# relay_matrix_16x8.net
KiCad netlist of a schematic drawn in EAGLE
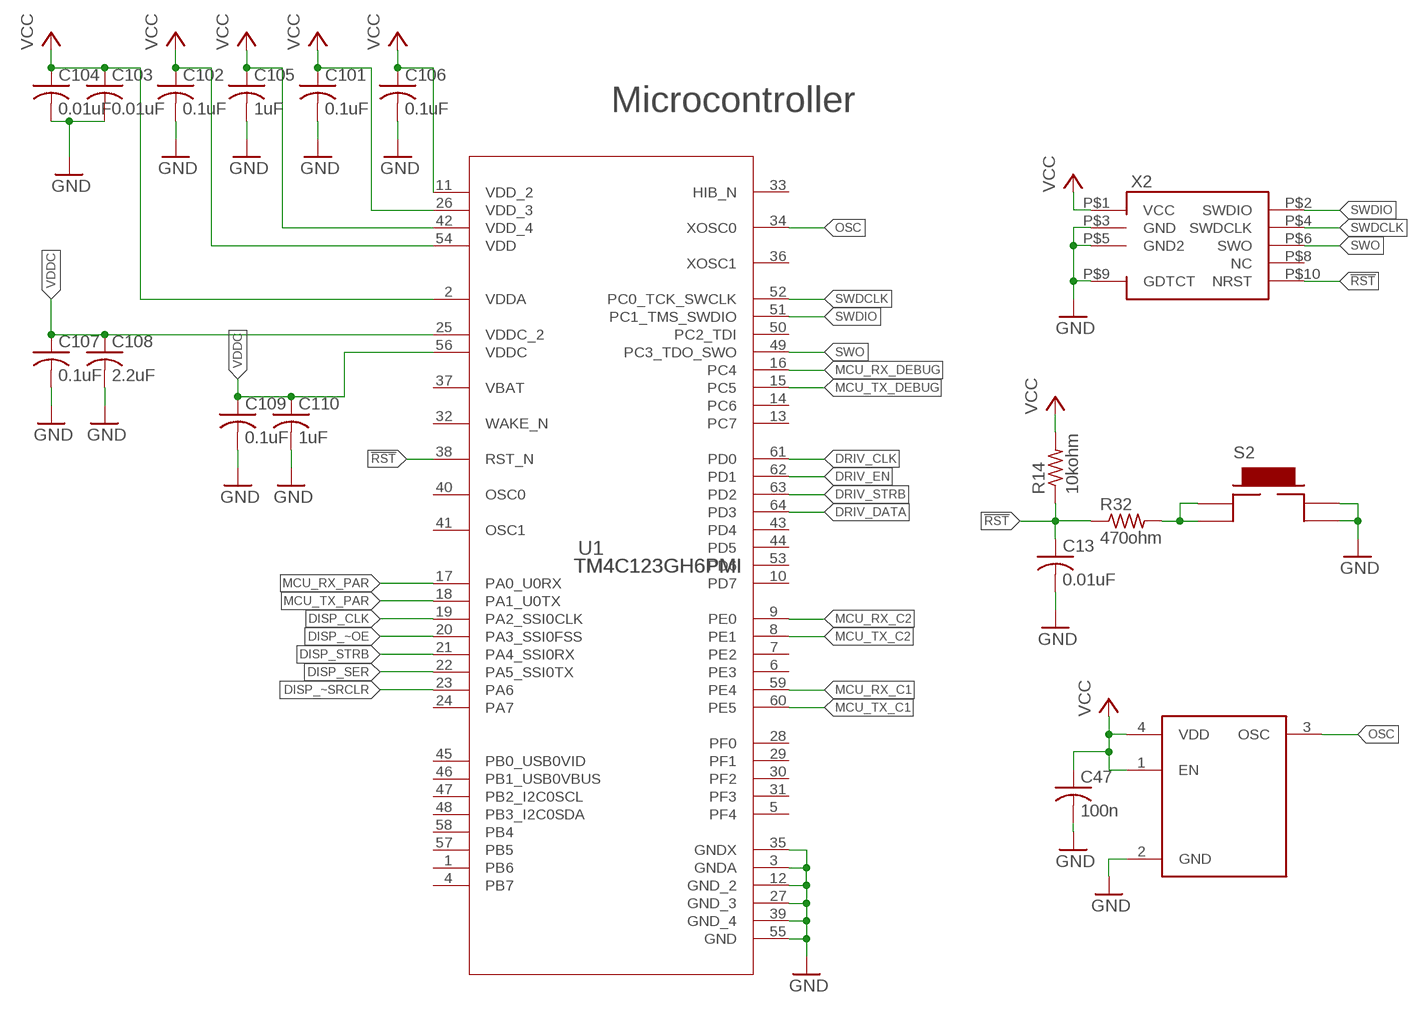
[diagram p0: schematic, sheet 1]
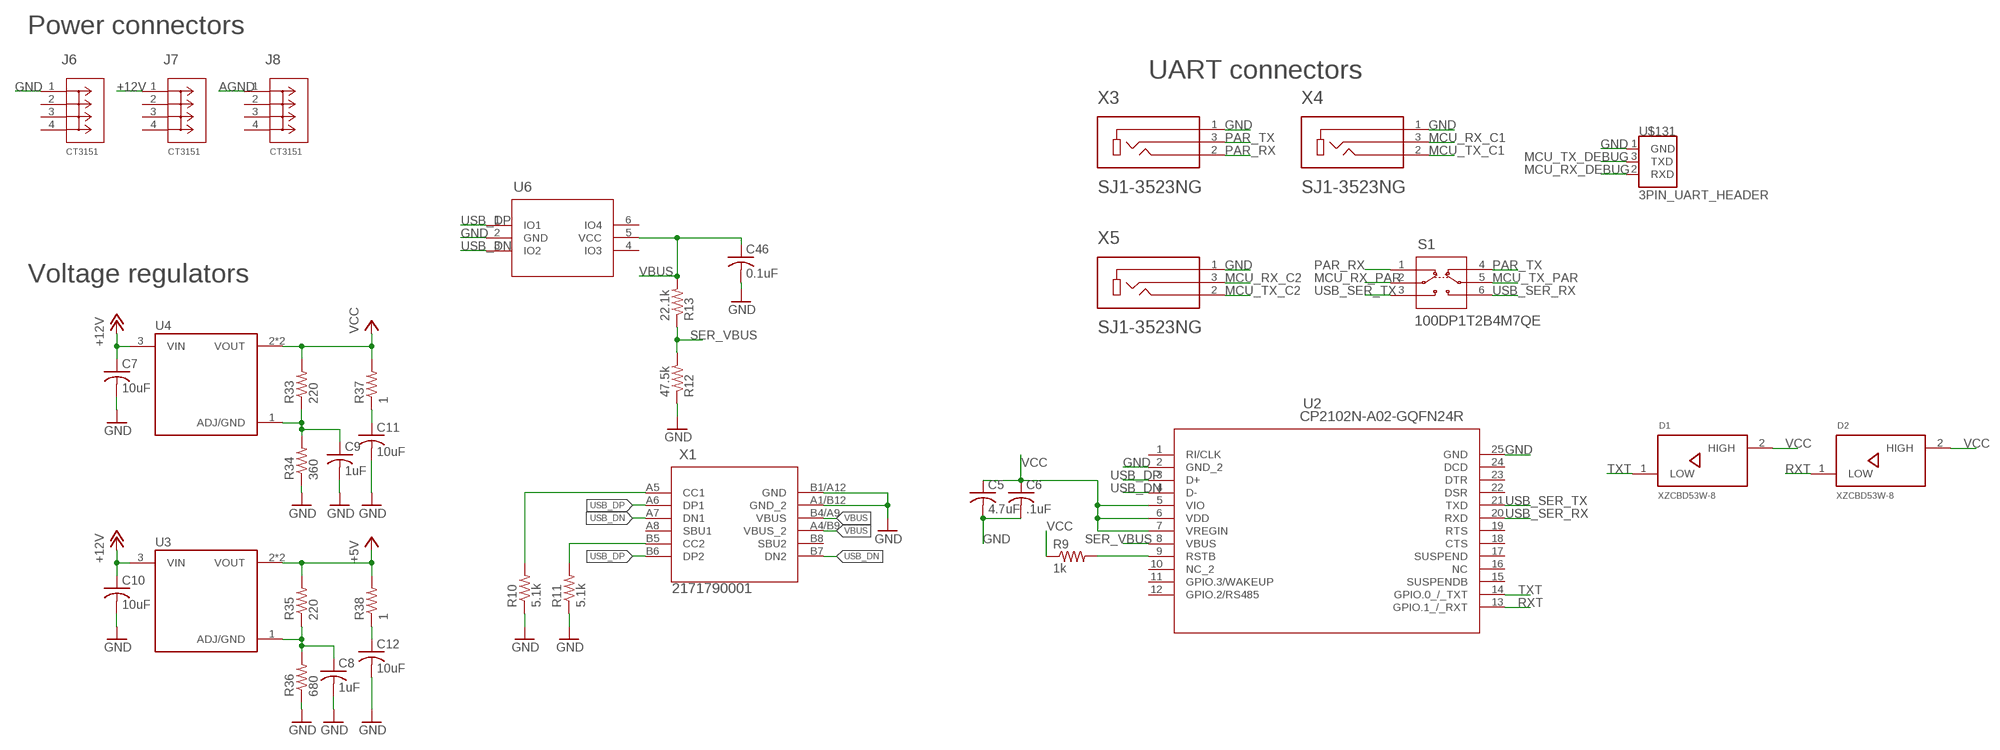
[diagram p1: schematic, sheet 2]
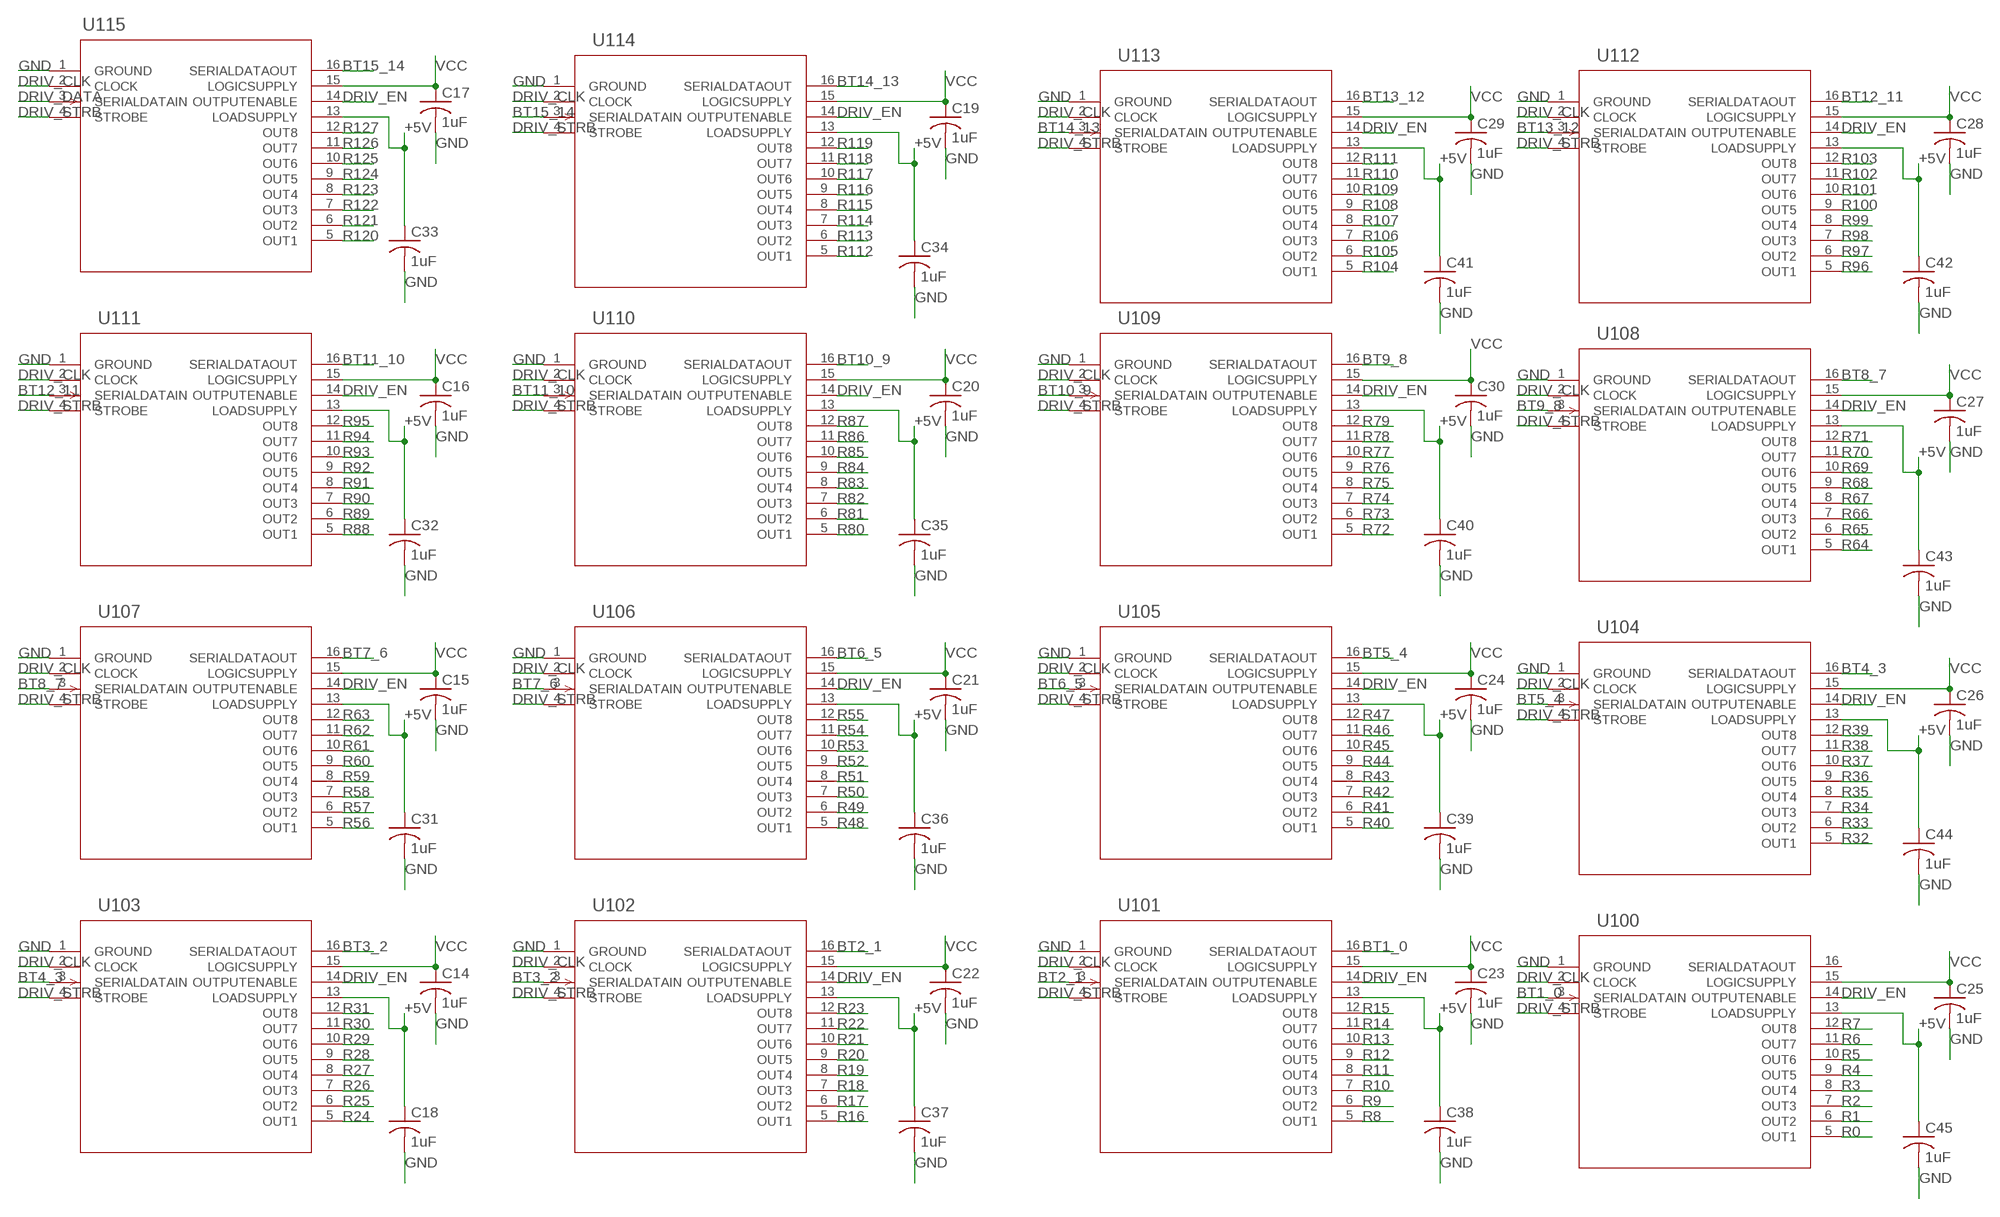
[diagram p2: schematic, sheet 3]
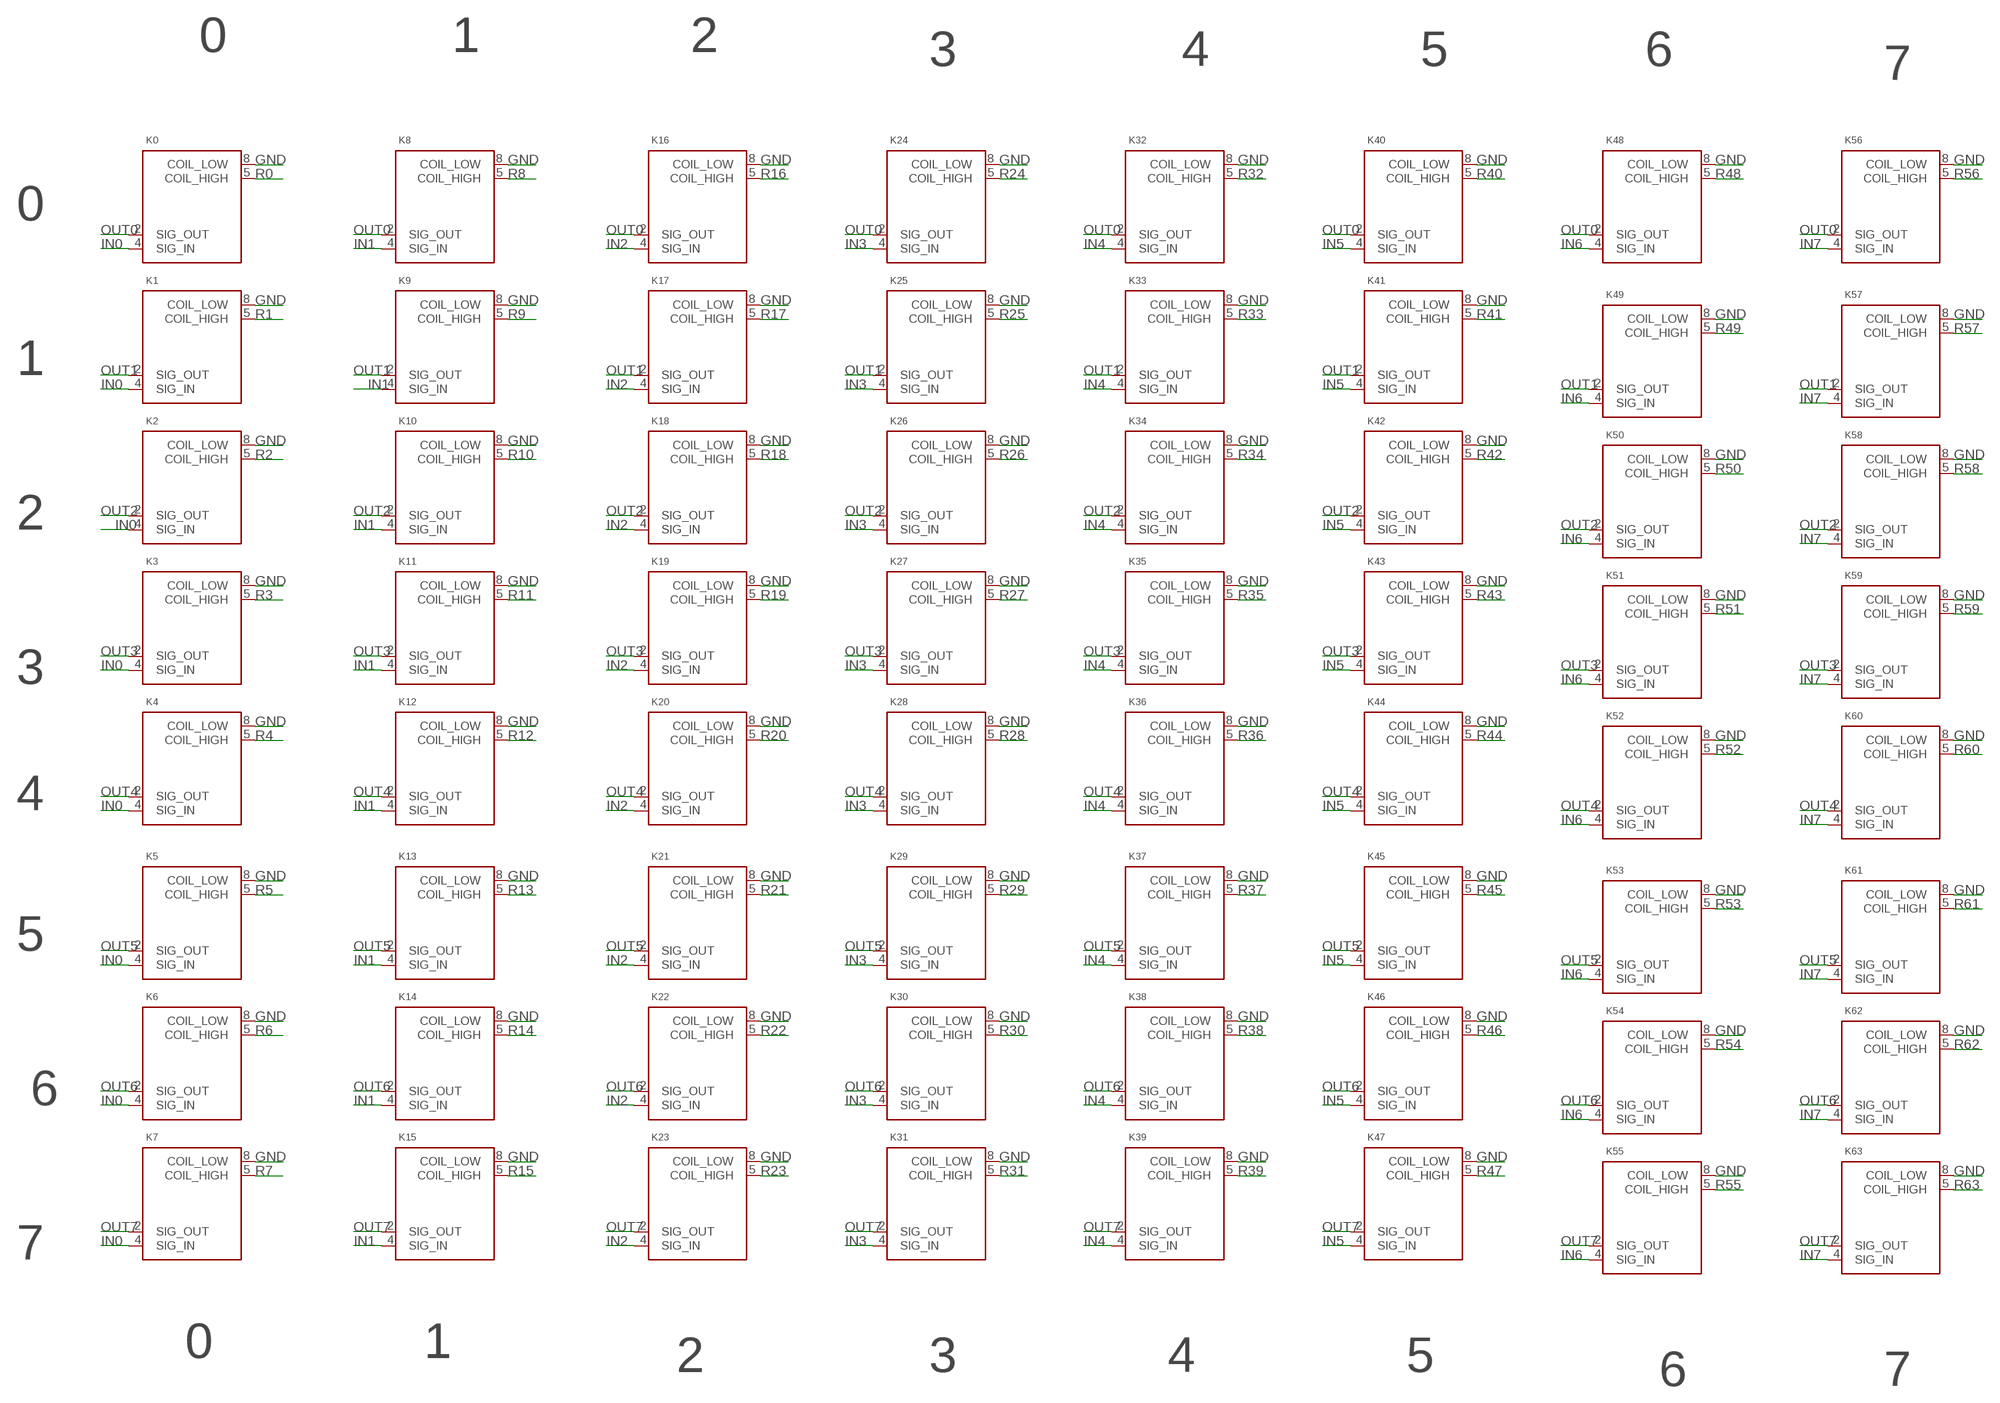
[diagram p3: schematic, sheet 4, part 1 of 2]
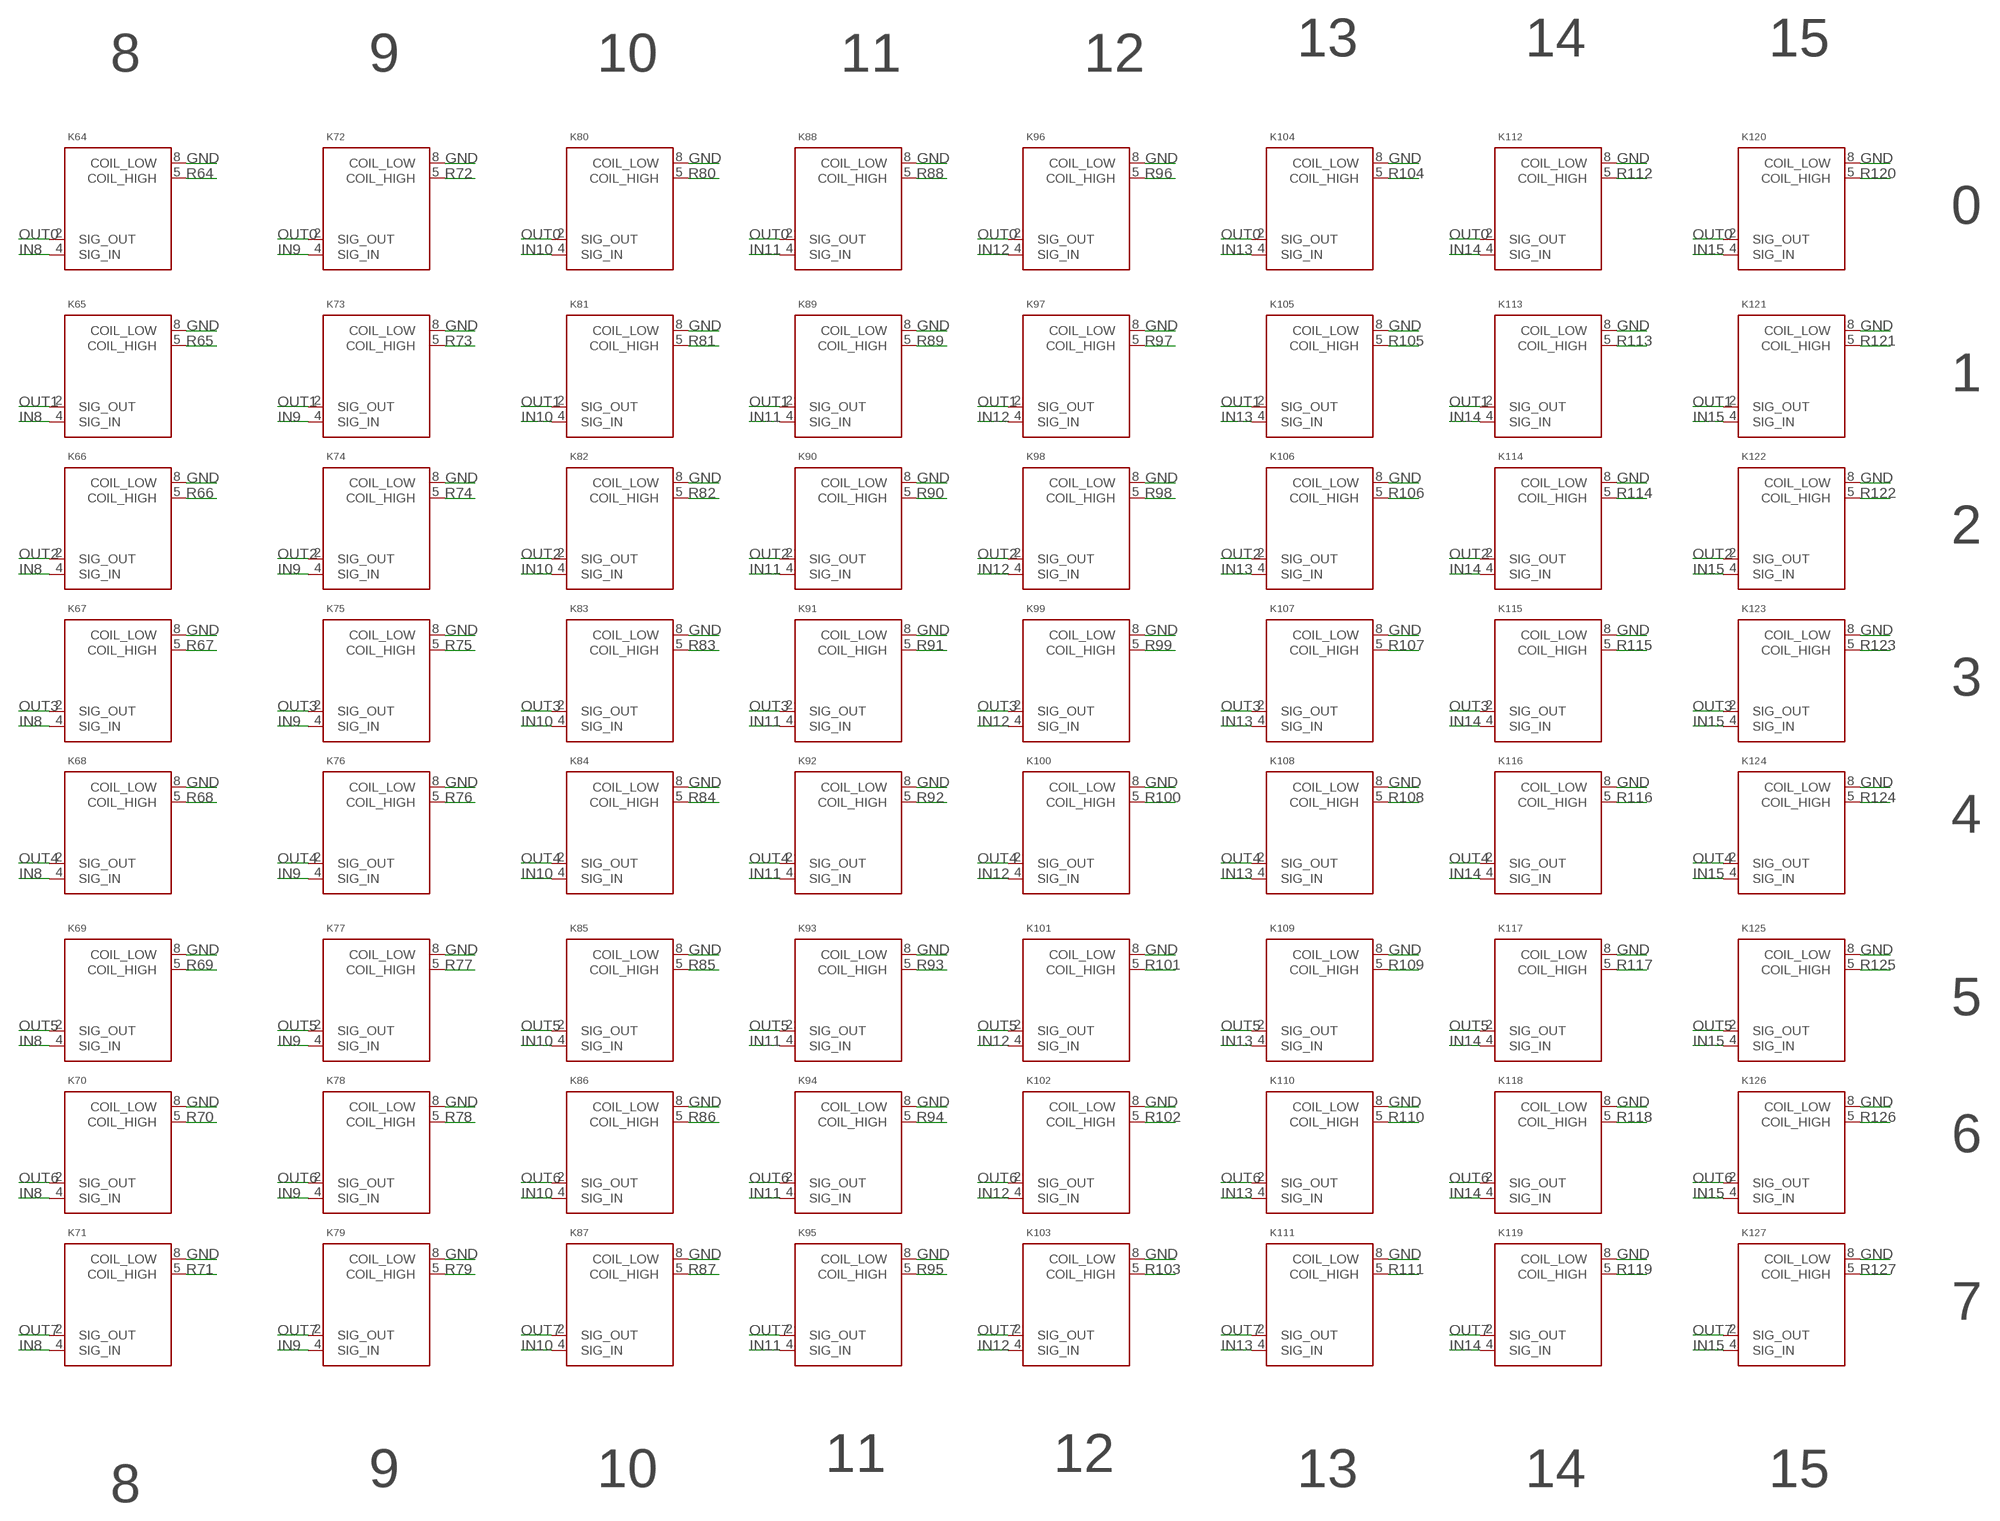
[diagram p4: schematic, sheet 4, part 2 of 2]
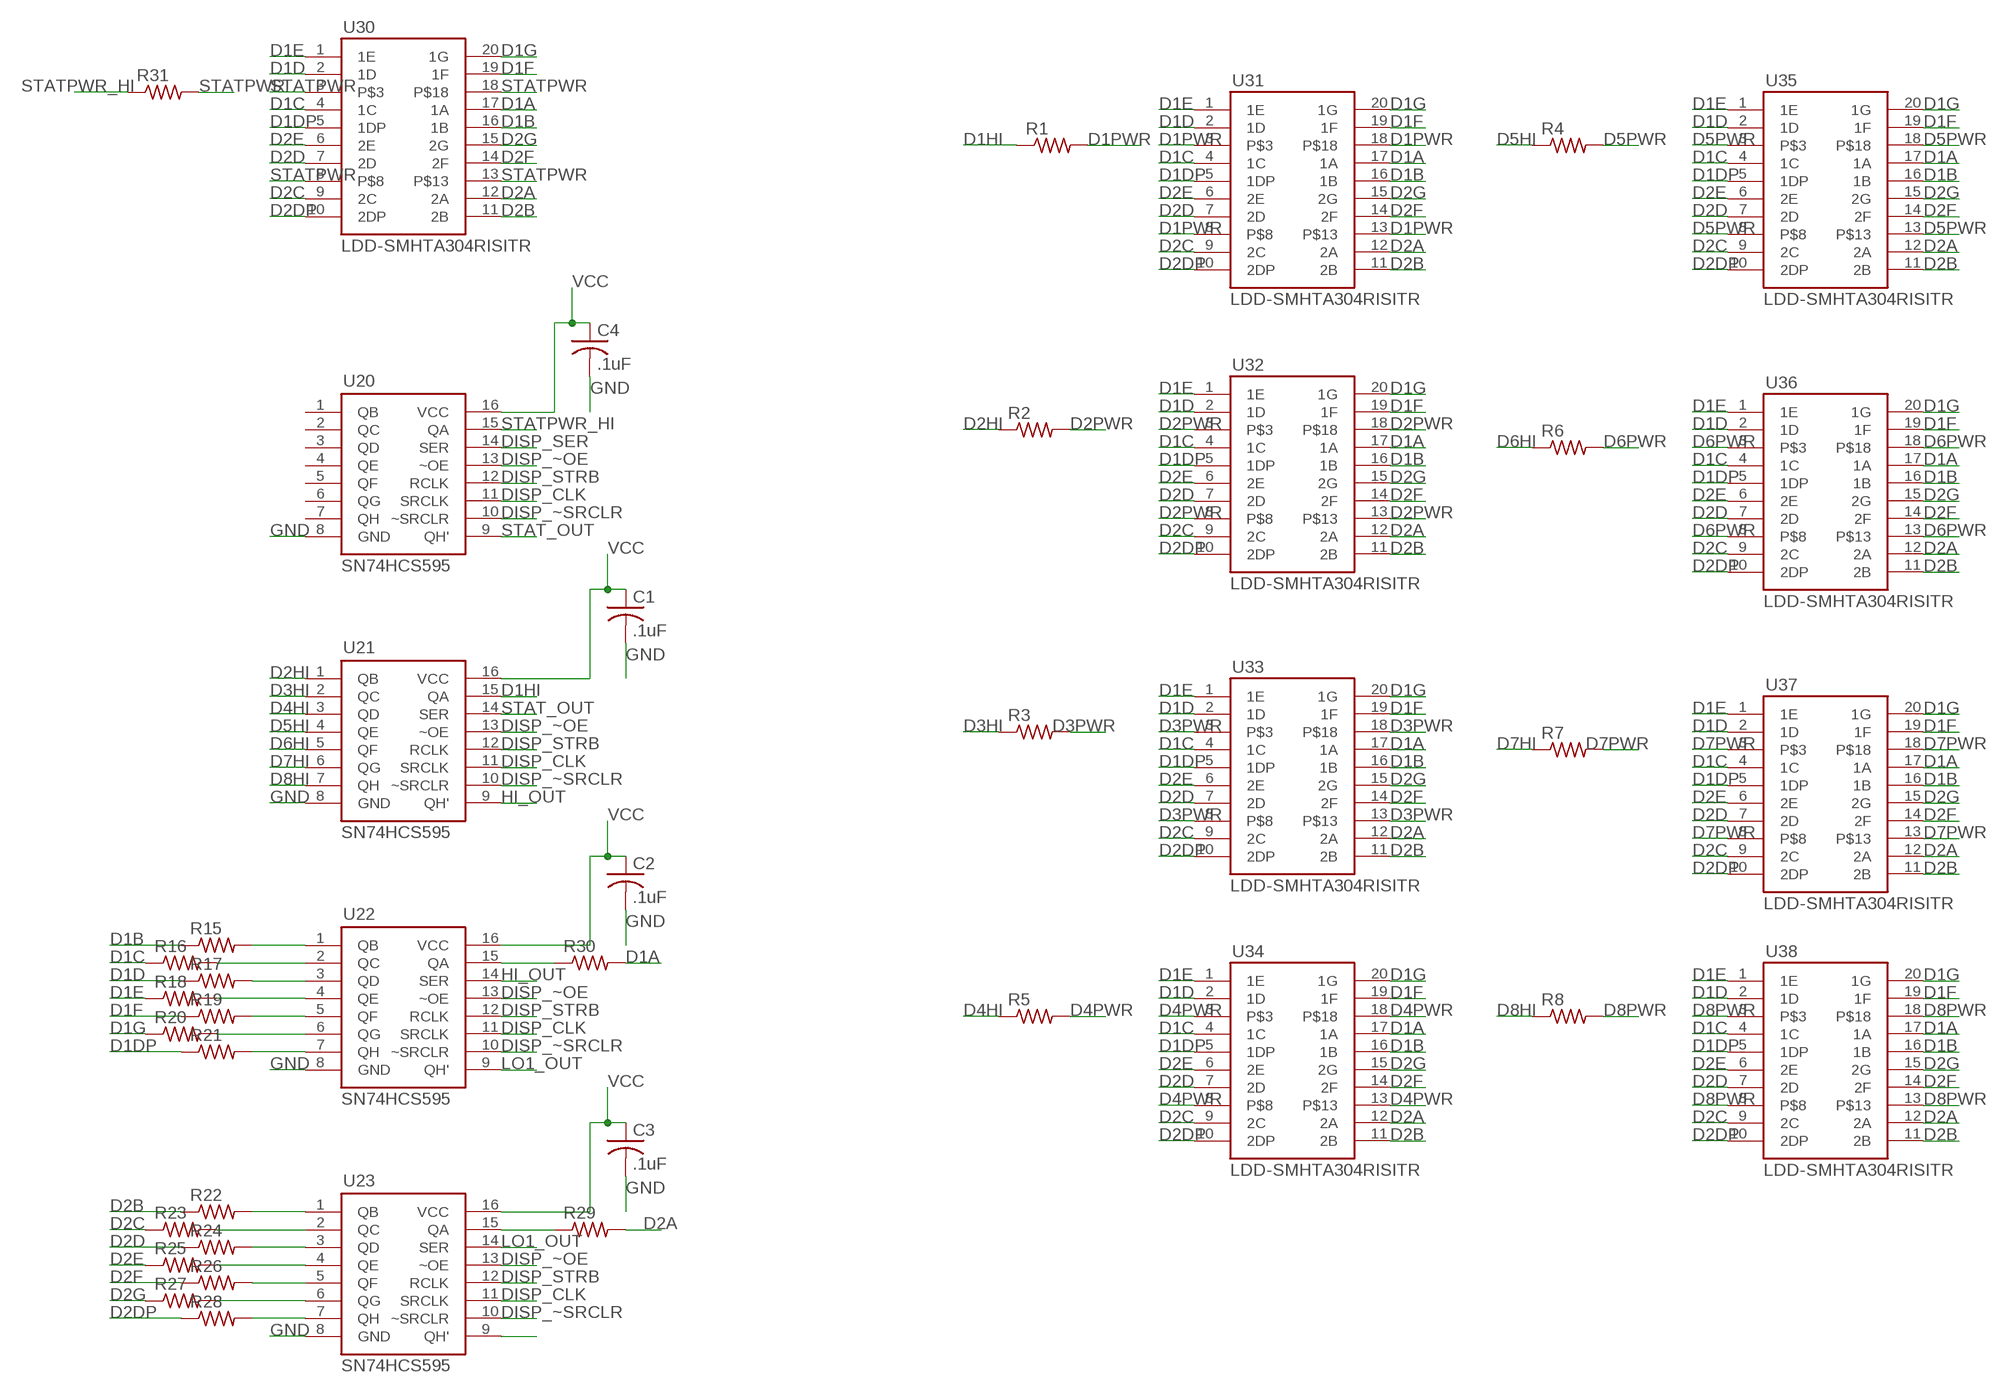
[diagram p5: schematic, sheet 5]
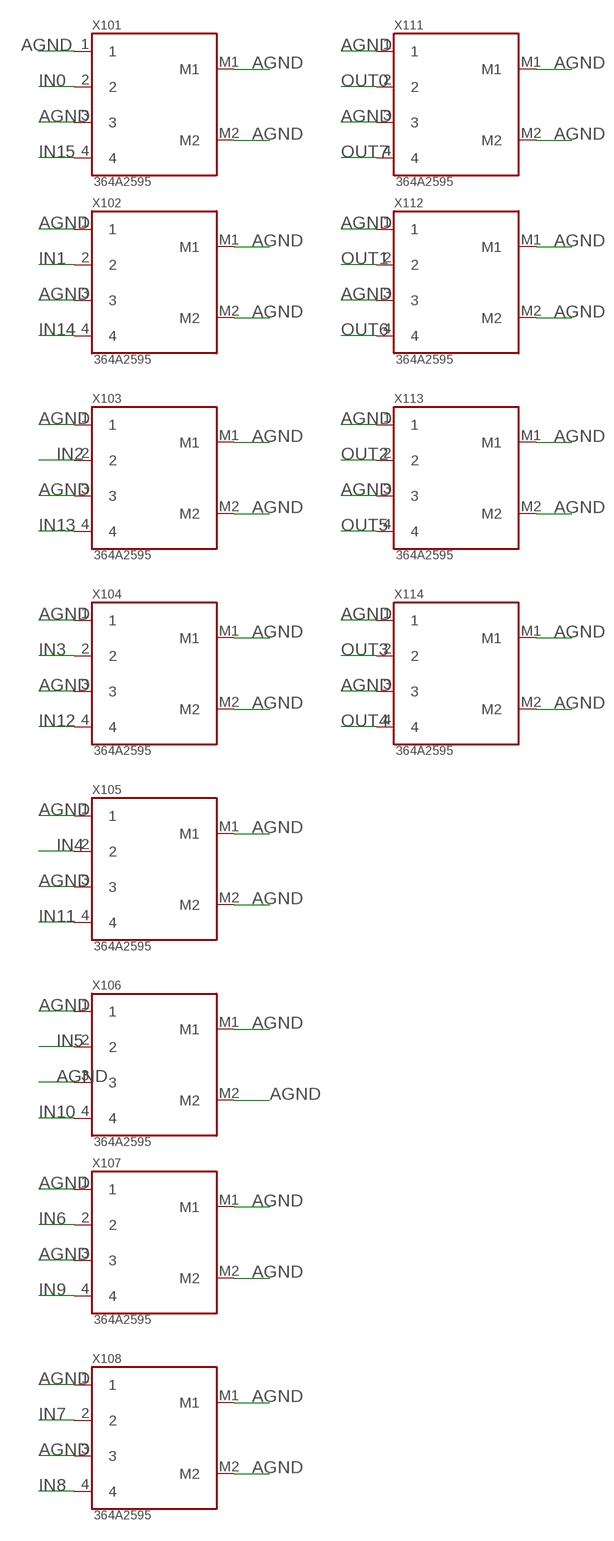
[diagram p6: schematic, sheet 6]

(export (version "E")
  (design (tool "Eeschema 10.0.6"))
  (components
    (comp (ref "X101")
      (value "364A2595")
      (footprint "eagle-import:364A2595")
      (libsource (lib "eagle-import") (part "364A2595"))
    )
    (comp (ref "X102")
      (value "364A2595")
      (footprint "eagle-import:364A2595")
      (libsource (lib "eagle-import") (part "364A2595"))
    )
    (comp (ref "X103")
      (value "364A2595")
      (footprint "eagle-import:364A2595")
      (libsource (lib "eagle-import") (part "364A2595"))
    )
    (comp (ref "X104")
      (value "364A2595")
      (footprint "eagle-import:364A2595")
      (libsource (lib "eagle-import") (part "364A2595"))
    )
    (comp (ref "X105")
      (value "364A2595")
      (footprint "eagle-import:364A2595")
      (libsource (lib "eagle-import") (part "364A2595"))
    )
    (comp (ref "X106")
      (value "364A2595")
      (footprint "eagle-import:364A2595")
      (libsource (lib "eagle-import") (part "364A2595"))
    )
    (comp (ref "X107")
      (value "364A2595")
      (footprint "eagle-import:364A2595")
      (libsource (lib "eagle-import") (part "364A2595"))
    )
    (comp (ref "X108")
      (value "364A2595")
      (footprint "eagle-import:364A2595")
      (libsource (lib "eagle-import") (part "364A2595"))
    )
    (comp (ref "X111")
      (value "364A2595")
      (footprint "eagle-import:364A2595")
      (libsource (lib "eagle-import") (part "364A2595"))
    )
    (comp (ref "X112")
      (value "364A2595")
      (footprint "eagle-import:364A2595")
      (libsource (lib "eagle-import") (part "364A2595"))
    )
    (comp (ref "X113")
      (value "364A2595")
      (footprint "eagle-import:364A2595")
      (libsource (lib "eagle-import") (part "364A2595"))
    )
    (comp (ref "X114")
      (value "364A2595")
      (footprint "eagle-import:364A2595")
      (libsource (lib "eagle-import") (part "364A2595"))
    )
    (comp (ref "C1")
      (value ".1uF")
      (footprint "eagle-import:C0402")
      (fields (field (name "MANUFACTURER_PART_NUMBER") "CL05B104KO5NNNC"))
      (libsource (lib "eagle-import") (part "resistor_348_C-USC0402"))
    )
    (comp (ref "C2")
      (value ".1uF")
      (footprint "eagle-import:C0402")
      (fields (field (name "MANUFACTURER_PART_NUMBER") "CL05B104KO5NNNC"))
      (libsource (lib "eagle-import") (part "resistor_348_C-USC0402"))
    )
    (comp (ref "C3")
      (value ".1uF")
      (footprint "eagle-import:C0402")
      (fields (field (name "MANUFACTURER_PART_NUMBER") "CL05B104KO5NNNC"))
      (libsource (lib "eagle-import") (part "resistor_348_C-USC0402"))
    )
    (comp (ref "C4")
      (value ".1uF")
      (footprint "eagle-import:C0402")
      (fields (field (name "MANUFACTURER_PART_NUMBER") "CL05B104KO5NNNC"))
      (libsource (lib "eagle-import") (part "resistor_348_C-USC0402"))
    )
    (comp (ref "R1")
      (value "R-US_R0402")
      (footprint "eagle-import:R0402")
      (libsource (lib "eagle-import") (part "resistor_348_R-US_R0402"))
    )
    (comp (ref "R2")
      (value "R-US_R0402")
      (footprint "eagle-import:R0402")
      (libsource (lib "eagle-import") (part "resistor_348_R-US_R0402"))
    )
    (comp (ref "R3")
      (value "R-US_R0402")
      (footprint "eagle-import:R0402")
      (libsource (lib "eagle-import") (part "resistor_348_R-US_R0402"))
    )
    (comp (ref "R4")
      (value "R-US_R0402")
      (footprint "eagle-import:R0402")
      (libsource (lib "eagle-import") (part "resistor_348_R-US_R0402"))
    )
    (comp (ref "R5")
      (value "R-US_R0402")
      (footprint "eagle-import:R0402")
      (libsource (lib "eagle-import") (part "resistor_348_R-US_R0402"))
    )
    (comp (ref "R6")
      (value "R-US_R0402")
      (footprint "eagle-import:R0402")
      (libsource (lib "eagle-import") (part "resistor_348_R-US_R0402"))
    )
    (comp (ref "R7")
      (value "R-US_R0402")
      (footprint "eagle-import:R0402")
      (libsource (lib "eagle-import") (part "resistor_348_R-US_R0402"))
    )
    (comp (ref "R8")
      (value "R-US_R0402")
      (footprint "eagle-import:R0402")
      (libsource (lib "eagle-import") (part "resistor_348_R-US_R0402"))
    )
    (comp (ref "R15")
      (value "R-US_R0402")
      (footprint "eagle-import:R0402")
      (libsource (lib "eagle-import") (part "resistor_348_R-US_R0402"))
    )
    (comp (ref "R16")
      (value "R-US_R0402")
      (footprint "eagle-import:R0402")
      (libsource (lib "eagle-import") (part "resistor_348_R-US_R0402"))
    )
    (comp (ref "R17")
      (value "R-US_R0402")
      (footprint "eagle-import:R0402")
      (libsource (lib "eagle-import") (part "resistor_348_R-US_R0402"))
    )
    (comp (ref "R18")
      (value "R-US_R0402")
      (footprint "eagle-import:R0402")
      (libsource (lib "eagle-import") (part "resistor_348_R-US_R0402"))
    )
    (comp (ref "R19")
      (value "R-US_R0402")
      (footprint "eagle-import:R0402")
      (libsource (lib "eagle-import") (part "resistor_348_R-US_R0402"))
    )
    (comp (ref "R20")
      (value "R-US_R0402")
      (footprint "eagle-import:R0402")
      (libsource (lib "eagle-import") (part "resistor_348_R-US_R0402"))
    )
    (comp (ref "R21")
      (value "R-US_R0402")
      (footprint "eagle-import:R0402")
      (libsource (lib "eagle-import") (part "resistor_348_R-US_R0402"))
    )
    (comp (ref "R22")
      (value "R-US_R0402")
      (footprint "eagle-import:R0402")
      (libsource (lib "eagle-import") (part "resistor_348_R-US_R0402"))
    )
    (comp (ref "R23")
      (value "R-US_R0402")
      (footprint "eagle-import:R0402")
      (libsource (lib "eagle-import") (part "resistor_348_R-US_R0402"))
    )
    (comp (ref "R24")
      (value "R-US_R0402")
      (footprint "eagle-import:R0402")
      (libsource (lib "eagle-import") (part "resistor_348_R-US_R0402"))
    )
    (comp (ref "R25")
      (value "R-US_R0402")
      (footprint "eagle-import:R0402")
      (libsource (lib "eagle-import") (part "resistor_348_R-US_R0402"))
    )
    (comp (ref "R26")
      (value "R-US_R0402")
      (footprint "eagle-import:R0402")
      (libsource (lib "eagle-import") (part "resistor_348_R-US_R0402"))
    )
    (comp (ref "R27")
      (value "R-US_R0402")
      (footprint "eagle-import:R0402")
      (libsource (lib "eagle-import") (part "resistor_348_R-US_R0402"))
    )
    (comp (ref "R28")
      (value "R-US_R0402")
      (footprint "eagle-import:R0402")
      (libsource (lib "eagle-import") (part "resistor_348_R-US_R0402"))
    )
    (comp (ref "R29")
      (value "R-US_R0402")
      (footprint "eagle-import:R0402")
      (libsource (lib "eagle-import") (part "resistor_348_R-US_R0402"))
    )
    (comp (ref "R30")
      (value "R-US_R0402")
      (footprint "eagle-import:R0402")
      (libsource (lib "eagle-import") (part "resistor_348_R-US_R0402"))
    )
    (comp (ref "R31")
      (value "R-US_R0402")
      (footprint "eagle-import:R0402")
      (libsource (lib "eagle-import") (part "resistor_348_R-US_R0402"))
    )
    (comp (ref "U20")
      (value "SN74HCS595")
      (footprint "eagle-import:SOP65P640X120-16N")
      (fields (field (name "MANUFACTURER_PART_NUMBER") "SN74HCS595PWR"))
      (libsource (lib "eagle-import") (part "SN74HCS595"))
    )
    (comp (ref "U21")
      (value "SN74HCS595")
      (footprint "eagle-import:SOP65P640X120-16N")
      (fields (field (name "MANUFACTURER_PART_NUMBER") "SN74HCS595PWR"))
      (libsource (lib "eagle-import") (part "SN74HCS595"))
    )
    (comp (ref "U22")
      (value "SN74HCS595")
      (footprint "eagle-import:SOP65P640X120-16N")
      (fields (field (name "MANUFACTURER_PART_NUMBER") "SN74HCS595PWR"))
      (libsource (lib "eagle-import") (part "SN74HCS595"))
    )
    (comp (ref "U23")
      (value "SN74HCS595")
      (footprint "eagle-import:SOP65P640X120-16N")
      (fields (field (name "MANUFACTURER_PART_NUMBER") "SN74HCS595PWR"))
      (libsource (lib "eagle-import") (part "SN74HCS595"))
    )
    (comp (ref "U30")
      (value "LDD-SMHTA304RISITR")
      (footprint "eagle-import:LDD-SMHTA304RISITR-20DFN")
      (libsource (lib "eagle-import") (part "LDD-SMHTA304RISITR"))
    )
    (comp (ref "U31")
      (value "LDD-SMHTA304RISITR")
      (footprint "eagle-import:LDD-SMHTA304RISITR-20DFN")
      (libsource (lib "eagle-import") (part "LDD-SMHTA304RISITR"))
    )
    (comp (ref "U32")
      (value "LDD-SMHTA304RISITR")
      (footprint "eagle-import:LDD-SMHTA304RISITR-20DFN")
      (libsource (lib "eagle-import") (part "LDD-SMHTA304RISITR"))
    )
    (comp (ref "U33")
      (value "LDD-SMHTA304RISITR")
      (footprint "eagle-import:LDD-SMHTA304RISITR-20DFN")
      (libsource (lib "eagle-import") (part "LDD-SMHTA304RISITR"))
    )
    (comp (ref "U34")
      (value "LDD-SMHTA304RISITR")
      (footprint "eagle-import:LDD-SMHTA304RISITR-20DFN")
      (libsource (lib "eagle-import") (part "LDD-SMHTA304RISITR"))
    )
    (comp (ref "U35")
      (value "LDD-SMHTA304RISITR")
      (footprint "eagle-import:LDD-SMHTA304RISITR-20DFN")
      (libsource (lib "eagle-import") (part "LDD-SMHTA304RISITR"))
    )
    (comp (ref "U36")
      (value "LDD-SMHTA304RISITR")
      (footprint "eagle-import:LDD-SMHTA304RISITR-20DFN")
      (libsource (lib "eagle-import") (part "LDD-SMHTA304RISITR"))
    )
    (comp (ref "U37")
      (value "LDD-SMHTA304RISITR")
      (footprint "eagle-import:LDD-SMHTA304RISITR-20DFN")
      (libsource (lib "eagle-import") (part "LDD-SMHTA304RISITR"))
    )
    (comp (ref "U38")
      (value "LDD-SMHTA304RISITR")
      (footprint "eagle-import:LDD-SMHTA304RISITR-20DFN")
      (libsource (lib "eagle-import") (part "LDD-SMHTA304RISITR"))
    )
    (comp (ref "K0")
      (value "G6L-1F-DC4.5")
      (footprint "eagle-import:G6L-1F-DC4.5")
      (libsource (lib "eagle-import") (part "G6L-1F-DC4.5"))
    )
    (comp (ref "K1")
      (value "G6L-1F-DC4.5")
      (footprint "eagle-import:G6L-1F-DC4.5")
      (libsource (lib "eagle-import") (part "G6L-1F-DC4.5"))
    )
    (comp (ref "K2")
      (value "G6L-1F-DC4.5")
      (footprint "eagle-import:G6L-1F-DC4.5")
      (libsource (lib "eagle-import") (part "G6L-1F-DC4.5"))
    )
    (comp (ref "K3")
      (value "G6L-1F-DC4.5")
      (footprint "eagle-import:G6L-1F-DC4.5")
      (libsource (lib "eagle-import") (part "G6L-1F-DC4.5"))
    )
    (comp (ref "K4")
      (value "G6L-1F-DC4.5")
      (footprint "eagle-import:G6L-1F-DC4.5")
      (libsource (lib "eagle-import") (part "G6L-1F-DC4.5"))
    )
    (comp (ref "K5")
      (value "G6L-1F-DC4.5")
      (footprint "eagle-import:G6L-1F-DC4.5")
      (libsource (lib "eagle-import") (part "G6L-1F-DC4.5"))
    )
    (comp (ref "K6")
      (value "G6L-1F-DC4.5")
      (footprint "eagle-import:G6L-1F-DC4.5")
      (libsource (lib "eagle-import") (part "G6L-1F-DC4.5"))
    )
    (comp (ref "K7")
      (value "G6L-1F-DC4.5")
      (footprint "eagle-import:G6L-1F-DC4.5")
      (libsource (lib "eagle-import") (part "G6L-1F-DC4.5"))
    )
    (comp (ref "K8")
      (value "G6L-1F-DC4.5")
      (footprint "eagle-import:G6L-1F-DC4.5")
      (libsource (lib "eagle-import") (part "G6L-1F-DC4.5"))
    )
    (comp (ref "K9")
      (value "G6L-1F-DC4.5")
      (footprint "eagle-import:G6L-1F-DC4.5")
      (libsource (lib "eagle-import") (part "G6L-1F-DC4.5"))
    )
    (comp (ref "K10")
      (value "G6L-1F-DC4.5")
      (footprint "eagle-import:G6L-1F-DC4.5")
      (libsource (lib "eagle-import") (part "G6L-1F-DC4.5"))
    )
    (comp (ref "K11")
      (value "G6L-1F-DC4.5")
      (footprint "eagle-import:G6L-1F-DC4.5")
      (libsource (lib "eagle-import") (part "G6L-1F-DC4.5"))
    )
    (comp (ref "K12")
      (value "G6L-1F-DC4.5")
      (footprint "eagle-import:G6L-1F-DC4.5")
      (libsource (lib "eagle-import") (part "G6L-1F-DC4.5"))
    )
    (comp (ref "K13")
      (value "G6L-1F-DC4.5")
      (footprint "eagle-import:G6L-1F-DC4.5")
      (libsource (lib "eagle-import") (part "G6L-1F-DC4.5"))
    )
    (comp (ref "K14")
      (value "G6L-1F-DC4.5")
      (footprint "eagle-import:G6L-1F-DC4.5")
      (libsource (lib "eagle-import") (part "G6L-1F-DC4.5"))
    )
    (comp (ref "K15")
      (value "G6L-1F-DC4.5")
      (footprint "eagle-import:G6L-1F-DC4.5")
      (libsource (lib "eagle-import") (part "G6L-1F-DC4.5"))
    )
    (comp (ref "K16")
      (value "G6L-1F-DC4.5")
      (footprint "eagle-import:G6L-1F-DC4.5")
      (libsource (lib "eagle-import") (part "G6L-1F-DC4.5"))
    )
    (comp (ref "K17")
      (value "G6L-1F-DC4.5")
      (footprint "eagle-import:G6L-1F-DC4.5")
      (libsource (lib "eagle-import") (part "G6L-1F-DC4.5"))
    )
    (comp (ref "K18")
      (value "G6L-1F-DC4.5")
      (footprint "eagle-import:G6L-1F-DC4.5")
      (libsource (lib "eagle-import") (part "G6L-1F-DC4.5"))
    )
    (comp (ref "K19")
      (value "G6L-1F-DC4.5")
      (footprint "eagle-import:G6L-1F-DC4.5")
      (libsource (lib "eagle-import") (part "G6L-1F-DC4.5"))
    )
    (comp (ref "K20")
      (value "G6L-1F-DC4.5")
      (footprint "eagle-import:G6L-1F-DC4.5")
      (libsource (lib "eagle-import") (part "G6L-1F-DC4.5"))
    )
    (comp (ref "K21")
      (value "G6L-1F-DC4.5")
      (footprint "eagle-import:G6L-1F-DC4.5")
      (libsource (lib "eagle-import") (part "G6L-1F-DC4.5"))
    )
    (comp (ref "K22")
      (value "G6L-1F-DC4.5")
      (footprint "eagle-import:G6L-1F-DC4.5")
      (libsource (lib "eagle-import") (part "G6L-1F-DC4.5"))
    )
    (comp (ref "K23")
      (value "G6L-1F-DC4.5")
      (footprint "eagle-import:G6L-1F-DC4.5")
      (libsource (lib "eagle-import") (part "G6L-1F-DC4.5"))
    )
    (comp (ref "K24")
      (value "G6L-1F-DC4.5")
      (footprint "eagle-import:G6L-1F-DC4.5")
      (libsource (lib "eagle-import") (part "G6L-1F-DC4.5"))
    )
    (comp (ref "K25")
      (value "G6L-1F-DC4.5")
      (footprint "eagle-import:G6L-1F-DC4.5")
      (libsource (lib "eagle-import") (part "G6L-1F-DC4.5"))
    )
    (comp (ref "K26")
      (value "G6L-1F-DC4.5")
      (footprint "eagle-import:G6L-1F-DC4.5")
      (libsource (lib "eagle-import") (part "G6L-1F-DC4.5"))
    )
    (comp (ref "K27")
      (value "G6L-1F-DC4.5")
      (footprint "eagle-import:G6L-1F-DC4.5")
      (libsource (lib "eagle-import") (part "G6L-1F-DC4.5"))
    )
    (comp (ref "K28")
      (value "G6L-1F-DC4.5")
      (footprint "eagle-import:G6L-1F-DC4.5")
      (libsource (lib "eagle-import") (part "G6L-1F-DC4.5"))
    )
    (comp (ref "K29")
      (value "G6L-1F-DC4.5")
      (footprint "eagle-import:G6L-1F-DC4.5")
      (libsource (lib "eagle-import") (part "G6L-1F-DC4.5"))
    )
    (comp (ref "K30")
      (value "G6L-1F-DC4.5")
      (footprint "eagle-import:G6L-1F-DC4.5")
      (libsource (lib "eagle-import") (part "G6L-1F-DC4.5"))
    )
    (comp (ref "K31")
      (value "G6L-1F-DC4.5")
      (footprint "eagle-import:G6L-1F-DC4.5")
      (libsource (lib "eagle-import") (part "G6L-1F-DC4.5"))
    )
    (comp (ref "K32")
      (value "G6L-1F-DC4.5")
      (footprint "eagle-import:G6L-1F-DC4.5")
      (libsource (lib "eagle-import") (part "G6L-1F-DC4.5"))
    )
    (comp (ref "K33")
      (value "G6L-1F-DC4.5")
      (footprint "eagle-import:G6L-1F-DC4.5")
      (libsource (lib "eagle-import") (part "G6L-1F-DC4.5"))
    )
    (comp (ref "K34")
      (value "G6L-1F-DC4.5")
      (footprint "eagle-import:G6L-1F-DC4.5")
      (libsource (lib "eagle-import") (part "G6L-1F-DC4.5"))
    )
    (comp (ref "K35")
      (value "G6L-1F-DC4.5")
      (footprint "eagle-import:G6L-1F-DC4.5")
      (libsource (lib "eagle-import") (part "G6L-1F-DC4.5"))
    )
    (comp (ref "K36")
      (value "G6L-1F-DC4.5")
      (footprint "eagle-import:G6L-1F-DC4.5")
      (libsource (lib "eagle-import") (part "G6L-1F-DC4.5"))
    )
    (comp (ref "K37")
      (value "G6L-1F-DC4.5")
      (footprint "eagle-import:G6L-1F-DC4.5")
      (libsource (lib "eagle-import") (part "G6L-1F-DC4.5"))
    )
    (comp (ref "K38")
      (value "G6L-1F-DC4.5")
      (footprint "eagle-import:G6L-1F-DC4.5")
      (libsource (lib "eagle-import") (part "G6L-1F-DC4.5"))
    )
    (comp (ref "K39")
      (value "G6L-1F-DC4.5")
      (footprint "eagle-import:G6L-1F-DC4.5")
      (libsource (lib "eagle-import") (part "G6L-1F-DC4.5"))
    )
    (comp (ref "K40")
      (value "G6L-1F-DC4.5")
      (footprint "eagle-import:G6L-1F-DC4.5")
      (libsource (lib "eagle-import") (part "G6L-1F-DC4.5"))
    )
    (comp (ref "K41")
      (value "G6L-1F-DC4.5")
      (footprint "eagle-import:G6L-1F-DC4.5")
      (libsource (lib "eagle-import") (part "G6L-1F-DC4.5"))
    )
    (comp (ref "K42")
      (value "G6L-1F-DC4.5")
      (footprint "eagle-import:G6L-1F-DC4.5")
      (libsource (lib "eagle-import") (part "G6L-1F-DC4.5"))
    )
    (comp (ref "K43")
      (value "G6L-1F-DC4.5")
      (footprint "eagle-import:G6L-1F-DC4.5")
      (libsource (lib "eagle-import") (part "G6L-1F-DC4.5"))
    )
    (comp (ref "K44")
      (value "G6L-1F-DC4.5")
      (footprint "eagle-import:G6L-1F-DC4.5")
      (libsource (lib "eagle-import") (part "G6L-1F-DC4.5"))
    )
    (comp (ref "K45")
      (value "G6L-1F-DC4.5")
      (footprint "eagle-import:G6L-1F-DC4.5")
      (libsource (lib "eagle-import") (part "G6L-1F-DC4.5"))
    )
    (comp (ref "K46")
      (value "G6L-1F-DC4.5")
      (footprint "eagle-import:G6L-1F-DC4.5")
      (libsource (lib "eagle-import") (part "G6L-1F-DC4.5"))
    )
    (comp (ref "K47")
      (value "G6L-1F-DC4.5")
      (footprint "eagle-import:G6L-1F-DC4.5")
      (libsource (lib "eagle-import") (part "G6L-1F-DC4.5"))
    )
    (comp (ref "K48")
      (value "G6L-1F-DC4.5")
      (footprint "eagle-import:G6L-1F-DC4.5")
      (libsource (lib "eagle-import") (part "G6L-1F-DC4.5"))
    )
    (comp (ref "K49")
      (value "G6L-1F-DC4.5")
      (footprint "eagle-import:G6L-1F-DC4.5")
      (libsource (lib "eagle-import") (part "G6L-1F-DC4.5"))
    )
    (comp (ref "K50")
      (value "G6L-1F-DC4.5")
      (footprint "eagle-import:G6L-1F-DC4.5")
      (libsource (lib "eagle-import") (part "G6L-1F-DC4.5"))
    )
    (comp (ref "K51")
      (value "G6L-1F-DC4.5")
      (footprint "eagle-import:G6L-1F-DC4.5")
      (libsource (lib "eagle-import") (part "G6L-1F-DC4.5"))
    )
    (comp (ref "K52")
      (value "G6L-1F-DC4.5")
      (footprint "eagle-import:G6L-1F-DC4.5")
      (libsource (lib "eagle-import") (part "G6L-1F-DC4.5"))
    )
    (comp (ref "K53")
      (value "G6L-1F-DC4.5")
      (footprint "eagle-import:G6L-1F-DC4.5")
      (libsource (lib "eagle-import") (part "G6L-1F-DC4.5"))
    )
    (comp (ref "K54")
      (value "G6L-1F-DC4.5")
      (footprint "eagle-import:G6L-1F-DC4.5")
      (libsource (lib "eagle-import") (part "G6L-1F-DC4.5"))
    )
    (comp (ref "K55")
      (value "G6L-1F-DC4.5")
      (footprint "eagle-import:G6L-1F-DC4.5")
      (libsource (lib "eagle-import") (part "G6L-1F-DC4.5"))
    )
    (comp (ref "K56")
      (value "G6L-1F-DC4.5")
      (footprint "eagle-import:G6L-1F-DC4.5")
      (libsource (lib "eagle-import") (part "G6L-1F-DC4.5"))
    )
    (comp (ref "K57")
      (value "G6L-1F-DC4.5")
      (footprint "eagle-import:G6L-1F-DC4.5")
      (libsource (lib "eagle-import") (part "G6L-1F-DC4.5"))
    )
    (comp (ref "K58")
      (value "G6L-1F-DC4.5")
      (footprint "eagle-import:G6L-1F-DC4.5")
      (libsource (lib "eagle-import") (part "G6L-1F-DC4.5"))
    )
    (comp (ref "K59")
      (value "G6L-1F-DC4.5")
      (footprint "eagle-import:G6L-1F-DC4.5")
      (libsource (lib "eagle-import") (part "G6L-1F-DC4.5"))
    )
    (comp (ref "K60")
      (value "G6L-1F-DC4.5")
      (footprint "eagle-import:G6L-1F-DC4.5")
      (libsource (lib "eagle-import") (part "G6L-1F-DC4.5"))
    )
    (comp (ref "K61")
      (value "G6L-1F-DC4.5")
      (footprint "eagle-import:G6L-1F-DC4.5")
      (libsource (lib "eagle-import") (part "G6L-1F-DC4.5"))
    )
    (comp (ref "K62")
      (value "G6L-1F-DC4.5")
      (footprint "eagle-import:G6L-1F-DC4.5")
      (libsource (lib "eagle-import") (part "G6L-1F-DC4.5"))
    )
    (comp (ref "K63")
      (value "G6L-1F-DC4.5")
      (footprint "eagle-import:G6L-1F-DC4.5")
      (libsource (lib "eagle-import") (part "G6L-1F-DC4.5"))
    )
    (comp (ref "K64")
      (value "G6L-1F-DC4.5")
      (footprint "eagle-import:G6L-1F-DC4.5")
      (libsource (lib "eagle-import") (part "G6L-1F-DC4.5"))
    )
    (comp (ref "K65")
      (value "G6L-1F-DC4.5")
      (footprint "eagle-import:G6L-1F-DC4.5")
      (libsource (lib "eagle-import") (part "G6L-1F-DC4.5"))
    )
    (comp (ref "K66")
      (value "G6L-1F-DC4.5")
      (footprint "eagle-import:G6L-1F-DC4.5")
      (libsource (lib "eagle-import") (part "G6L-1F-DC4.5"))
    )
    (comp (ref "K67")
      (value "G6L-1F-DC4.5")
      (footprint "eagle-import:G6L-1F-DC4.5")
      (libsource (lib "eagle-import") (part "G6L-1F-DC4.5"))
    )
    (comp (ref "K68")
      (value "G6L-1F-DC4.5")
      (footprint "eagle-import:G6L-1F-DC4.5")
      (libsource (lib "eagle-import") (part "G6L-1F-DC4.5"))
    )
    (comp (ref "K69")
      (value "G6L-1F-DC4.5")
      (footprint "eagle-import:G6L-1F-DC4.5")
      (libsource (lib "eagle-import") (part "G6L-1F-DC4.5"))
    )
    (comp (ref "K70")
      (value "G6L-1F-DC4.5")
      (footprint "eagle-import:G6L-1F-DC4.5")
      (libsource (lib "eagle-import") (part "G6L-1F-DC4.5"))
    )
    (comp (ref "K71")
      (value "G6L-1F-DC4.5")
      (footprint "eagle-import:G6L-1F-DC4.5")
      (libsource (lib "eagle-import") (part "G6L-1F-DC4.5"))
    )
    (comp (ref "K72")
      (value "G6L-1F-DC4.5")
      (footprint "eagle-import:G6L-1F-DC4.5")
      (libsource (lib "eagle-import") (part "G6L-1F-DC4.5"))
    )
    (comp (ref "K73")
      (value "G6L-1F-DC4.5")
      (footprint "eagle-import:G6L-1F-DC4.5")
      (libsource (lib "eagle-import") (part "G6L-1F-DC4.5"))
    )
    (comp (ref "K74")
      (value "G6L-1F-DC4.5")
      (footprint "eagle-import:G6L-1F-DC4.5")
      (libsource (lib "eagle-import") (part "G6L-1F-DC4.5"))
    )
    (comp (ref "K75")
      (value "G6L-1F-DC4.5")
      (footprint "eagle-import:G6L-1F-DC4.5")
      (libsource (lib "eagle-import") (part "G6L-1F-DC4.5"))
    )
    (comp (ref "K76")
      (value "G6L-1F-DC4.5")
      (footprint "eagle-import:G6L-1F-DC4.5")
      (libsource (lib "eagle-import") (part "G6L-1F-DC4.5"))
    )
    (comp (ref "K77")
      (value "G6L-1F-DC4.5")
      (footprint "eagle-import:G6L-1F-DC4.5")
      (libsource (lib "eagle-import") (part "G6L-1F-DC4.5"))
    )
    (comp (ref "K78")
      (value "G6L-1F-DC4.5")
      (footprint "eagle-import:G6L-1F-DC4.5")
      (libsource (lib "eagle-import") (part "G6L-1F-DC4.5"))
    )
    (comp (ref "K79")
      (value "G6L-1F-DC4.5")
      (footprint "eagle-import:G6L-1F-DC4.5")
      (libsource (lib "eagle-import") (part "G6L-1F-DC4.5"))
    )
    (comp (ref "K80")
      (value "G6L-1F-DC4.5")
      (footprint "eagle-import:G6L-1F-DC4.5")
      (libsource (lib "eagle-import") (part "G6L-1F-DC4.5"))
    )
    (comp (ref "K81")
      (value "G6L-1F-DC4.5")
      (footprint "eagle-import:G6L-1F-DC4.5")
      (libsource (lib "eagle-import") (part "G6L-1F-DC4.5"))
    )
    (comp (ref "K82")
      (value "G6L-1F-DC4.5")
      (footprint "eagle-import:G6L-1F-DC4.5")
      (libsource (lib "eagle-import") (part "G6L-1F-DC4.5"))
    )
    (comp (ref "K83")
      (value "G6L-1F-DC4.5")
      (footprint "eagle-import:G6L-1F-DC4.5")
      (libsource (lib "eagle-import") (part "G6L-1F-DC4.5"))
    )
    (comp (ref "K84")
      (value "G6L-1F-DC4.5")
      (footprint "eagle-import:G6L-1F-DC4.5")
      (libsource (lib "eagle-import") (part "G6L-1F-DC4.5"))
    )
    (comp (ref "K85")
      (value "G6L-1F-DC4.5")
      (footprint "eagle-import:G6L-1F-DC4.5")
      (libsource (lib "eagle-import") (part "G6L-1F-DC4.5"))
    )
    (comp (ref "K86")
      (value "G6L-1F-DC4.5")
      (footprint "eagle-import:G6L-1F-DC4.5")
      (libsource (lib "eagle-import") (part "G6L-1F-DC4.5"))
    )
    (comp (ref "K87")
      (value "G6L-1F-DC4.5")
      (footprint "eagle-import:G6L-1F-DC4.5")
      (libsource (lib "eagle-import") (part "G6L-1F-DC4.5"))
    )
    (comp (ref "K88")
      (value "G6L-1F-DC4.5")
      (footprint "eagle-import:G6L-1F-DC4.5")
      (libsource (lib "eagle-import") (part "G6L-1F-DC4.5"))
    )
    (comp (ref "K89")
      (value "G6L-1F-DC4.5")
      (footprint "eagle-import:G6L-1F-DC4.5")
      (libsource (lib "eagle-import") (part "G6L-1F-DC4.5"))
    )
    (comp (ref "K90")
      (value "G6L-1F-DC4.5")
      (footprint "eagle-import:G6L-1F-DC4.5")
      (libsource (lib "eagle-import") (part "G6L-1F-DC4.5"))
    )
    (comp (ref "K91")
      (value "G6L-1F-DC4.5")
      (footprint "eagle-import:G6L-1F-DC4.5")
      (libsource (lib "eagle-import") (part "G6L-1F-DC4.5"))
    )
    (comp (ref "K92")
      (value "G6L-1F-DC4.5")
      (footprint "eagle-import:G6L-1F-DC4.5")
      (libsource (lib "eagle-import") (part "G6L-1F-DC4.5"))
    )
    (comp (ref "K93")
      (value "G6L-1F-DC4.5")
      (footprint "eagle-import:G6L-1F-DC4.5")
      (libsource (lib "eagle-import") (part "G6L-1F-DC4.5"))
    )
    (comp (ref "K94")
      (value "G6L-1F-DC4.5")
      (footprint "eagle-import:G6L-1F-DC4.5")
      (libsource (lib "eagle-import") (part "G6L-1F-DC4.5"))
    )
    (comp (ref "K95")
      (value "G6L-1F-DC4.5")
      (footprint "eagle-import:G6L-1F-DC4.5")
      (libsource (lib "eagle-import") (part "G6L-1F-DC4.5"))
    )
    (comp (ref "K96")
      (value "G6L-1F-DC4.5")
      (footprint "eagle-import:G6L-1F-DC4.5")
      (libsource (lib "eagle-import") (part "G6L-1F-DC4.5"))
    )
    (comp (ref "K97")
      (value "G6L-1F-DC4.5")
      (footprint "eagle-import:G6L-1F-DC4.5")
      (libsource (lib "eagle-import") (part "G6L-1F-DC4.5"))
    )
    (comp (ref "K98")
      (value "G6L-1F-DC4.5")
      (footprint "eagle-import:G6L-1F-DC4.5")
      (libsource (lib "eagle-import") (part "G6L-1F-DC4.5"))
    )
    (comp (ref "K99")
      (value "G6L-1F-DC4.5")
      (footprint "eagle-import:G6L-1F-DC4.5")
      (libsource (lib "eagle-import") (part "G6L-1F-DC4.5"))
    )
    (comp (ref "K100")
      (value "G6L-1F-DC4.5")
      (footprint "eagle-import:G6L-1F-DC4.5")
      (libsource (lib "eagle-import") (part "G6L-1F-DC4.5"))
    )
    (comp (ref "K101")
      (value "G6L-1F-DC4.5")
      (footprint "eagle-import:G6L-1F-DC4.5")
      (libsource (lib "eagle-import") (part "G6L-1F-DC4.5"))
    )
    (comp (ref "K102")
      (value "G6L-1F-DC4.5")
      (footprint "eagle-import:G6L-1F-DC4.5")
      (libsource (lib "eagle-import") (part "G6L-1F-DC4.5"))
    )
    (comp (ref "K103")
      (value "G6L-1F-DC4.5")
      (footprint "eagle-import:G6L-1F-DC4.5")
      (libsource (lib "eagle-import") (part "G6L-1F-DC4.5"))
    )
    (comp (ref "K104")
      (value "G6L-1F-DC4.5")
      (footprint "eagle-import:G6L-1F-DC4.5")
      (libsource (lib "eagle-import") (part "G6L-1F-DC4.5"))
    )
    (comp (ref "K105")
      (value "G6L-1F-DC4.5")
      (footprint "eagle-import:G6L-1F-DC4.5")
      (libsource (lib "eagle-import") (part "G6L-1F-DC4.5"))
    )
    (comp (ref "K106")
      (value "G6L-1F-DC4.5")
      (footprint "eagle-import:G6L-1F-DC4.5")
      (libsource (lib "eagle-import") (part "G6L-1F-DC4.5"))
    )
    (comp (ref "K107")
      (value "G6L-1F-DC4.5")
      (footprint "eagle-import:G6L-1F-DC4.5")
      (libsource (lib "eagle-import") (part "G6L-1F-DC4.5"))
    )
    (comp (ref "K108")
      (value "G6L-1F-DC4.5")
      (footprint "eagle-import:G6L-1F-DC4.5")
      (libsource (lib "eagle-import") (part "G6L-1F-DC4.5"))
    )
    (comp (ref "K109")
      (value "G6L-1F-DC4.5")
      (footprint "eagle-import:G6L-1F-DC4.5")
      (libsource (lib "eagle-import") (part "G6L-1F-DC4.5"))
    )
    (comp (ref "K110")
      (value "G6L-1F-DC4.5")
      (footprint "eagle-import:G6L-1F-DC4.5")
      (libsource (lib "eagle-import") (part "G6L-1F-DC4.5"))
    )
    (comp (ref "K111")
      (value "G6L-1F-DC4.5")
      (footprint "eagle-import:G6L-1F-DC4.5")
      (libsource (lib "eagle-import") (part "G6L-1F-DC4.5"))
    )
    (comp (ref "K112")
      (value "G6L-1F-DC4.5")
      (footprint "eagle-import:G6L-1F-DC4.5")
      (libsource (lib "eagle-import") (part "G6L-1F-DC4.5"))
    )
    (comp (ref "K113")
      (value "G6L-1F-DC4.5")
      (footprint "eagle-import:G6L-1F-DC4.5")
      (libsource (lib "eagle-import") (part "G6L-1F-DC4.5"))
    )
    (comp (ref "K114")
      (value "G6L-1F-DC4.5")
      (footprint "eagle-import:G6L-1F-DC4.5")
      (libsource (lib "eagle-import") (part "G6L-1F-DC4.5"))
    )
    (comp (ref "K115")
      (value "G6L-1F-DC4.5")
      (footprint "eagle-import:G6L-1F-DC4.5")
      (libsource (lib "eagle-import") (part "G6L-1F-DC4.5"))
    )
    (comp (ref "K116")
      (value "G6L-1F-DC4.5")
      (footprint "eagle-import:G6L-1F-DC4.5")
      (libsource (lib "eagle-import") (part "G6L-1F-DC4.5"))
    )
    (comp (ref "K117")
      (value "G6L-1F-DC4.5")
      (footprint "eagle-import:G6L-1F-DC4.5")
      (libsource (lib "eagle-import") (part "G6L-1F-DC4.5"))
    )
    (comp (ref "K118")
      (value "G6L-1F-DC4.5")
      (footprint "eagle-import:G6L-1F-DC4.5")
      (libsource (lib "eagle-import") (part "G6L-1F-DC4.5"))
    )
    (comp (ref "K119")
      (value "G6L-1F-DC4.5")
      (footprint "eagle-import:G6L-1F-DC4.5")
      (libsource (lib "eagle-import") (part "G6L-1F-DC4.5"))
    )
    (comp (ref "K120")
      (value "G6L-1F-DC4.5")
      (footprint "eagle-import:G6L-1F-DC4.5")
      (libsource (lib "eagle-import") (part "G6L-1F-DC4.5"))
    )
    (comp (ref "K121")
      (value "G6L-1F-DC4.5")
      (footprint "eagle-import:G6L-1F-DC4.5")
      (libsource (lib "eagle-import") (part "G6L-1F-DC4.5"))
    )
    (comp (ref "K122")
      (value "G6L-1F-DC4.5")
      (footprint "eagle-import:G6L-1F-DC4.5")
      (libsource (lib "eagle-import") (part "G6L-1F-DC4.5"))
    )
    (comp (ref "K123")
      (value "G6L-1F-DC4.5")
      (footprint "eagle-import:G6L-1F-DC4.5")
      (libsource (lib "eagle-import") (part "G6L-1F-DC4.5"))
    )
    (comp (ref "K124")
      (value "G6L-1F-DC4.5")
      (footprint "eagle-import:G6L-1F-DC4.5")
      (libsource (lib "eagle-import") (part "G6L-1F-DC4.5"))
    )
    (comp (ref "K125")
      (value "G6L-1F-DC4.5")
      (footprint "eagle-import:G6L-1F-DC4.5")
      (libsource (lib "eagle-import") (part "G6L-1F-DC4.5"))
    )
    (comp (ref "K126")
      (value "G6L-1F-DC4.5")
      (footprint "eagle-import:G6L-1F-DC4.5")
      (libsource (lib "eagle-import") (part "G6L-1F-DC4.5"))
    )
    (comp (ref "K127")
      (value "G6L-1F-DC4.5")
      (footprint "eagle-import:G6L-1F-DC4.5")
      (libsource (lib "eagle-import") (part "G6L-1F-DC4.5"))
    )
    (comp (ref "C5")
      (value "4.7uF")
      (footprint "eagle-import:C0603")
      (fields (field (name "MANUFACTURER_PART_NUMBER") "CL10A475KA8NQNC"))
      (libsource (lib "eagle-import") (part "resistor_348_C-USC0603"))
    )
    (comp (ref "C6")
      (value ".1uF")
      (footprint "eagle-import:C0402")
      (fields (field (name "MANUFACTURER_PART_NUMBER") "CL05A105KO5NNNC"))
      (libsource (lib "eagle-import") (part "resistor_348_C-USC0402"))
    )
    (comp (ref "C7")
      (value "10uF")
      (footprint "eagle-import:C0805")
      (fields (field (name "MANUFACTURER_PART_NUMBER") "CL21A106KAYNNNE"))
      (libsource (lib "eagle-import") (part "C-USC0805"))
    )
    (comp (ref "C8")
      (value "1uF")
      (footprint "eagle-import:C0402")
      (fields (field (name "MANUFACTURER_PART_NUMBER") "CL05A105KO5NNNC"))
      (libsource (lib "eagle-import") (part "resistor_348_C-USC0402"))
    )
    (comp (ref "C9")
      (value "1uF")
      (footprint "eagle-import:C0402")
      (fields (field (name "MANUFACTURER_PART_NUMBER") "CL05A105KO5NNNC"))
      (libsource (lib "eagle-import") (part "resistor_348_C-USC0402"))
    )
    (comp (ref "C10")
      (value "10uF")
      (footprint "eagle-import:C0805")
      (fields (field (name "MANUFACTURER_PART_NUMBER") "CL21A106KAYNNNE"))
      (libsource (lib "eagle-import") (part "C-USC0805"))
    )
    (comp (ref "C11")
      (value "10uF")
      (footprint "eagle-import:C0805")
      (fields (field (name "MANUFACTURER_PART_NUMBER") "CL21A106KAYNNNE"))
      (libsource (lib "eagle-import") (part "C-USC0805"))
    )
    (comp (ref "C12")
      (value "10uF")
      (footprint "eagle-import:C0805")
      (fields (field (name "MANUFACTURER_PART_NUMBER") "CL21A106KAYNNNE"))
      (libsource (lib "eagle-import") (part "C-USC0805"))
    )
    (comp (ref "C46")
      (value "0.1uF")
      (footprint "eagle-import:C0402")
      (fields (field (name "MANUFACTURER_PART_NUMBER") "CL05B104KO5NNNC"))
      (libsource (lib "eagle-import") (part "resistor_348_C-USC0402"))
    )
    (comp (ref "D1")
      (value "XZCBD53W-8")
      (footprint "eagle-import:DIOC1608X70N")
      (libsource (lib "eagle-import") (part "XZCBD53W-8"))
    )
    (comp (ref "D2")
      (value "XZCBD53W-8")
      (footprint "eagle-import:DIOC1608X70N")
      (libsource (lib "eagle-import") (part "XZCBD53W-8"))
    )
    (comp (ref "J6")
      (value "CT3151")
      (footprint "eagle-import:CONN_CT3151")
      (fields
        (field (name "MANUFACTURER_PART_NUMBER") "CT3151SP-9")
        (field (name "COPYRIGHT") "Copyright (C) 2021 Ultra Librarian. All rights reserved.")
      )
      (libsource (lib "eagle-import") (part "CT3151"))
    )
    (comp (ref "J7")
      (value "CT3151")
      (footprint "eagle-import:CONN_CT3151")
      (fields
        (field (name "MANUFACTURER_PART_NUMBER") "CT3151SP-9")
        (field (name "COPYRIGHT") "Copyright (C) 2021 Ultra Librarian. All rights reserved.")
      )
      (libsource (lib "eagle-import") (part "CT3151"))
    )
    (comp (ref "J8")
      (value "CT3151")
      (footprint "eagle-import:CONN_CT3151")
      (fields
        (field (name "MANUFACTURER_PART_NUMBER") "CT3151SP-9")
        (field (name "COPYRIGHT") "Copyright (C) 2021 Ultra Librarian. All rights reserved.")
      )
      (libsource (lib "eagle-import") (part "CT3151"))
    )
    (comp (ref "R9")
      (value "1k")
      (footprint "eagle-import:R0402")
      (fields (field (name "MANUFACTURER_PART_NUMBER") "CRG0402F1K0"))
      (libsource (lib "eagle-import") (part "resistor_348_R-US_R0402"))
    )
    (comp (ref "R10")
      (value "5.1k")
      (footprint "eagle-import:R0402")
      (fields (field (name "MANUFACTURER_PART_NUMBER") "RC0402FR-075K1L"))
      (libsource (lib "eagle-import") (part "resistor_348_R-US_R0402"))
    )
    (comp (ref "R11")
      (value "5.1k")
      (footprint "eagle-import:R0402")
      (fields (field (name "MANUFACTURER_PART_NUMBER") "RC0402FR-075K1L"))
      (libsource (lib "eagle-import") (part "resistor_348_R-US_R0402"))
    )
    (comp (ref "R12")
      (value "47.5k")
      (footprint "eagle-import:R0402")
      (fields (field (name "MANUFACTURER_PART_NUMBER") "RMCF0402FT47K5"))
      (libsource (lib "eagle-import") (part "resistor_348_R-US_R0402"))
    )
    (comp (ref "R13")
      (value "22.1k")
      (footprint "eagle-import:R0402")
      (fields (field (name "MANUFACTURER_PART_NUMBER") "RC0402FR-0722K1L"))
      (libsource (lib "eagle-import") (part "resistor_348_R-US_R0402"))
    )
    (comp (ref "R33")
      (value "220")
      (footprint "eagle-import:R0603")
      (fields (field (name "MANUFACTURER_PART_NUMBER") "RC1608F221CS"))
      (libsource (lib "eagle-import") (part "R-US_R0603"))
    )
    (comp (ref "R34")
      (value "360")
      (footprint "eagle-import:R0603")
      (fields (field (name "MANUFACTURER_PART_NUMBER") "RC0603FR-07360RL"))
      (libsource (lib "eagle-import") (part "R-US_R0603"))
    )
    (comp (ref "R35")
      (value "220")
      (footprint "eagle-import:R0603")
      (fields (field (name "MANUFACTURER_PART_NUMBER") "RC1608F221CS"))
      (libsource (lib "eagle-import") (part "R-US_R0603"))
    )
    (comp (ref "R36")
      (value "680")
      (footprint "eagle-import:R0603")
      (fields (field (name "MANUFACTURER_PART_NUMBER") "RC0603FR-07680RL"))
      (libsource (lib "eagle-import") (part "R-US_R0603"))
    )
    (comp (ref "R37")
      (value "1")
      (footprint "eagle-import:R0603")
      (fields (field (name "MANUFACTURER_PART_NUMBER") "RC0603FR-071RL"))
      (libsource (lib "eagle-import") (part "R-US_R0603"))
    )
    (comp (ref "R38")
      (value "1")
      (footprint "eagle-import:R0603")
      (fields (field (name "MANUFACTURER_PART_NUMBER") "RC0603FR-071RL"))
      (libsource (lib "eagle-import") (part "R-US_R0603"))
    )
    (comp (ref "S1")
      (value "100DP1T2B4M7QE")
      (footprint "eagle-import:100DP1T2B4M7QE_EWI")
      (fields (field (name "COPYRIGHT") "Copyright (C) 2021 Ultra Librarian. All rights reserved."))
      (libsource (lib "eagle-import") (part "100DP1T2B4M7QE"))
    )
    (comp (ref "U$131")
      (value "3PIN_UART_HEADER")
      (footprint "eagle-import:HDRV3W64P254_1X3_1016X277X854B")
      (libsource (lib "eagle-import") (part "3PIN_UART_HEADER"))
    )
    (comp (ref "U2")
      (value "CP2102N-A02-GQFN24R")
      (footprint "eagle-import:QFN24_SIL")
      (fields (field (name "COPYRIGHT") "Copyright (C) 2021 Ultra Librarian. All rights reserved."))
      (libsource (lib "eagle-import") (part "CP2102N-A02-GQFN24R"))
    )
    (comp (ref "U3")
      (value "NCP1117XXA")
      (footprint "eagle-import:TO230P990X240-4N")
      (fields (field (name "MFR") "on semi") (field (name "MANUFACTURER_PART_NUMBER") "NCP1117IDTAT4G"))
      (libsource (lib "eagle-import") (part "NCP1117XXA"))
    )
    (comp (ref "U4")
      (value "NCP1117XXA")
      (footprint "eagle-import:TO230P990X240-4N")
      (fields (field (name "MFR") "on semi") (field (name "MANUFACTURER_PART_NUMBER") "NCP1117IDTAT4G"))
      (libsource (lib "eagle-import") (part "NCP1117XXA"))
    )
    (comp (ref "U6")
      (value "TPD4E001RDBVR")
      (footprint "eagle-import:DBV6")
      (fields (field (name "COPYRIGHT") "Copyright (C) 2021 Ultra Librarian. All rights reserved."))
      (libsource (lib "eagle-import") (part "TPD4E001RDBVR"))
    )
    (comp (ref "X1")
      (value "2171790001")
      (footprint "eagle-import:2171790001_MOL")
      (fields (field (name "COPYRIGHT") "Copyright (C) 2021 Ultra Librarian. All rights reserved."))
      (libsource (lib "eagle-import") (part "2171790001"))
    )
    (comp (ref "X3")
      (value "SJ1-3523NG")
      (footprint "eagle-import:CUI_SJ1-3523NG")
      (fields (field (name "MANUFACTURER") "CUI"))
      (libsource (lib "eagle-import") (part "SJ1-3523NG"))
    )
    (comp (ref "X4")
      (value "SJ1-3523NG")
      (footprint "eagle-import:CUI_SJ1-3523NG")
      (fields (field (name "MANUFACTURER") "CUI"))
      (libsource (lib "eagle-import") (part "SJ1-3523NG"))
    )
    (comp (ref "X5")
      (value "SJ1-3523NG")
      (footprint "eagle-import:CUI_SJ1-3523NG")
      (fields (field (name "MANUFACTURER") "CUI"))
      (libsource (lib "eagle-import") (part "SJ1-3523NG"))
    )
    (comp (ref "C14")
      (value "1uF")
      (footprint "eagle-import:C0402")
      (fields (field (name "MANUFACTURER_PART_NUMBER") "CL05A105KO5NNNC"))
      (libsource (lib "eagle-import") (part "resistor_348_C-USC0402"))
    )
    (comp (ref "C15")
      (value "1uF")
      (footprint "eagle-import:C0402")
      (fields (field (name "MANUFACTURER_PART_NUMBER") "CL05A105KO5NNNC"))
      (libsource (lib "eagle-import") (part "resistor_348_C-USC0402"))
    )
    (comp (ref "C16")
      (value "1uF")
      (footprint "eagle-import:C0402")
      (fields (field (name "MANUFACTURER_PART_NUMBER") "CL05A105KO5NNNC"))
      (libsource (lib "eagle-import") (part "resistor_348_C-USC0402"))
    )
    (comp (ref "C17")
      (value "1uF")
      (footprint "eagle-import:C0402")
      (fields (field (name "MANUFACTURER_PART_NUMBER") "CL05A105KO5NNNC"))
      (libsource (lib "eagle-import") (part "resistor_348_C-USC0402"))
    )
    (comp (ref "C18")
      (value "1uF")
      (footprint "eagle-import:C0402")
      (fields (field (name "MANUFACTURER_PART_NUMBER") "CL05A105KO5NNNC"))
      (libsource (lib "eagle-import") (part "resistor_348_C-USC0402"))
    )
    (comp (ref "C19")
      (value "1uF")
      (footprint "eagle-import:C0402")
      (fields (field (name "MANUFACTURER_PART_NUMBER") "CL05A105KO5NNNC"))
      (libsource (lib "eagle-import") (part "resistor_348_C-USC0402"))
    )
    (comp (ref "C20")
      (value "1uF")
      (footprint "eagle-import:C0402")
      (fields (field (name "MANUFACTURER_PART_NUMBER") "CL05A105KO5NNNC"))
      (libsource (lib "eagle-import") (part "resistor_348_C-USC0402"))
    )
    (comp (ref "C21")
      (value "1uF")
      (footprint "eagle-import:C0402")
      (fields (field (name "MANUFACTURER_PART_NUMBER") "CL05A105KO5NNNC"))
      (libsource (lib "eagle-import") (part "resistor_348_C-USC0402"))
    )
    (comp (ref "C22")
      (value "1uF")
      (footprint "eagle-import:C0402")
      (fields (field (name "MANUFACTURER_PART_NUMBER") "CL05A105KO5NNNC"))
      (libsource (lib "eagle-import") (part "resistor_348_C-USC0402"))
    )
    (comp (ref "C23")
      (value "1uF")
      (footprint "eagle-import:C0402")
      (fields (field (name "MANUFACTURER_PART_NUMBER") "CL05A105KO5NNNC"))
      (libsource (lib "eagle-import") (part "resistor_348_C-USC0402"))
    )
    (comp (ref "C24")
      (value "1uF")
      (footprint "eagle-import:C0402")
      (fields (field (name "MANUFACTURER_PART_NUMBER") "CL05A105KO5NNNC"))
      (libsource (lib "eagle-import") (part "resistor_348_C-USC0402"))
    )
    (comp (ref "C25")
      (value "1uF")
      (footprint "eagle-import:C0402")
      (fields (field (name "MANUFACTURER_PART_NUMBER") "CL05A105KO5NNNC"))
      (libsource (lib "eagle-import") (part "resistor_348_C-USC0402"))
    )
    (comp (ref "C26")
      (value "1uF")
      (footprint "eagle-import:C0402")
      (fields (field (name "MANUFACTURER_PART_NUMBER") "CL05A105KO5NNNC"))
      (libsource (lib "eagle-import") (part "resistor_348_C-USC0402"))
    )
    (comp (ref "C27")
      (value "1uF")
      (footprint "eagle-import:C0402")
      (fields (field (name "MANUFACTURER_PART_NUMBER") "CL05A105KO5NNNC"))
      (libsource (lib "eagle-import") (part "resistor_348_C-USC0402"))
    )
    (comp (ref "C28")
      (value "1uF")
      (footprint "eagle-import:C0402")
      (fields (field (name "MANUFACTURER_PART_NUMBER") "CL05A105KO5NNNC"))
      (libsource (lib "eagle-import") (part "resistor_348_C-USC0402"))
    )
    (comp (ref "C29")
      (value "1uF")
      (footprint "eagle-import:C0402")
      (fields (field (name "MANUFACTURER_PART_NUMBER") "CL05A105KO5NNNC"))
      (libsource (lib "eagle-import") (part "resistor_348_C-USC0402"))
    )
    (comp (ref "C30")
      (value "1uF")
      (footprint "eagle-import:C0402")
      (fields (field (name "MANUFACTURER_PART_NUMBER") "CL05A105KO5NNNC"))
      (libsource (lib "eagle-import") (part "resistor_348_C-USC0402"))
    )
    (comp (ref "C31")
      (value "1uF")
      (footprint "eagle-import:C0402")
      (fields (field (name "MANUFACTURER_PART_NUMBER") "CL05A105KO5NNNC"))
      (libsource (lib "eagle-import") (part "resistor_348_C-USC0402"))
    )
    (comp (ref "C32")
      (value "1uF")
      (footprint "eagle-import:C0402")
      (fields (field (name "MANUFACTURER_PART_NUMBER") "CL05A105KO5NNNC"))
      (libsource (lib "eagle-import") (part "resistor_348_C-USC0402"))
    )
    (comp (ref "C33")
      (value "1uF")
      (footprint "eagle-import:C0402")
      (fields (field (name "MANUFACTURER_PART_NUMBER") "CL05A105KO5NNNC"))
      (libsource (lib "eagle-import") (part "resistor_348_C-USC0402"))
    )
    (comp (ref "C34")
      (value "1uF")
      (footprint "eagle-import:C0402")
      (fields (field (name "MANUFACTURER_PART_NUMBER") "CL05A105KO5NNNC"))
      (libsource (lib "eagle-import") (part "resistor_348_C-USC0402"))
    )
    (comp (ref "C35")
      (value "1uF")
      (footprint "eagle-import:C0402")
      (fields (field (name "MANUFACTURER_PART_NUMBER") "CL05A105KO5NNNC"))
      (libsource (lib "eagle-import") (part "resistor_348_C-USC0402"))
    )
    (comp (ref "C36")
      (value "1uF")
      (footprint "eagle-import:C0402")
      (fields (field (name "MANUFACTURER_PART_NUMBER") "CL05A105KO5NNNC"))
      (libsource (lib "eagle-import") (part "resistor_348_C-USC0402"))
    )
    (comp (ref "C37")
      (value "1uF")
      (footprint "eagle-import:C0402")
      (fields (field (name "MANUFACTURER_PART_NUMBER") "CL05A105KO5NNNC"))
      (libsource (lib "eagle-import") (part "resistor_348_C-USC0402"))
    )
    (comp (ref "C38")
      (value "1uF")
      (footprint "eagle-import:C0402")
      (fields (field (name "MANUFACTURER_PART_NUMBER") "CL05A105KO5NNNC"))
      (libsource (lib "eagle-import") (part "resistor_348_C-USC0402"))
    )
    (comp (ref "C39")
      (value "1uF")
      (footprint "eagle-import:C0402")
      (fields (field (name "MANUFACTURER_PART_NUMBER") "CL05A105KO5NNNC"))
      (libsource (lib "eagle-import") (part "resistor_348_C-USC0402"))
    )
    (comp (ref "C40")
      (value "1uF")
      (footprint "eagle-import:C0402")
      (fields (field (name "MANUFACTURER_PART_NUMBER") "CL05A105KO5NNNC"))
      (libsource (lib "eagle-import") (part "resistor_348_C-USC0402"))
    )
    (comp (ref "C41")
      (value "1uF")
      (footprint "eagle-import:C0402")
      (fields (field (name "MANUFACTURER_PART_NUMBER") "CL05A105KO5NNNC"))
      (libsource (lib "eagle-import") (part "resistor_348_C-USC0402"))
    )
    (comp (ref "C42")
      (value "1uF")
      (footprint "eagle-import:C0402")
      (fields (field (name "MANUFACTURER_PART_NUMBER") "CL05A105KO5NNNC"))
      (libsource (lib "eagle-import") (part "resistor_348_C-USC0402"))
    )
    (comp (ref "C43")
      (value "1uF")
      (footprint "eagle-import:C0402")
      (fields (field (name "MANUFACTURER_PART_NUMBER") "CL05A105KO5NNNC"))
      (libsource (lib "eagle-import") (part "resistor_348_C-USC0402"))
    )
    (comp (ref "C44")
      (value "1uF")
      (footprint "eagle-import:C0402")
      (fields (field (name "MANUFACTURER_PART_NUMBER") "CL05A105KO5NNNC"))
      (libsource (lib "eagle-import") (part "resistor_348_C-USC0402"))
    )
    (comp (ref "C45")
      (value "1uF")
      (footprint "eagle-import:C0402")
      (fields (field (name "MANUFACTURER_PART_NUMBER") "CL05A105KO5NNNC"))
      (libsource (lib "eagle-import") (part "resistor_348_C-USC0402"))
    )
    (comp (ref "U100")
      (value "MIC5891YWM-TR")
      (footprint "eagle-import:SOIC-16_WM_MCH")
      (fields (field (name "COPYRIGHT") "Copyright (C) 2021 Ultra Librarian. All rights reserved."))
      (libsource (lib "eagle-import") (part "MIC5891YWM-TR"))
    )
    (comp (ref "U101")
      (value "MIC5891YWM-TR")
      (footprint "eagle-import:SOIC-16_WM_MCH")
      (fields (field (name "COPYRIGHT") "Copyright (C) 2021 Ultra Librarian. All rights reserved."))
      (libsource (lib "eagle-import") (part "MIC5891YWM-TR"))
    )
    (comp (ref "U102")
      (value "MIC5891YWM-TR")
      (footprint "eagle-import:SOIC-16_WM_MCH")
      (fields (field (name "COPYRIGHT") "Copyright (C) 2021 Ultra Librarian. All rights reserved."))
      (libsource (lib "eagle-import") (part "MIC5891YWM-TR"))
    )
    (comp (ref "U103")
      (value "MIC5891YWM-TR")
      (footprint "eagle-import:SOIC-16_WM_MCH")
      (fields (field (name "COPYRIGHT") "Copyright (C) 2021 Ultra Librarian. All rights reserved."))
      (libsource (lib "eagle-import") (part "MIC5891YWM-TR"))
    )
    (comp (ref "U104")
      (value "MIC5891YWM-TR")
      (footprint "eagle-import:SOIC-16_WM_MCH")
      (fields (field (name "COPYRIGHT") "Copyright (C) 2021 Ultra Librarian. All rights reserved."))
      (libsource (lib "eagle-import") (part "MIC5891YWM-TR"))
    )
    (comp (ref "U105")
      (value "MIC5891YWM-TR")
      (footprint "eagle-import:SOIC-16_WM_MCH")
      (fields (field (name "COPYRIGHT") "Copyright (C) 2021 Ultra Librarian. All rights reserved."))
      (libsource (lib "eagle-import") (part "MIC5891YWM-TR"))
    )
    (comp (ref "U106")
      (value "MIC5891YWM-TR")
      (footprint "eagle-import:SOIC-16_WM_MCH")
      (fields (field (name "COPYRIGHT") "Copyright (C) 2021 Ultra Librarian. All rights reserved."))
      (libsource (lib "eagle-import") (part "MIC5891YWM-TR"))
    )
    (comp (ref "U107")
      (value "MIC5891YWM-TR")
      (footprint "eagle-import:SOIC-16_WM_MCH")
      (fields (field (name "COPYRIGHT") "Copyright (C) 2021 Ultra Librarian. All rights reserved."))
      (libsource (lib "eagle-import") (part "MIC5891YWM-TR"))
    )
    (comp (ref "U108")
      (value "MIC5891YWM-TR")
      (footprint "eagle-import:SOIC-16_WM_MCH")
      (fields (field (name "COPYRIGHT") "Copyright (C) 2021 Ultra Librarian. All rights reserved."))
      (libsource (lib "eagle-import") (part "MIC5891YWM-TR"))
    )
    (comp (ref "U109")
      (value "MIC5891YWM-TR")
      (footprint "eagle-import:SOIC-16_WM_MCH")
      (fields (field (name "COPYRIGHT") "Copyright (C) 2021 Ultra Librarian. All rights reserved."))
      (libsource (lib "eagle-import") (part "MIC5891YWM-TR"))
    )
    (comp (ref "U110")
      (value "MIC5891YWM-TR")
      (footprint "eagle-import:SOIC-16_WM_MCH")
      (fields (field (name "COPYRIGHT") "Copyright (C) 2021 Ultra Librarian. All rights reserved."))
      (libsource (lib "eagle-import") (part "MIC5891YWM-TR"))
    )
    (comp (ref "U111")
      (value "MIC5891YWM-TR")
      (footprint "eagle-import:SOIC-16_WM_MCH")
      (fields (field (name "COPYRIGHT") "Copyright (C) 2021 Ultra Librarian. All rights reserved."))
      (libsource (lib "eagle-import") (part "MIC5891YWM-TR"))
    )
    (comp (ref "U112")
      (value "MIC5891YWM-TR")
      (footprint "eagle-import:SOIC-16_WM_MCH")
      (fields (field (name "COPYRIGHT") "Copyright (C) 2021 Ultra Librarian. All rights reserved."))
      (libsource (lib "eagle-import") (part "MIC5891YWM-TR"))
    )
    (comp (ref "U113")
      (value "MIC5891YWM-TR")
      (footprint "eagle-import:SOIC-16_WM_MCH")
      (fields (field (name "COPYRIGHT") "Copyright (C) 2021 Ultra Librarian. All rights reserved."))
      (libsource (lib "eagle-import") (part "MIC5891YWM-TR"))
    )
    (comp (ref "U114")
      (value "MIC5891YWM-TR")
      (footprint "eagle-import:SOIC-16_WM_MCH")
      (fields (field (name "COPYRIGHT") "Copyright (C) 2021 Ultra Librarian. All rights reserved."))
      (libsource (lib "eagle-import") (part "MIC5891YWM-TR"))
    )
    (comp (ref "U115")
      (value "MIC5891YWM-TR")
      (footprint "eagle-import:SOIC-16_WM_MCH")
      (fields (field (name "COPYRIGHT") "Copyright (C) 2021 Ultra Librarian. All rights reserved."))
      (libsource (lib "eagle-import") (part "MIC5891YWM-TR"))
    )
    (comp (ref "C13")
      (value "0.01uF")
      (footprint "eagle-import:C0402")
      (fields (field (name "MANUFACTURER_PART_NUMBER") "GCM155R71H103KA55D"))
      (libsource (lib "eagle-import") (part "resistor_348_C-USC0402"))
    )
    (comp (ref "C47")
      (value "100n")
      (footprint "eagle-import:C0402")
      (fields (field (name "MANUFACTURER_PART_NUMBER") "CL05B104KO5NNNC"))
      (libsource (lib "eagle-import") (part "resistor_348_C-USC0402"))
    )
    (comp (ref "C101")
      (value "0.1uF")
      (footprint "eagle-import:C0402")
      (fields (field (name "MANUFACTURER_PART_NUMBER") "CL05B104KO5NNNC"))
      (libsource (lib "eagle-import") (part "resistor_348_C-USC0402"))
    )
    (comp (ref "C102")
      (value "0.1uF")
      (footprint "eagle-import:C0402")
      (fields (field (name "MANUFACTURER_PART_NUMBER") "CL05B104KO5NNNC"))
      (libsource (lib "eagle-import") (part "resistor_348_C-USC0402"))
    )
    (comp (ref "C103")
      (value "0.01uF")
      (footprint "eagle-import:C0402")
      (fields (field (name "MANUFACTURER_PART_NUMBER") "GCM155R71H103KA55D"))
      (libsource (lib "eagle-import") (part "resistor_348_C-USC0402"))
    )
    (comp (ref "C104")
      (value "0.01uF")
      (footprint "eagle-import:C0402")
      (fields (field (name "MANUFACTURER_PART_NUMBER") "GCM155R71H103KA55D"))
      (libsource (lib "eagle-import") (part "resistor_348_C-USC0402"))
    )
    (comp (ref "C105")
      (value "1uF")
      (footprint "eagle-import:C0402")
      (fields (field (name "MANUFACTURER_PART_NUMBER") "CL05A105KO5NNNC"))
      (libsource (lib "eagle-import") (part "resistor_348_C-USC0402"))
    )
    (comp (ref "C106")
      (value "0.1uF")
      (footprint "eagle-import:C0402")
      (fields (field (name "MANUFACTURER_PART_NUMBER") "CL05B104KO5NNNC"))
      (libsource (lib "eagle-import") (part "resistor_348_C-USC0402"))
    )
    (comp (ref "C107")
      (value "0.1uF")
      (footprint "eagle-import:C0402")
      (fields (field (name "MANUFACTURER_PART_NUMBER") "CL05B104KO5NNNC"))
      (libsource (lib "eagle-import") (part "resistor_348_C-USC0402"))
    )
    (comp (ref "C108")
      (value "2.2uF")
      (footprint "eagle-import:C0603")
      (fields (field (name "MANUFACTURER_PART_NUMBER") "CL10A225KO8NNNC"))
      (libsource (lib "eagle-import") (part "resistor_348_C-USC0603"))
    )
    (comp (ref "C109")
      (value "0.1uF")
      (footprint "eagle-import:C0402")
      (fields (field (name "MANUFACTURER_PART_NUMBER") "CL05B104KO5NNNC"))
      (libsource (lib "eagle-import") (part "resistor_348_C-USC0402"))
    )
    (comp (ref "C110")
      (value "1uF")
      (footprint "eagle-import:C0402")
      (fields (field (name "MANUFACTURER_PART_NUMBER") "CL05A105KO5NNNC"))
      (libsource (lib "eagle-import") (part "resistor_348_C-USC0402"))
    )
    (comp (ref "R14")
      (value "10kohm")
      (footprint "eagle-import:R0402")
      (fields (field (name "MANUFACTURER_PART_NUMBER") "RC1005F103CS"))
      (libsource (lib "eagle-import") (part "resistor_348_R-US_R0402"))
    )
    (comp (ref "R32")
      (value "470ohm")
      (footprint "eagle-import:R0402")
      (fields (field (name "MANUFACTURER_PART_NUMBER") "RC0402JR-07470RL"))
      (libsource (lib "eagle-import") (part "resistor_348_R-US_R0402"))
    )
    (comp (ref "S2")
      (value "TE_FSM4JSMA")
      (footprint "eagle-import:TE_FSMJSMA")
      (fields (field (name "MFR") "TE connectivity") (field (name "MANUFACTURER_PART_NUMBER") "FSM4JSMA"))
      (libsource (lib "eagle-import") (part "TE_FSM4JSMA"))
    )
    (comp (ref "U1")
      (value "TM4C123GH6PMI")
      (footprint "eagle-import:PM0064A_N")
      (fields (field (name "COPYRIGHT") "Copyright (C) 2021 Ultra Librarian. All rights reserved."))
      (libsource (lib "eagle-import") (part "TM4C123GH6PMI"))
    )
    (comp (ref "U5")
      (value "ECS-2033-080-AU")
      (footprint "eagle-import:OSCCC250X200X110N")
      (libsource (lib "eagle-import") (part "ECS-2033-080-AU"))
    )
    (comp (ref "X2")
      (value "FTSH-105-01-F-DV-007-K-P")
      (footprint "eagle-import:FTSH-105-01-F-DV-007-K-P")
      (fields (field (name "MFR") "samtec"))
      (libsource (lib "eagle-import") (part "FTSH-105-01-F-DV-007-K-P"))
    )
  )
  (nets
    (net (code "1") (name "+5V") (class "Default")
      (node (ref "C18") (pin "1") (pinfunction "1_1") (pintype "passive"))
      (node (ref "C31") (pin "1") (pinfunction "1_1") (pintype "passive"))
      (node (ref "C32") (pin "1") (pinfunction "1_1") (pintype "passive"))
      (node (ref "C33") (pin "1") (pinfunction "1_1") (pintype "passive"))
      (node (ref "C34") (pin "1") (pinfunction "1_1") (pintype "passive"))
      (node (ref "C35") (pin "1") (pinfunction "1_1") (pintype "passive"))
      (node (ref "C36") (pin "1") (pinfunction "1_1") (pintype "passive"))
      (node (ref "C37") (pin "1") (pinfunction "1_1") (pintype "passive"))
      (node (ref "C38") (pin "1") (pinfunction "1_1") (pintype "passive"))
      (node (ref "C39") (pin "1") (pinfunction "1_1") (pintype "passive"))
      (node (ref "C40") (pin "1") (pinfunction "1_1") (pintype "passive"))
      (node (ref "C41") (pin "1") (pinfunction "1_1") (pintype "passive"))
      (node (ref "C42") (pin "1") (pinfunction "1_1") (pintype "passive"))
      (node (ref "C43") (pin "1") (pinfunction "1_1") (pintype "passive"))
      (node (ref "C44") (pin "1") (pinfunction "1_1") (pintype "passive"))
      (node (ref "C45") (pin "1") (pinfunction "1_1") (pintype "passive"))
      (node (ref "R35") (pin "2") (pinfunction "2_2") (pintype "passive"))
      (node (ref "R38") (pin "2") (pinfunction "2_2") (pintype "passive"))
      (node (ref "U100") (pin "13") (pinfunction "LOADSUPPLY_13") (pintype "passive"))
      (node (ref "U101") (pin "13") (pinfunction "LOADSUPPLY_13") (pintype "passive"))
      (node (ref "U102") (pin "13") (pinfunction "LOADSUPPLY_13") (pintype "passive"))
      (node (ref "U103") (pin "13") (pinfunction "LOADSUPPLY_13") (pintype "passive"))
      (node (ref "U104") (pin "13") (pinfunction "LOADSUPPLY_13") (pintype "passive"))
      (node (ref "U105") (pin "13") (pinfunction "LOADSUPPLY_13") (pintype "passive"))
      (node (ref "U106") (pin "13") (pinfunction "LOADSUPPLY_13") (pintype "passive"))
      (node (ref "U107") (pin "13") (pinfunction "LOADSUPPLY_13") (pintype "passive"))
      (node (ref "U108") (pin "13") (pinfunction "LOADSUPPLY_13") (pintype "passive"))
      (node (ref "U109") (pin "13") (pinfunction "LOADSUPPLY_13") (pintype "passive"))
      (node (ref "U110") (pin "13") (pinfunction "LOADSUPPLY_13") (pintype "passive"))
      (node (ref "U111") (pin "13") (pinfunction "LOADSUPPLY_13") (pintype "passive"))
      (node (ref "U112") (pin "13") (pinfunction "LOADSUPPLY_13") (pintype "passive"))
      (node (ref "U113") (pin "13") (pinfunction "LOADSUPPLY_13") (pintype "passive"))
      (node (ref "U114") (pin "13") (pinfunction "LOADSUPPLY_13") (pintype "passive"))
      (node (ref "U115") (pin "13") (pinfunction "LOADSUPPLY_13") (pintype "passive"))
      (node (ref "U3") (pin "2") (pinfunction "VOUT_2") (pintype "bidirectional"))
      (node (ref "U3") (pin "4") (pinfunction "VOUT_4") (pintype "bidirectional"))
    )
    (net (code "2") (name "+12V") (class "Default")
      (node (ref "C10") (pin "1") (pinfunction "1_1") (pintype "passive"))
      (node (ref "C7") (pin "1") (pinfunction "1_1") (pintype "passive"))
      (node (ref "J7") (pin "1") (pinfunction "1_1") (pintype "passive"))
      (node (ref "U3") (pin "3") (pinfunction "VIN_3") (pintype "bidirectional"))
      (node (ref "U4") (pin "3") (pinfunction "VIN_3") (pintype "bidirectional"))
    )
    (net (code "3") (name "AGND") (class "Default")
      (node (ref "J8") (pin "1") (pinfunction "1_1") (pintype "passive"))
      (node (ref "X101") (pin "1") (pinfunction "1_1") (pintype "bidirectional"))
      (node (ref "X101") (pin "3") (pinfunction "3_3") (pintype "bidirectional"))
      (node (ref "X101") (pin "M1") (pinfunction "M1_M1") (pintype "bidirectional"))
      (node (ref "X101") (pin "M2") (pinfunction "M2_M2") (pintype "bidirectional"))
      (node (ref "X102") (pin "1") (pinfunction "1_1") (pintype "bidirectional"))
      (node (ref "X102") (pin "3") (pinfunction "3_3") (pintype "bidirectional"))
      (node (ref "X102") (pin "M1") (pinfunction "M1_M1") (pintype "bidirectional"))
      (node (ref "X102") (pin "M2") (pinfunction "M2_M2") (pintype "bidirectional"))
      (node (ref "X103") (pin "1") (pinfunction "1_1") (pintype "bidirectional"))
      (node (ref "X103") (pin "3") (pinfunction "3_3") (pintype "bidirectional"))
      (node (ref "X103") (pin "M1") (pinfunction "M1_M1") (pintype "bidirectional"))
      (node (ref "X103") (pin "M2") (pinfunction "M2_M2") (pintype "bidirectional"))
      (node (ref "X104") (pin "1") (pinfunction "1_1") (pintype "bidirectional"))
      (node (ref "X104") (pin "3") (pinfunction "3_3") (pintype "bidirectional"))
      (node (ref "X104") (pin "M1") (pinfunction "M1_M1") (pintype "bidirectional"))
      (node (ref "X104") (pin "M2") (pinfunction "M2_M2") (pintype "bidirectional"))
      (node (ref "X105") (pin "1") (pinfunction "1_1") (pintype "bidirectional"))
      (node (ref "X105") (pin "3") (pinfunction "3_3") (pintype "bidirectional"))
      (node (ref "X105") (pin "M1") (pinfunction "M1_M1") (pintype "bidirectional"))
      (node (ref "X105") (pin "M2") (pinfunction "M2_M2") (pintype "bidirectional"))
      (node (ref "X106") (pin "1") (pinfunction "1_1") (pintype "bidirectional"))
      (node (ref "X106") (pin "3") (pinfunction "3_3") (pintype "bidirectional"))
      (node (ref "X106") (pin "M1") (pinfunction "M1_M1") (pintype "bidirectional"))
      (node (ref "X106") (pin "M2") (pinfunction "M2_M2") (pintype "bidirectional"))
      (node (ref "X107") (pin "1") (pinfunction "1_1") (pintype "bidirectional"))
      (node (ref "X107") (pin "3") (pinfunction "3_3") (pintype "bidirectional"))
      (node (ref "X107") (pin "M1") (pinfunction "M1_M1") (pintype "bidirectional"))
      (node (ref "X107") (pin "M2") (pinfunction "M2_M2") (pintype "bidirectional"))
      (node (ref "X108") (pin "1") (pinfunction "1_1") (pintype "bidirectional"))
      (node (ref "X108") (pin "3") (pinfunction "3_3") (pintype "bidirectional"))
      (node (ref "X108") (pin "M1") (pinfunction "M1_M1") (pintype "bidirectional"))
      (node (ref "X108") (pin "M2") (pinfunction "M2_M2") (pintype "bidirectional"))
      (node (ref "X111") (pin "1") (pinfunction "1_1") (pintype "bidirectional"))
      (node (ref "X111") (pin "3") (pinfunction "3_3") (pintype "bidirectional"))
      (node (ref "X111") (pin "M1") (pinfunction "M1_M1") (pintype "bidirectional"))
      (node (ref "X111") (pin "M2") (pinfunction "M2_M2") (pintype "bidirectional"))
      (node (ref "X112") (pin "1") (pinfunction "1_1") (pintype "bidirectional"))
      (node (ref "X112") (pin "3") (pinfunction "3_3") (pintype "bidirectional"))
      (node (ref "X112") (pin "M1") (pinfunction "M1_M1") (pintype "bidirectional"))
      (node (ref "X112") (pin "M2") (pinfunction "M2_M2") (pintype "bidirectional"))
      (node (ref "X113") (pin "1") (pinfunction "1_1") (pintype "bidirectional"))
      (node (ref "X113") (pin "3") (pinfunction "3_3") (pintype "bidirectional"))
      (node (ref "X113") (pin "M1") (pinfunction "M1_M1") (pintype "bidirectional"))
      (node (ref "X113") (pin "M2") (pinfunction "M2_M2") (pintype "bidirectional"))
      (node (ref "X114") (pin "1") (pinfunction "1_1") (pintype "bidirectional"))
      (node (ref "X114") (pin "3") (pinfunction "3_3") (pintype "bidirectional"))
      (node (ref "X114") (pin "M1") (pinfunction "M1_M1") (pintype "bidirectional"))
      (node (ref "X114") (pin "M2") (pinfunction "M2_M2") (pintype "bidirectional"))
    )
    (net (code "4") (name "BT1_0") (class "Default")
      (node (ref "U100") (pin "3") (pinfunction "SERIALDATAIN_3") (pintype "input"))
      (node (ref "U101") (pin "16") (pinfunction "SERIALDATAOUT_16") (pintype "output"))
    )
    (net (code "5") (name "BT2_1") (class "Default")
      (node (ref "U101") (pin "3") (pinfunction "SERIALDATAIN_3") (pintype "input"))
      (node (ref "U102") (pin "16") (pinfunction "SERIALDATAOUT_16") (pintype "output"))
    )
    (net (code "6") (name "BT3_2") (class "Default")
      (node (ref "U102") (pin "3") (pinfunction "SERIALDATAIN_3") (pintype "input"))
      (node (ref "U103") (pin "16") (pinfunction "SERIALDATAOUT_16") (pintype "output"))
    )
    (net (code "7") (name "BT4_3") (class "Default")
      (node (ref "U103") (pin "3") (pinfunction "SERIALDATAIN_3") (pintype "input"))
      (node (ref "U104") (pin "16") (pinfunction "SERIALDATAOUT_16") (pintype "output"))
    )
    (net (code "8") (name "BT5_4") (class "Default")
      (node (ref "U104") (pin "3") (pinfunction "SERIALDATAIN_3") (pintype "input"))
      (node (ref "U105") (pin "16") (pinfunction "SERIALDATAOUT_16") (pintype "output"))
    )
    (net (code "9") (name "BT6_5") (class "Default")
      (node (ref "U105") (pin "3") (pinfunction "SERIALDATAIN_3") (pintype "input"))
      (node (ref "U106") (pin "16") (pinfunction "SERIALDATAOUT_16") (pintype "output"))
    )
    (net (code "10") (name "BT7_6") (class "Default")
      (node (ref "U106") (pin "3") (pinfunction "SERIALDATAIN_3") (pintype "input"))
      (node (ref "U107") (pin "16") (pinfunction "SERIALDATAOUT_16") (pintype "output"))
    )
    (net (code "11") (name "BT8_7") (class "Default")
      (node (ref "U107") (pin "3") (pinfunction "SERIALDATAIN_3") (pintype "input"))
      (node (ref "U108") (pin "16") (pinfunction "SERIALDATAOUT_16") (pintype "output"))
    )
    (net (code "12") (name "BT9_8") (class "Default")
      (node (ref "U108") (pin "3") (pinfunction "SERIALDATAIN_3") (pintype "input"))
      (node (ref "U109") (pin "16") (pinfunction "SERIALDATAOUT_16") (pintype "output"))
    )
    (net (code "13") (name "BT10_9") (class "Default")
      (node (ref "U109") (pin "3") (pinfunction "SERIALDATAIN_3") (pintype "input"))
      (node (ref "U110") (pin "16") (pinfunction "SERIALDATAOUT_16") (pintype "output"))
    )
    (net (code "14") (name "BT11_10") (class "Default")
      (node (ref "U110") (pin "3") (pinfunction "SERIALDATAIN_3") (pintype "input"))
      (node (ref "U111") (pin "16") (pinfunction "SERIALDATAOUT_16") (pintype "output"))
    )
    (net (code "15") (name "BT12_11") (class "Default")
      (node (ref "U111") (pin "3") (pinfunction "SERIALDATAIN_3") (pintype "input"))
      (node (ref "U112") (pin "16") (pinfunction "SERIALDATAOUT_16") (pintype "output"))
    )
    (net (code "16") (name "BT13_12") (class "Default")
      (node (ref "U112") (pin "3") (pinfunction "SERIALDATAIN_3") (pintype "input"))
      (node (ref "U113") (pin "16") (pinfunction "SERIALDATAOUT_16") (pintype "output"))
    )
    (net (code "17") (name "BT14_13") (class "Default")
      (node (ref "U113") (pin "3") (pinfunction "SERIALDATAIN_3") (pintype "input"))
      (node (ref "U114") (pin "16") (pinfunction "SERIALDATAOUT_16") (pintype "output"))
    )
    (net (code "18") (name "BT15_14") (class "Default")
      (node (ref "U114") (pin "3") (pinfunction "SERIALDATAIN_3") (pintype "input"))
      (node (ref "U115") (pin "16") (pinfunction "SERIALDATAOUT_16") (pintype "output"))
    )
    (net (code "19") (name "D1A") (class "Default")
      (node (ref "R30") (pin "2") (pinfunction "2_2") (pintype "passive"))
      (node (ref "U30") (pin "17") (pinfunction "1A_17") (pintype "bidirectional"))
      (node (ref "U31") (pin "17") (pinfunction "1A_17") (pintype "bidirectional"))
      (node (ref "U32") (pin "17") (pinfunction "1A_17") (pintype "bidirectional"))
      (node (ref "U33") (pin "17") (pinfunction "1A_17") (pintype "bidirectional"))
      (node (ref "U34") (pin "17") (pinfunction "1A_17") (pintype "bidirectional"))
      (node (ref "U35") (pin "17") (pinfunction "1A_17") (pintype "bidirectional"))
      (node (ref "U36") (pin "17") (pinfunction "1A_17") (pintype "bidirectional"))
      (node (ref "U37") (pin "17") (pinfunction "1A_17") (pintype "bidirectional"))
      (node (ref "U38") (pin "17") (pinfunction "1A_17") (pintype "bidirectional"))
    )
    (net (code "20") (name "D1B") (class "Default")
      (node (ref "R15") (pin "1") (pinfunction "1_1") (pintype "passive"))
      (node (ref "U30") (pin "16") (pinfunction "1B_16") (pintype "bidirectional"))
      (node (ref "U31") (pin "16") (pinfunction "1B_16") (pintype "bidirectional"))
      (node (ref "U32") (pin "16") (pinfunction "1B_16") (pintype "bidirectional"))
      (node (ref "U33") (pin "16") (pinfunction "1B_16") (pintype "bidirectional"))
      (node (ref "U34") (pin "16") (pinfunction "1B_16") (pintype "bidirectional"))
      (node (ref "U35") (pin "16") (pinfunction "1B_16") (pintype "bidirectional"))
      (node (ref "U36") (pin "16") (pinfunction "1B_16") (pintype "bidirectional"))
      (node (ref "U37") (pin "16") (pinfunction "1B_16") (pintype "bidirectional"))
      (node (ref "U38") (pin "16") (pinfunction "1B_16") (pintype "bidirectional"))
    )
    (net (code "21") (name "D1C") (class "Default")
      (node (ref "R16") (pin "1") (pinfunction "1_1") (pintype "passive"))
      (node (ref "U30") (pin "4") (pinfunction "1C_4") (pintype "bidirectional"))
      (node (ref "U31") (pin "4") (pinfunction "1C_4") (pintype "bidirectional"))
      (node (ref "U32") (pin "4") (pinfunction "1C_4") (pintype "bidirectional"))
      (node (ref "U33") (pin "4") (pinfunction "1C_4") (pintype "bidirectional"))
      (node (ref "U34") (pin "4") (pinfunction "1C_4") (pintype "bidirectional"))
      (node (ref "U35") (pin "4") (pinfunction "1C_4") (pintype "bidirectional"))
      (node (ref "U36") (pin "4") (pinfunction "1C_4") (pintype "bidirectional"))
      (node (ref "U37") (pin "4") (pinfunction "1C_4") (pintype "bidirectional"))
      (node (ref "U38") (pin "4") (pinfunction "1C_4") (pintype "bidirectional"))
    )
    (net (code "22") (name "D1D") (class "Default")
      (node (ref "R17") (pin "1") (pinfunction "1_1") (pintype "passive"))
      (node (ref "U30") (pin "2") (pinfunction "1D_2") (pintype "bidirectional"))
      (node (ref "U31") (pin "2") (pinfunction "1D_2") (pintype "bidirectional"))
      (node (ref "U32") (pin "2") (pinfunction "1D_2") (pintype "bidirectional"))
      (node (ref "U33") (pin "2") (pinfunction "1D_2") (pintype "bidirectional"))
      (node (ref "U34") (pin "2") (pinfunction "1D_2") (pintype "bidirectional"))
      (node (ref "U35") (pin "2") (pinfunction "1D_2") (pintype "bidirectional"))
      (node (ref "U36") (pin "2") (pinfunction "1D_2") (pintype "bidirectional"))
      (node (ref "U37") (pin "2") (pinfunction "1D_2") (pintype "bidirectional"))
      (node (ref "U38") (pin "2") (pinfunction "1D_2") (pintype "bidirectional"))
    )
    (net (code "23") (name "D1DP") (class "Default")
      (node (ref "R21") (pin "1") (pinfunction "1_1") (pintype "passive"))
      (node (ref "U30") (pin "5") (pinfunction "1DP_5") (pintype "bidirectional"))
      (node (ref "U31") (pin "5") (pinfunction "1DP_5") (pintype "bidirectional"))
      (node (ref "U32") (pin "5") (pinfunction "1DP_5") (pintype "bidirectional"))
      (node (ref "U33") (pin "5") (pinfunction "1DP_5") (pintype "bidirectional"))
      (node (ref "U34") (pin "5") (pinfunction "1DP_5") (pintype "bidirectional"))
      (node (ref "U35") (pin "5") (pinfunction "1DP_5") (pintype "bidirectional"))
      (node (ref "U36") (pin "5") (pinfunction "1DP_5") (pintype "bidirectional"))
      (node (ref "U37") (pin "5") (pinfunction "1DP_5") (pintype "bidirectional"))
      (node (ref "U38") (pin "5") (pinfunction "1DP_5") (pintype "bidirectional"))
    )
    (net (code "24") (name "D1E") (class "Default")
      (node (ref "R18") (pin "1") (pinfunction "1_1") (pintype "passive"))
      (node (ref "U30") (pin "1") (pinfunction "1E_1") (pintype "bidirectional"))
      (node (ref "U31") (pin "1") (pinfunction "1E_1") (pintype "bidirectional"))
      (node (ref "U32") (pin "1") (pinfunction "1E_1") (pintype "bidirectional"))
      (node (ref "U33") (pin "1") (pinfunction "1E_1") (pintype "bidirectional"))
      (node (ref "U34") (pin "1") (pinfunction "1E_1") (pintype "bidirectional"))
      (node (ref "U35") (pin "1") (pinfunction "1E_1") (pintype "bidirectional"))
      (node (ref "U36") (pin "1") (pinfunction "1E_1") (pintype "bidirectional"))
      (node (ref "U37") (pin "1") (pinfunction "1E_1") (pintype "bidirectional"))
      (node (ref "U38") (pin "1") (pinfunction "1E_1") (pintype "bidirectional"))
    )
    (net (code "25") (name "D1F") (class "Default")
      (node (ref "R19") (pin "1") (pinfunction "1_1") (pintype "passive"))
      (node (ref "U30") (pin "19") (pinfunction "1F_19") (pintype "bidirectional"))
      (node (ref "U31") (pin "19") (pinfunction "1F_19") (pintype "bidirectional"))
      (node (ref "U32") (pin "19") (pinfunction "1F_19") (pintype "bidirectional"))
      (node (ref "U33") (pin "19") (pinfunction "1F_19") (pintype "bidirectional"))
      (node (ref "U34") (pin "19") (pinfunction "1F_19") (pintype "bidirectional"))
      (node (ref "U35") (pin "19") (pinfunction "1F_19") (pintype "bidirectional"))
      (node (ref "U36") (pin "19") (pinfunction "1F_19") (pintype "bidirectional"))
      (node (ref "U37") (pin "19") (pinfunction "1F_19") (pintype "bidirectional"))
      (node (ref "U38") (pin "19") (pinfunction "1F_19") (pintype "bidirectional"))
    )
    (net (code "26") (name "D1G") (class "Default")
      (node (ref "R20") (pin "1") (pinfunction "1_1") (pintype "passive"))
      (node (ref "U30") (pin "20") (pinfunction "1G_20") (pintype "bidirectional"))
      (node (ref "U31") (pin "20") (pinfunction "1G_20") (pintype "bidirectional"))
      (node (ref "U32") (pin "20") (pinfunction "1G_20") (pintype "bidirectional"))
      (node (ref "U33") (pin "20") (pinfunction "1G_20") (pintype "bidirectional"))
      (node (ref "U34") (pin "20") (pinfunction "1G_20") (pintype "bidirectional"))
      (node (ref "U35") (pin "20") (pinfunction "1G_20") (pintype "bidirectional"))
      (node (ref "U36") (pin "20") (pinfunction "1G_20") (pintype "bidirectional"))
      (node (ref "U37") (pin "20") (pinfunction "1G_20") (pintype "bidirectional"))
      (node (ref "U38") (pin "20") (pinfunction "1G_20") (pintype "bidirectional"))
    )
    (net (code "27") (name "D1HI") (class "Default")
      (node (ref "R1") (pin "1") (pinfunction "1_1") (pintype "passive"))
      (node (ref "U21") (pin "15") (pinfunction "QA_15") (pintype "bidirectional"))
    )
    (net (code "28") (name "D1PWR") (class "Default")
      (node (ref "R1") (pin "2") (pinfunction "2_2") (pintype "passive"))
      (node (ref "U31") (pin "13") (pinfunction "P$13_13") (pintype "bidirectional"))
      (node (ref "U31") (pin "18") (pinfunction "P$18_18") (pintype "bidirectional"))
      (node (ref "U31") (pin "3") (pinfunction "P$3_3") (pintype "bidirectional"))
      (node (ref "U31") (pin "8") (pinfunction "P$8_8") (pintype "bidirectional"))
    )
    (net (code "29") (name "D2A") (class "Default")
      (node (ref "R29") (pin "2") (pinfunction "2_2") (pintype "passive"))
      (node (ref "U30") (pin "12") (pinfunction "2A_12") (pintype "bidirectional"))
      (node (ref "U31") (pin "12") (pinfunction "2A_12") (pintype "bidirectional"))
      (node (ref "U32") (pin "12") (pinfunction "2A_12") (pintype "bidirectional"))
      (node (ref "U33") (pin "12") (pinfunction "2A_12") (pintype "bidirectional"))
      (node (ref "U34") (pin "12") (pinfunction "2A_12") (pintype "bidirectional"))
      (node (ref "U35") (pin "12") (pinfunction "2A_12") (pintype "bidirectional"))
      (node (ref "U36") (pin "12") (pinfunction "2A_12") (pintype "bidirectional"))
      (node (ref "U37") (pin "12") (pinfunction "2A_12") (pintype "bidirectional"))
      (node (ref "U38") (pin "12") (pinfunction "2A_12") (pintype "bidirectional"))
    )
    (net (code "30") (name "D2B") (class "Default")
      (node (ref "R22") (pin "1") (pinfunction "1_1") (pintype "passive"))
      (node (ref "U30") (pin "11") (pinfunction "2B_11") (pintype "bidirectional"))
      (node (ref "U31") (pin "11") (pinfunction "2B_11") (pintype "bidirectional"))
      (node (ref "U32") (pin "11") (pinfunction "2B_11") (pintype "bidirectional"))
      (node (ref "U33") (pin "11") (pinfunction "2B_11") (pintype "bidirectional"))
      (node (ref "U34") (pin "11") (pinfunction "2B_11") (pintype "bidirectional"))
      (node (ref "U35") (pin "11") (pinfunction "2B_11") (pintype "bidirectional"))
      (node (ref "U36") (pin "11") (pinfunction "2B_11") (pintype "bidirectional"))
      (node (ref "U37") (pin "11") (pinfunction "2B_11") (pintype "bidirectional"))
      (node (ref "U38") (pin "11") (pinfunction "2B_11") (pintype "bidirectional"))
    )
    (net (code "31") (name "D2C") (class "Default")
      (node (ref "R23") (pin "1") (pinfunction "1_1") (pintype "passive"))
      (node (ref "U30") (pin "9") (pinfunction "2C_9") (pintype "bidirectional"))
      (node (ref "U31") (pin "9") (pinfunction "2C_9") (pintype "bidirectional"))
      (node (ref "U32") (pin "9") (pinfunction "2C_9") (pintype "bidirectional"))
      (node (ref "U33") (pin "9") (pinfunction "2C_9") (pintype "bidirectional"))
      (node (ref "U34") (pin "9") (pinfunction "2C_9") (pintype "bidirectional"))
      (node (ref "U35") (pin "9") (pinfunction "2C_9") (pintype "bidirectional"))
      (node (ref "U36") (pin "9") (pinfunction "2C_9") (pintype "bidirectional"))
      (node (ref "U37") (pin "9") (pinfunction "2C_9") (pintype "bidirectional"))
      (node (ref "U38") (pin "9") (pinfunction "2C_9") (pintype "bidirectional"))
    )
    (net (code "32") (name "D2D") (class "Default")
      (node (ref "R24") (pin "1") (pinfunction "1_1") (pintype "passive"))
      (node (ref "U30") (pin "7") (pinfunction "2D_7") (pintype "bidirectional"))
      (node (ref "U31") (pin "7") (pinfunction "2D_7") (pintype "bidirectional"))
      (node (ref "U32") (pin "7") (pinfunction "2D_7") (pintype "bidirectional"))
      (node (ref "U33") (pin "7") (pinfunction "2D_7") (pintype "bidirectional"))
      (node (ref "U34") (pin "7") (pinfunction "2D_7") (pintype "bidirectional"))
      (node (ref "U35") (pin "7") (pinfunction "2D_7") (pintype "bidirectional"))
      (node (ref "U36") (pin "7") (pinfunction "2D_7") (pintype "bidirectional"))
      (node (ref "U37") (pin "7") (pinfunction "2D_7") (pintype "bidirectional"))
      (node (ref "U38") (pin "7") (pinfunction "2D_7") (pintype "bidirectional"))
    )
    (net (code "33") (name "D2DP") (class "Default")
      (node (ref "R28") (pin "1") (pinfunction "1_1") (pintype "passive"))
      (node (ref "U30") (pin "10") (pinfunction "2DP_10") (pintype "bidirectional"))
      (node (ref "U31") (pin "10") (pinfunction "2DP_10") (pintype "bidirectional"))
      (node (ref "U32") (pin "10") (pinfunction "2DP_10") (pintype "bidirectional"))
      (node (ref "U33") (pin "10") (pinfunction "2DP_10") (pintype "bidirectional"))
      (node (ref "U34") (pin "10") (pinfunction "2DP_10") (pintype "bidirectional"))
      (node (ref "U35") (pin "10") (pinfunction "2DP_10") (pintype "bidirectional"))
      (node (ref "U36") (pin "10") (pinfunction "2DP_10") (pintype "bidirectional"))
      (node (ref "U37") (pin "10") (pinfunction "2DP_10") (pintype "bidirectional"))
      (node (ref "U38") (pin "10") (pinfunction "2DP_10") (pintype "bidirectional"))
    )
    (net (code "34") (name "D2E") (class "Default")
      (node (ref "R25") (pin "1") (pinfunction "1_1") (pintype "passive"))
      (node (ref "U30") (pin "6") (pinfunction "2E_6") (pintype "bidirectional"))
      (node (ref "U31") (pin "6") (pinfunction "2E_6") (pintype "bidirectional"))
      (node (ref "U32") (pin "6") (pinfunction "2E_6") (pintype "bidirectional"))
      (node (ref "U33") (pin "6") (pinfunction "2E_6") (pintype "bidirectional"))
      (node (ref "U34") (pin "6") (pinfunction "2E_6") (pintype "bidirectional"))
      (node (ref "U35") (pin "6") (pinfunction "2E_6") (pintype "bidirectional"))
      (node (ref "U36") (pin "6") (pinfunction "2E_6") (pintype "bidirectional"))
      (node (ref "U37") (pin "6") (pinfunction "2E_6") (pintype "bidirectional"))
      (node (ref "U38") (pin "6") (pinfunction "2E_6") (pintype "bidirectional"))
    )
    (net (code "35") (name "D2F") (class "Default")
      (node (ref "R26") (pin "1") (pinfunction "1_1") (pintype "passive"))
      (node (ref "U30") (pin "14") (pinfunction "2F_14") (pintype "bidirectional"))
      (node (ref "U31") (pin "14") (pinfunction "2F_14") (pintype "bidirectional"))
      (node (ref "U32") (pin "14") (pinfunction "2F_14") (pintype "bidirectional"))
      (node (ref "U33") (pin "14") (pinfunction "2F_14") (pintype "bidirectional"))
      (node (ref "U34") (pin "14") (pinfunction "2F_14") (pintype "bidirectional"))
      (node (ref "U35") (pin "14") (pinfunction "2F_14") (pintype "bidirectional"))
      (node (ref "U36") (pin "14") (pinfunction "2F_14") (pintype "bidirectional"))
      (node (ref "U37") (pin "14") (pinfunction "2F_14") (pintype "bidirectional"))
      (node (ref "U38") (pin "14") (pinfunction "2F_14") (pintype "bidirectional"))
    )
    (net (code "36") (name "D2G") (class "Default")
      (node (ref "R27") (pin "1") (pinfunction "1_1") (pintype "passive"))
      (node (ref "U30") (pin "15") (pinfunction "2G_15") (pintype "bidirectional"))
      (node (ref "U31") (pin "15") (pinfunction "2G_15") (pintype "bidirectional"))
      (node (ref "U32") (pin "15") (pinfunction "2G_15") (pintype "bidirectional"))
      (node (ref "U33") (pin "15") (pinfunction "2G_15") (pintype "bidirectional"))
      (node (ref "U34") (pin "15") (pinfunction "2G_15") (pintype "bidirectional"))
      (node (ref "U35") (pin "15") (pinfunction "2G_15") (pintype "bidirectional"))
      (node (ref "U36") (pin "15") (pinfunction "2G_15") (pintype "bidirectional"))
      (node (ref "U37") (pin "15") (pinfunction "2G_15") (pintype "bidirectional"))
      (node (ref "U38") (pin "15") (pinfunction "2G_15") (pintype "bidirectional"))
    )
    (net (code "37") (name "D2HI") (class "Default")
      (node (ref "R2") (pin "1") (pinfunction "1_1") (pintype "passive"))
      (node (ref "U21") (pin "1") (pinfunction "QB_1") (pintype "bidirectional"))
    )
    (net (code "38") (name "D2PWR") (class "Default")
      (node (ref "R2") (pin "2") (pinfunction "2_2") (pintype "passive"))
      (node (ref "U32") (pin "13") (pinfunction "P$13_13") (pintype "bidirectional"))
      (node (ref "U32") (pin "18") (pinfunction "P$18_18") (pintype "bidirectional"))
      (node (ref "U32") (pin "3") (pinfunction "P$3_3") (pintype "bidirectional"))
      (node (ref "U32") (pin "8") (pinfunction "P$8_8") (pintype "bidirectional"))
    )
    (net (code "39") (name "D3HI") (class "Default")
      (node (ref "R3") (pin "1") (pinfunction "1_1") (pintype "passive"))
      (node (ref "U21") (pin "2") (pinfunction "QC_2") (pintype "bidirectional"))
    )
    (net (code "40") (name "D3PWR") (class "Default")
      (node (ref "R3") (pin "2") (pinfunction "2_2") (pintype "passive"))
      (node (ref "U33") (pin "13") (pinfunction "P$13_13") (pintype "bidirectional"))
      (node (ref "U33") (pin "18") (pinfunction "P$18_18") (pintype "bidirectional"))
      (node (ref "U33") (pin "3") (pinfunction "P$3_3") (pintype "bidirectional"))
      (node (ref "U33") (pin "8") (pinfunction "P$8_8") (pintype "bidirectional"))
    )
    (net (code "41") (name "D4HI") (class "Default")
      (node (ref "R5") (pin "1") (pinfunction "1_1") (pintype "passive"))
      (node (ref "U21") (pin "3") (pinfunction "QD_3") (pintype "bidirectional"))
    )
    (net (code "42") (name "D4PWR") (class "Default")
      (node (ref "R5") (pin "2") (pinfunction "2_2") (pintype "passive"))
      (node (ref "U34") (pin "13") (pinfunction "P$13_13") (pintype "bidirectional"))
      (node (ref "U34") (pin "18") (pinfunction "P$18_18") (pintype "bidirectional"))
      (node (ref "U34") (pin "3") (pinfunction "P$3_3") (pintype "bidirectional"))
      (node (ref "U34") (pin "8") (pinfunction "P$8_8") (pintype "bidirectional"))
    )
    (net (code "43") (name "D5HI") (class "Default")
      (node (ref "R4") (pin "1") (pinfunction "1_1") (pintype "passive"))
      (node (ref "U21") (pin "4") (pinfunction "QE_4") (pintype "bidirectional"))
    )
    (net (code "44") (name "D5PWR") (class "Default")
      (node (ref "R4") (pin "2") (pinfunction "2_2") (pintype "passive"))
      (node (ref "U35") (pin "13") (pinfunction "P$13_13") (pintype "bidirectional"))
      (node (ref "U35") (pin "18") (pinfunction "P$18_18") (pintype "bidirectional"))
      (node (ref "U35") (pin "3") (pinfunction "P$3_3") (pintype "bidirectional"))
      (node (ref "U35") (pin "8") (pinfunction "P$8_8") (pintype "bidirectional"))
    )
    (net (code "45") (name "D6HI") (class "Default")
      (node (ref "R6") (pin "1") (pinfunction "1_1") (pintype "passive"))
      (node (ref "U21") (pin "5") (pinfunction "QF_5") (pintype "bidirectional"))
    )
    (net (code "46") (name "D6PWR") (class "Default")
      (node (ref "R6") (pin "2") (pinfunction "2_2") (pintype "passive"))
      (node (ref "U36") (pin "13") (pinfunction "P$13_13") (pintype "bidirectional"))
      (node (ref "U36") (pin "18") (pinfunction "P$18_18") (pintype "bidirectional"))
      (node (ref "U36") (pin "3") (pinfunction "P$3_3") (pintype "bidirectional"))
      (node (ref "U36") (pin "8") (pinfunction "P$8_8") (pintype "bidirectional"))
    )
    (net (code "47") (name "D7HI") (class "Default")
      (node (ref "R7") (pin "1") (pinfunction "1_1") (pintype "passive"))
      (node (ref "U21") (pin "6") (pinfunction "QG_6") (pintype "bidirectional"))
    )
    (net (code "48") (name "D7PWR") (class "Default")
      (node (ref "R7") (pin "2") (pinfunction "2_2") (pintype "passive"))
      (node (ref "U37") (pin "13") (pinfunction "P$13_13") (pintype "bidirectional"))
      (node (ref "U37") (pin "18") (pinfunction "P$18_18") (pintype "bidirectional"))
      (node (ref "U37") (pin "3") (pinfunction "P$3_3") (pintype "bidirectional"))
      (node (ref "U37") (pin "8") (pinfunction "P$8_8") (pintype "bidirectional"))
    )
    (net (code "49") (name "D8HI") (class "Default")
      (node (ref "R8") (pin "1") (pinfunction "1_1") (pintype "passive"))
      (node (ref "U21") (pin "7") (pinfunction "QH_7") (pintype "bidirectional"))
    )
    (net (code "50") (name "D8PWR") (class "Default")
      (node (ref "R8") (pin "2") (pinfunction "2_2") (pintype "passive"))
      (node (ref "U38") (pin "13") (pinfunction "P$13_13") (pintype "bidirectional"))
      (node (ref "U38") (pin "18") (pinfunction "P$18_18") (pintype "bidirectional"))
      (node (ref "U38") (pin "3") (pinfunction "P$3_3") (pintype "bidirectional"))
      (node (ref "U38") (pin "8") (pinfunction "P$8_8") (pintype "bidirectional"))
    )
    (net (code "51") (name "DISP_CLK") (class "Default")
      (node (ref "U1") (pin "19") (pinfunction "PA2_SSI0CLK_19") (pintype "bidirectional"))
      (node (ref "U20") (pin "11") (pinfunction "SRCLK_11") (pintype "bidirectional"))
      (node (ref "U21") (pin "11") (pinfunction "SRCLK_11") (pintype "bidirectional"))
      (node (ref "U22") (pin "11") (pinfunction "SRCLK_11") (pintype "bidirectional"))
      (node (ref "U23") (pin "11") (pinfunction "SRCLK_11") (pintype "bidirectional"))
    )
    (net (code "52") (name "DISP_SER") (class "Default")
      (node (ref "U1") (pin "22") (pinfunction "PA5_SSI0TX_22") (pintype "bidirectional"))
      (node (ref "U20") (pin "14") (pinfunction "SER_14") (pintype "bidirectional"))
    )
    (net (code "53") (name "DISP_STRB") (class "Default")
      (node (ref "U1") (pin "21") (pinfunction "PA4_SSI0RX_21") (pintype "bidirectional"))
      (node (ref "U20") (pin "12") (pinfunction "RCLK_12") (pintype "bidirectional"))
      (node (ref "U21") (pin "12") (pinfunction "RCLK_12") (pintype "bidirectional"))
      (node (ref "U22") (pin "12") (pinfunction "RCLK_12") (pintype "bidirectional"))
      (node (ref "U23") (pin "12") (pinfunction "RCLK_12") (pintype "bidirectional"))
    )
    (net (code "54") (name "DISP_~{OE}") (class "Default")
      (node (ref "U1") (pin "20") (pinfunction "PA3_SSI0FSS_20") (pintype "bidirectional"))
      (node (ref "U20") (pin "13") (pinfunction "~{OE}_13") (pintype "bidirectional"))
      (node (ref "U21") (pin "13") (pinfunction "~{OE}_13") (pintype "bidirectional"))
      (node (ref "U22") (pin "13") (pinfunction "~{OE}_13") (pintype "bidirectional"))
      (node (ref "U23") (pin "13") (pinfunction "~{OE}_13") (pintype "bidirectional"))
    )
    (net (code "55") (name "DISP_~{SRCLR}") (class "Default")
      (node (ref "U1") (pin "23") (pinfunction "PA6_23") (pintype "bidirectional"))
      (node (ref "U20") (pin "10") (pinfunction "~{SRCLR}_10") (pintype "bidirectional"))
      (node (ref "U21") (pin "10") (pinfunction "~{SRCLR}_10") (pintype "bidirectional"))
      (node (ref "U22") (pin "10") (pinfunction "~{SRCLR}_10") (pintype "bidirectional"))
      (node (ref "U23") (pin "10") (pinfunction "~{SRCLR}_10") (pintype "bidirectional"))
    )
    (net (code "56") (name "DRIV_CLK") (class "Default")
      (node (ref "U1") (pin "61") (pinfunction "PD0_61") (pintype "bidirectional"))
      (node (ref "U100") (pin "2") (pinfunction "CLOCK_2") (pintype "passive"))
      (node (ref "U101") (pin "2") (pinfunction "CLOCK_2") (pintype "passive"))
      (node (ref "U102") (pin "2") (pinfunction "CLOCK_2") (pintype "passive"))
      (node (ref "U103") (pin "2") (pinfunction "CLOCK_2") (pintype "passive"))
      (node (ref "U104") (pin "2") (pinfunction "CLOCK_2") (pintype "passive"))
      (node (ref "U105") (pin "2") (pinfunction "CLOCK_2") (pintype "passive"))
      (node (ref "U106") (pin "2") (pinfunction "CLOCK_2") (pintype "passive"))
      (node (ref "U107") (pin "2") (pinfunction "CLOCK_2") (pintype "passive"))
      (node (ref "U108") (pin "2") (pinfunction "CLOCK_2") (pintype "passive"))
      (node (ref "U109") (pin "2") (pinfunction "CLOCK_2") (pintype "passive"))
      (node (ref "U110") (pin "2") (pinfunction "CLOCK_2") (pintype "passive"))
      (node (ref "U111") (pin "2") (pinfunction "CLOCK_2") (pintype "passive"))
      (node (ref "U112") (pin "2") (pinfunction "CLOCK_2") (pintype "passive"))
      (node (ref "U113") (pin "2") (pinfunction "CLOCK_2") (pintype "passive"))
      (node (ref "U114") (pin "2") (pinfunction "CLOCK_2") (pintype "passive"))
      (node (ref "U115") (pin "2") (pinfunction "CLOCK_2") (pintype "passive"))
    )
    (net (code "57") (name "DRIV_DATA") (class "Default")
      (node (ref "U1") (pin "64") (pinfunction "PD3_64") (pintype "bidirectional"))
      (node (ref "U115") (pin "3") (pinfunction "SERIALDATAIN_3") (pintype "input"))
    )
    (net (code "58") (name "DRIV_EN") (class "Default")
      (node (ref "U1") (pin "62") (pinfunction "PD1_62") (pintype "bidirectional"))
      (node (ref "U100") (pin "14") (pinfunction "OUTPUTENABLE_14") (pintype "passive"))
      (node (ref "U101") (pin "14") (pinfunction "OUTPUTENABLE_14") (pintype "passive"))
      (node (ref "U102") (pin "14") (pinfunction "OUTPUTENABLE_14") (pintype "passive"))
      (node (ref "U103") (pin "14") (pinfunction "OUTPUTENABLE_14") (pintype "passive"))
      (node (ref "U104") (pin "14") (pinfunction "OUTPUTENABLE_14") (pintype "passive"))
      (node (ref "U105") (pin "14") (pinfunction "OUTPUTENABLE_14") (pintype "passive"))
      (node (ref "U106") (pin "14") (pinfunction "OUTPUTENABLE_14") (pintype "passive"))
      (node (ref "U107") (pin "14") (pinfunction "OUTPUTENABLE_14") (pintype "passive"))
      (node (ref "U108") (pin "14") (pinfunction "OUTPUTENABLE_14") (pintype "passive"))
      (node (ref "U109") (pin "14") (pinfunction "OUTPUTENABLE_14") (pintype "passive"))
      (node (ref "U110") (pin "14") (pinfunction "OUTPUTENABLE_14") (pintype "passive"))
      (node (ref "U111") (pin "14") (pinfunction "OUTPUTENABLE_14") (pintype "passive"))
      (node (ref "U112") (pin "14") (pinfunction "OUTPUTENABLE_14") (pintype "passive"))
      (node (ref "U113") (pin "14") (pinfunction "OUTPUTENABLE_14") (pintype "passive"))
      (node (ref "U114") (pin "14") (pinfunction "OUTPUTENABLE_14") (pintype "passive"))
      (node (ref "U115") (pin "14") (pinfunction "OUTPUTENABLE_14") (pintype "passive"))
    )
    (net (code "59") (name "DRIV_STRB") (class "Default")
      (node (ref "U1") (pin "63") (pinfunction "PD2_63") (pintype "bidirectional"))
      (node (ref "U100") (pin "4") (pinfunction "STROBE_4") (pintype "passive"))
      (node (ref "U101") (pin "4") (pinfunction "STROBE_4") (pintype "passive"))
      (node (ref "U102") (pin "4") (pinfunction "STROBE_4") (pintype "passive"))
      (node (ref "U103") (pin "4") (pinfunction "STROBE_4") (pintype "passive"))
      (node (ref "U104") (pin "4") (pinfunction "STROBE_4") (pintype "passive"))
      (node (ref "U105") (pin "4") (pinfunction "STROBE_4") (pintype "passive"))
      (node (ref "U106") (pin "4") (pinfunction "STROBE_4") (pintype "passive"))
      (node (ref "U107") (pin "4") (pinfunction "STROBE_4") (pintype "passive"))
      (node (ref "U108") (pin "4") (pinfunction "STROBE_4") (pintype "passive"))
      (node (ref "U109") (pin "4") (pinfunction "STROBE_4") (pintype "passive"))
      (node (ref "U110") (pin "4") (pinfunction "STROBE_4") (pintype "passive"))
      (node (ref "U111") (pin "4") (pinfunction "STROBE_4") (pintype "passive"))
      (node (ref "U112") (pin "4") (pinfunction "STROBE_4") (pintype "passive"))
      (node (ref "U113") (pin "4") (pinfunction "STROBE_4") (pintype "passive"))
      (node (ref "U114") (pin "4") (pinfunction "STROBE_4") (pintype "passive"))
      (node (ref "U115") (pin "4") (pinfunction "STROBE_4") (pintype "passive"))
    )
    (net (code "60") (name "GND") (class "Default")
      (node (ref "C1") (pin "2") (pinfunction "2_2") (pintype "passive"))
      (node (ref "C10") (pin "2") (pinfunction "2_2") (pintype "passive"))
      (node (ref "C101") (pin "2") (pinfunction "2_2") (pintype "passive"))
      (node (ref "C102") (pin "2") (pinfunction "2_2") (pintype "passive"))
      (node (ref "C103") (pin "2") (pinfunction "2_2") (pintype "passive"))
      (node (ref "C104") (pin "2") (pinfunction "2_2") (pintype "passive"))
      (node (ref "C105") (pin "2") (pinfunction "2_2") (pintype "passive"))
      (node (ref "C106") (pin "2") (pinfunction "2_2") (pintype "passive"))
      (node (ref "C107") (pin "2") (pinfunction "2_2") (pintype "passive"))
      (node (ref "C108") (pin "2") (pinfunction "2_2") (pintype "passive"))
      (node (ref "C109") (pin "2") (pinfunction "2_2") (pintype "passive"))
      (node (ref "C11") (pin "2") (pinfunction "2_2") (pintype "passive"))
      (node (ref "C110") (pin "2") (pinfunction "2_2") (pintype "passive"))
      (node (ref "C12") (pin "2") (pinfunction "2_2") (pintype "passive"))
      (node (ref "C13") (pin "2") (pinfunction "2_2") (pintype "passive"))
      (node (ref "C14") (pin "2") (pinfunction "2_2") (pintype "passive"))
      (node (ref "C15") (pin "2") (pinfunction "2_2") (pintype "passive"))
      (node (ref "C16") (pin "2") (pinfunction "2_2") (pintype "passive"))
      (node (ref "C17") (pin "2") (pinfunction "2_2") (pintype "passive"))
      (node (ref "C18") (pin "2") (pinfunction "2_2") (pintype "passive"))
      (node (ref "C19") (pin "2") (pinfunction "2_2") (pintype "passive"))
      (node (ref "C2") (pin "2") (pinfunction "2_2") (pintype "passive"))
      (node (ref "C20") (pin "2") (pinfunction "2_2") (pintype "passive"))
      (node (ref "C21") (pin "2") (pinfunction "2_2") (pintype "passive"))
      (node (ref "C22") (pin "2") (pinfunction "2_2") (pintype "passive"))
      (node (ref "C23") (pin "2") (pinfunction "2_2") (pintype "passive"))
      (node (ref "C24") (pin "2") (pinfunction "2_2") (pintype "passive"))
      (node (ref "C25") (pin "2") (pinfunction "2_2") (pintype "passive"))
      (node (ref "C26") (pin "2") (pinfunction "2_2") (pintype "passive"))
      (node (ref "C27") (pin "2") (pinfunction "2_2") (pintype "passive"))
      (node (ref "C28") (pin "2") (pinfunction "2_2") (pintype "passive"))
      (node (ref "C29") (pin "2") (pinfunction "2_2") (pintype "passive"))
      (node (ref "C3") (pin "2") (pinfunction "2_2") (pintype "passive"))
      (node (ref "C30") (pin "2") (pinfunction "2_2") (pintype "passive"))
      (node (ref "C31") (pin "2") (pinfunction "2_2") (pintype "passive"))
      (node (ref "C32") (pin "2") (pinfunction "2_2") (pintype "passive"))
      (node (ref "C33") (pin "2") (pinfunction "2_2") (pintype "passive"))
      (node (ref "C34") (pin "2") (pinfunction "2_2") (pintype "passive"))
      (node (ref "C35") (pin "2") (pinfunction "2_2") (pintype "passive"))
      (node (ref "C36") (pin "2") (pinfunction "2_2") (pintype "passive"))
      (node (ref "C37") (pin "2") (pinfunction "2_2") (pintype "passive"))
      (node (ref "C38") (pin "2") (pinfunction "2_2") (pintype "passive"))
      (node (ref "C39") (pin "2") (pinfunction "2_2") (pintype "passive"))
      (node (ref "C4") (pin "2") (pinfunction "2_2") (pintype "passive"))
      (node (ref "C40") (pin "2") (pinfunction "2_2") (pintype "passive"))
      (node (ref "C41") (pin "2") (pinfunction "2_2") (pintype "passive"))
      (node (ref "C42") (pin "2") (pinfunction "2_2") (pintype "passive"))
      (node (ref "C43") (pin "2") (pinfunction "2_2") (pintype "passive"))
      (node (ref "C44") (pin "2") (pinfunction "2_2") (pintype "passive"))
      (node (ref "C45") (pin "2") (pinfunction "2_2") (pintype "passive"))
      (node (ref "C46") (pin "2") (pinfunction "2_2") (pintype "passive"))
      (node (ref "C47") (pin "2") (pinfunction "2_2") (pintype "passive"))
      (node (ref "C5") (pin "2") (pinfunction "2_2") (pintype "passive"))
      (node (ref "C6") (pin "2") (pinfunction "2_2") (pintype "passive"))
      (node (ref "C7") (pin "2") (pinfunction "2_2") (pintype "passive"))
      (node (ref "C8") (pin "2") (pinfunction "2_2") (pintype "passive"))
      (node (ref "C9") (pin "2") (pinfunction "2_2") (pintype "passive"))
      (node (ref "J6") (pin "1") (pinfunction "1_1") (pintype "passive"))
      (node (ref "K0") (pin "8") (pinfunction "COIL_LOW_8") (pintype "bidirectional"))
      (node (ref "K1") (pin "8") (pinfunction "COIL_LOW_8") (pintype "bidirectional"))
      (node (ref "K10") (pin "8") (pinfunction "COIL_LOW_8") (pintype "bidirectional"))
      (node (ref "K100") (pin "8") (pinfunction "COIL_LOW_8") (pintype "bidirectional"))
      (node (ref "K101") (pin "8") (pinfunction "COIL_LOW_8") (pintype "bidirectional"))
      (node (ref "K102") (pin "8") (pinfunction "COIL_LOW_8") (pintype "bidirectional"))
      (node (ref "K103") (pin "8") (pinfunction "COIL_LOW_8") (pintype "bidirectional"))
      (node (ref "K104") (pin "8") (pinfunction "COIL_LOW_8") (pintype "bidirectional"))
      (node (ref "K105") (pin "8") (pinfunction "COIL_LOW_8") (pintype "bidirectional"))
      (node (ref "K106") (pin "8") (pinfunction "COIL_LOW_8") (pintype "bidirectional"))
      (node (ref "K107") (pin "8") (pinfunction "COIL_LOW_8") (pintype "bidirectional"))
      (node (ref "K108") (pin "8") (pinfunction "COIL_LOW_8") (pintype "bidirectional"))
      (node (ref "K109") (pin "8") (pinfunction "COIL_LOW_8") (pintype "bidirectional"))
      (node (ref "K11") (pin "8") (pinfunction "COIL_LOW_8") (pintype "bidirectional"))
      (node (ref "K110") (pin "8") (pinfunction "COIL_LOW_8") (pintype "bidirectional"))
      (node (ref "K111") (pin "8") (pinfunction "COIL_LOW_8") (pintype "bidirectional"))
      (node (ref "K112") (pin "8") (pinfunction "COIL_LOW_8") (pintype "bidirectional"))
      (node (ref "K113") (pin "8") (pinfunction "COIL_LOW_8") (pintype "bidirectional"))
      (node (ref "K114") (pin "8") (pinfunction "COIL_LOW_8") (pintype "bidirectional"))
      (node (ref "K115") (pin "8") (pinfunction "COIL_LOW_8") (pintype "bidirectional"))
      (node (ref "K116") (pin "8") (pinfunction "COIL_LOW_8") (pintype "bidirectional"))
      (node (ref "K117") (pin "8") (pinfunction "COIL_LOW_8") (pintype "bidirectional"))
      (node (ref "K118") (pin "8") (pinfunction "COIL_LOW_8") (pintype "bidirectional"))
      (node (ref "K119") (pin "8") (pinfunction "COIL_LOW_8") (pintype "bidirectional"))
      (node (ref "K12") (pin "8") (pinfunction "COIL_LOW_8") (pintype "bidirectional"))
      (node (ref "K120") (pin "8") (pinfunction "COIL_LOW_8") (pintype "bidirectional"))
      (node (ref "K121") (pin "8") (pinfunction "COIL_LOW_8") (pintype "bidirectional"))
      (node (ref "K122") (pin "8") (pinfunction "COIL_LOW_8") (pintype "bidirectional"))
      (node (ref "K123") (pin "8") (pinfunction "COIL_LOW_8") (pintype "bidirectional"))
      (node (ref "K124") (pin "8") (pinfunction "COIL_LOW_8") (pintype "bidirectional"))
      (node (ref "K125") (pin "8") (pinfunction "COIL_LOW_8") (pintype "bidirectional"))
      (node (ref "K126") (pin "8") (pinfunction "COIL_LOW_8") (pintype "bidirectional"))
      (node (ref "K127") (pin "8") (pinfunction "COIL_LOW_8") (pintype "bidirectional"))
      (node (ref "K13") (pin "8") (pinfunction "COIL_LOW_8") (pintype "bidirectional"))
      (node (ref "K14") (pin "8") (pinfunction "COIL_LOW_8") (pintype "bidirectional"))
      (node (ref "K15") (pin "8") (pinfunction "COIL_LOW_8") (pintype "bidirectional"))
      (node (ref "K16") (pin "8") (pinfunction "COIL_LOW_8") (pintype "bidirectional"))
      (node (ref "K17") (pin "8") (pinfunction "COIL_LOW_8") (pintype "bidirectional"))
      (node (ref "K18") (pin "8") (pinfunction "COIL_LOW_8") (pintype "bidirectional"))
      (node (ref "K19") (pin "8") (pinfunction "COIL_LOW_8") (pintype "bidirectional"))
      (node (ref "K2") (pin "8") (pinfunction "COIL_LOW_8") (pintype "bidirectional"))
      (node (ref "K20") (pin "8") (pinfunction "COIL_LOW_8") (pintype "bidirectional"))
      (node (ref "K21") (pin "8") (pinfunction "COIL_LOW_8") (pintype "bidirectional"))
      (node (ref "K22") (pin "8") (pinfunction "COIL_LOW_8") (pintype "bidirectional"))
      (node (ref "K23") (pin "8") (pinfunction "COIL_LOW_8") (pintype "bidirectional"))
      (node (ref "K24") (pin "8") (pinfunction "COIL_LOW_8") (pintype "bidirectional"))
      (node (ref "K25") (pin "8") (pinfunction "COIL_LOW_8") (pintype "bidirectional"))
      (node (ref "K26") (pin "8") (pinfunction "COIL_LOW_8") (pintype "bidirectional"))
      (node (ref "K27") (pin "8") (pinfunction "COIL_LOW_8") (pintype "bidirectional"))
      (node (ref "K28") (pin "8") (pinfunction "COIL_LOW_8") (pintype "bidirectional"))
      (node (ref "K29") (pin "8") (pinfunction "COIL_LOW_8") (pintype "bidirectional"))
      (node (ref "K3") (pin "8") (pinfunction "COIL_LOW_8") (pintype "bidirectional"))
      (node (ref "K30") (pin "8") (pinfunction "COIL_LOW_8") (pintype "bidirectional"))
      (node (ref "K31") (pin "8") (pinfunction "COIL_LOW_8") (pintype "bidirectional"))
      (node (ref "K32") (pin "8") (pinfunction "COIL_LOW_8") (pintype "bidirectional"))
      (node (ref "K33") (pin "8") (pinfunction "COIL_LOW_8") (pintype "bidirectional"))
      (node (ref "K34") (pin "8") (pinfunction "COIL_LOW_8") (pintype "bidirectional"))
      (node (ref "K35") (pin "8") (pinfunction "COIL_LOW_8") (pintype "bidirectional"))
      (node (ref "K36") (pin "8") (pinfunction "COIL_LOW_8") (pintype "bidirectional"))
      (node (ref "K37") (pin "8") (pinfunction "COIL_LOW_8") (pintype "bidirectional"))
      (node (ref "K38") (pin "8") (pinfunction "COIL_LOW_8") (pintype "bidirectional"))
      (node (ref "K39") (pin "8") (pinfunction "COIL_LOW_8") (pintype "bidirectional"))
      (node (ref "K4") (pin "8") (pinfunction "COIL_LOW_8") (pintype "bidirectional"))
      (node (ref "K40") (pin "8") (pinfunction "COIL_LOW_8") (pintype "bidirectional"))
      (node (ref "K41") (pin "8") (pinfunction "COIL_LOW_8") (pintype "bidirectional"))
      (node (ref "K42") (pin "8") (pinfunction "COIL_LOW_8") (pintype "bidirectional"))
      (node (ref "K43") (pin "8") (pinfunction "COIL_LOW_8") (pintype "bidirectional"))
      (node (ref "K44") (pin "8") (pinfunction "COIL_LOW_8") (pintype "bidirectional"))
      (node (ref "K45") (pin "8") (pinfunction "COIL_LOW_8") (pintype "bidirectional"))
      (node (ref "K46") (pin "8") (pinfunction "COIL_LOW_8") (pintype "bidirectional"))
      (node (ref "K47") (pin "8") (pinfunction "COIL_LOW_8") (pintype "bidirectional"))
      (node (ref "K48") (pin "8") (pinfunction "COIL_LOW_8") (pintype "bidirectional"))
      (node (ref "K49") (pin "8") (pinfunction "COIL_LOW_8") (pintype "bidirectional"))
      (node (ref "K5") (pin "8") (pinfunction "COIL_LOW_8") (pintype "bidirectional"))
      (node (ref "K50") (pin "8") (pinfunction "COIL_LOW_8") (pintype "bidirectional"))
      (node (ref "K51") (pin "8") (pinfunction "COIL_LOW_8") (pintype "bidirectional"))
      (node (ref "K52") (pin "8") (pinfunction "COIL_LOW_8") (pintype "bidirectional"))
      (node (ref "K53") (pin "8") (pinfunction "COIL_LOW_8") (pintype "bidirectional"))
      (node (ref "K54") (pin "8") (pinfunction "COIL_LOW_8") (pintype "bidirectional"))
      (node (ref "K55") (pin "8") (pinfunction "COIL_LOW_8") (pintype "bidirectional"))
      (node (ref "K56") (pin "8") (pinfunction "COIL_LOW_8") (pintype "bidirectional"))
      (node (ref "K57") (pin "8") (pinfunction "COIL_LOW_8") (pintype "bidirectional"))
      (node (ref "K58") (pin "8") (pinfunction "COIL_LOW_8") (pintype "bidirectional"))
      (node (ref "K59") (pin "8") (pinfunction "COIL_LOW_8") (pintype "bidirectional"))
      (node (ref "K6") (pin "8") (pinfunction "COIL_LOW_8") (pintype "bidirectional"))
      (node (ref "K60") (pin "8") (pinfunction "COIL_LOW_8") (pintype "bidirectional"))
      (node (ref "K61") (pin "8") (pinfunction "COIL_LOW_8") (pintype "bidirectional"))
      (node (ref "K62") (pin "8") (pinfunction "COIL_LOW_8") (pintype "bidirectional"))
      (node (ref "K63") (pin "8") (pinfunction "COIL_LOW_8") (pintype "bidirectional"))
      (node (ref "K64") (pin "8") (pinfunction "COIL_LOW_8") (pintype "bidirectional"))
      (node (ref "K65") (pin "8") (pinfunction "COIL_LOW_8") (pintype "bidirectional"))
      (node (ref "K66") (pin "8") (pinfunction "COIL_LOW_8") (pintype "bidirectional"))
      (node (ref "K67") (pin "8") (pinfunction "COIL_LOW_8") (pintype "bidirectional"))
      (node (ref "K68") (pin "8") (pinfunction "COIL_LOW_8") (pintype "bidirectional"))
      (node (ref "K69") (pin "8") (pinfunction "COIL_LOW_8") (pintype "bidirectional"))
      (node (ref "K7") (pin "8") (pinfunction "COIL_LOW_8") (pintype "bidirectional"))
      (node (ref "K70") (pin "8") (pinfunction "COIL_LOW_8") (pintype "bidirectional"))
      (node (ref "K71") (pin "8") (pinfunction "COIL_LOW_8") (pintype "bidirectional"))
      (node (ref "K72") (pin "8") (pinfunction "COIL_LOW_8") (pintype "bidirectional"))
      (node (ref "K73") (pin "8") (pinfunction "COIL_LOW_8") (pintype "bidirectional"))
      (node (ref "K74") (pin "8") (pinfunction "COIL_LOW_8") (pintype "bidirectional"))
      (node (ref "K75") (pin "8") (pinfunction "COIL_LOW_8") (pintype "bidirectional"))
      (node (ref "K76") (pin "8") (pinfunction "COIL_LOW_8") (pintype "bidirectional"))
      (node (ref "K77") (pin "8") (pinfunction "COIL_LOW_8") (pintype "bidirectional"))
      (node (ref "K78") (pin "8") (pinfunction "COIL_LOW_8") (pintype "bidirectional"))
      (node (ref "K79") (pin "8") (pinfunction "COIL_LOW_8") (pintype "bidirectional"))
      (node (ref "K8") (pin "8") (pinfunction "COIL_LOW_8") (pintype "bidirectional"))
      (node (ref "K80") (pin "8") (pinfunction "COIL_LOW_8") (pintype "bidirectional"))
      (node (ref "K81") (pin "8") (pinfunction "COIL_LOW_8") (pintype "bidirectional"))
      (node (ref "K82") (pin "8") (pinfunction "COIL_LOW_8") (pintype "bidirectional"))
      (node (ref "K83") (pin "8") (pinfunction "COIL_LOW_8") (pintype "bidirectional"))
      (node (ref "K84") (pin "8") (pinfunction "COIL_LOW_8") (pintype "bidirectional"))
      (node (ref "K85") (pin "8") (pinfunction "COIL_LOW_8") (pintype "bidirectional"))
      (node (ref "K86") (pin "8") (pinfunction "COIL_LOW_8") (pintype "bidirectional"))
      (node (ref "K87") (pin "8") (pinfunction "COIL_LOW_8") (pintype "bidirectional"))
      (node (ref "K88") (pin "8") (pinfunction "COIL_LOW_8") (pintype "bidirectional"))
      (node (ref "K89") (pin "8") (pinfunction "COIL_LOW_8") (pintype "bidirectional"))
      (node (ref "K9") (pin "8") (pinfunction "COIL_LOW_8") (pintype "bidirectional"))
      (node (ref "K90") (pin "8") (pinfunction "COIL_LOW_8") (pintype "bidirectional"))
      (node (ref "K91") (pin "8") (pinfunction "COIL_LOW_8") (pintype "bidirectional"))
      (node (ref "K92") (pin "8") (pinfunction "COIL_LOW_8") (pintype "bidirectional"))
      (node (ref "K93") (pin "8") (pinfunction "COIL_LOW_8") (pintype "bidirectional"))
      (node (ref "K94") (pin "8") (pinfunction "COIL_LOW_8") (pintype "bidirectional"))
      (node (ref "K95") (pin "8") (pinfunction "COIL_LOW_8") (pintype "bidirectional"))
      (node (ref "K96") (pin "8") (pinfunction "COIL_LOW_8") (pintype "bidirectional"))
      (node (ref "K97") (pin "8") (pinfunction "COIL_LOW_8") (pintype "bidirectional"))
      (node (ref "K98") (pin "8") (pinfunction "COIL_LOW_8") (pintype "bidirectional"))
      (node (ref "K99") (pin "8") (pinfunction "COIL_LOW_8") (pintype "bidirectional"))
      (node (ref "R10") (pin "1") (pinfunction "1_1") (pintype "passive"))
      (node (ref "R11") (pin "1") (pinfunction "1_1") (pintype "passive"))
      (node (ref "R12") (pin "1") (pinfunction "1_1") (pintype "passive"))
      (node (ref "R34") (pin "1") (pinfunction "1_1") (pintype "passive"))
      (node (ref "R36") (pin "1") (pinfunction "1_1") (pintype "passive"))
      (node (ref "S2") (pin "P$3") (pinfunction "P$3_P$3") (pintype "bidirectional"))
      (node (ref "S2") (pin "P$4") (pinfunction "P$4_P$4") (pintype "bidirectional"))
      (node (ref "U$131") (pin "1") (pinfunction "GND_1") (pintype "bidirectional"))
      (node (ref "U1") (pin "12") (pinfunction "GND_2_12") (pintype "power_in"))
      (node (ref "U1") (pin "27") (pinfunction "GND_3_27") (pintype "power_in"))
      (node (ref "U1") (pin "3") (pinfunction "GNDA_3") (pintype "power_in"))
      (node (ref "U1") (pin "35") (pinfunction "GNDX_35") (pintype "power_in"))
      (node (ref "U1") (pin "39") (pinfunction "GND_4_39") (pintype "power_in"))
      (node (ref "U1") (pin "55") (pinfunction "GND_55") (pintype "power_in"))
      (node (ref "U100") (pin "1") (pinfunction "GROUND_1") (pintype "power_in"))
      (node (ref "U101") (pin "1") (pinfunction "GROUND_1") (pintype "power_in"))
      (node (ref "U102") (pin "1") (pinfunction "GROUND_1") (pintype "power_in"))
      (node (ref "U103") (pin "1") (pinfunction "GROUND_1") (pintype "power_in"))
      (node (ref "U104") (pin "1") (pinfunction "GROUND_1") (pintype "power_in"))
      (node (ref "U105") (pin "1") (pinfunction "GROUND_1") (pintype "power_in"))
      (node (ref "U106") (pin "1") (pinfunction "GROUND_1") (pintype "power_in"))
      (node (ref "U107") (pin "1") (pinfunction "GROUND_1") (pintype "power_in"))
      (node (ref "U108") (pin "1") (pinfunction "GROUND_1") (pintype "power_in"))
      (node (ref "U109") (pin "1") (pinfunction "GROUND_1") (pintype "power_in"))
      (node (ref "U110") (pin "1") (pinfunction "GROUND_1") (pintype "power_in"))
      (node (ref "U111") (pin "1") (pinfunction "GROUND_1") (pintype "power_in"))
      (node (ref "U112") (pin "1") (pinfunction "GROUND_1") (pintype "power_in"))
      (node (ref "U113") (pin "1") (pinfunction "GROUND_1") (pintype "power_in"))
      (node (ref "U114") (pin "1") (pinfunction "GROUND_1") (pintype "power_in"))
      (node (ref "U115") (pin "1") (pinfunction "GROUND_1") (pintype "power_in"))
      (node (ref "U2") (pin "2") (pinfunction "GND_2_2") (pintype "passive"))
      (node (ref "U2") (pin "25") (pinfunction "GND_25") (pintype "passive"))
      (node (ref "U20") (pin "8") (pinfunction "GND_8") (pintype "bidirectional"))
      (node (ref "U21") (pin "8") (pinfunction "GND_8") (pintype "bidirectional"))
      (node (ref "U22") (pin "8") (pinfunction "GND_8") (pintype "bidirectional"))
      (node (ref "U23") (pin "8") (pinfunction "GND_8") (pintype "bidirectional"))
      (node (ref "U5") (pin "2") (pinfunction "GND_2") (pintype "bidirectional"))
      (node (ref "U6") (pin "2") (pinfunction "GND_2") (pintype "power_in"))
      (node (ref "X1") (pin "A1/B12") (pinfunction "GND_2_A1/B12") (pintype "passive"))
      (node (ref "X1") (pin "B1/A12") (pinfunction "GND_B1/A12") (pintype "passive"))
      (node (ref "X2") (pin "P$3") (pinfunction "GND_P$3") (pintype "bidirectional"))
      (node (ref "X2") (pin "P$5") (pinfunction "GND2_P$5") (pintype "bidirectional"))
      (node (ref "X2") (pin "P$9") (pinfunction "GDTCT_P$9") (pintype "bidirectional"))
      (node (ref "X3") (pin "1") (pinfunction "1_1") (pintype "passive"))
      (node (ref "X4") (pin "1") (pinfunction "1_1") (pintype "passive"))
      (node (ref "X5") (pin "1") (pinfunction "1_1") (pintype "passive"))
    )
    (net (code "61") (name "HI_OUT") (class "Default")
      (node (ref "U21") (pin "9") (pinfunction "QH'_9") (pintype "bidirectional"))
      (node (ref "U22") (pin "14") (pinfunction "SER_14") (pintype "bidirectional"))
    )
    (net (code "62") (name "IN0") (class "Default")
      (node (ref "K0") (pin "4") (pinfunction "SIG_IN_4") (pintype "bidirectional"))
      (node (ref "K1") (pin "4") (pinfunction "SIG_IN_4") (pintype "bidirectional"))
      (node (ref "K2") (pin "4") (pinfunction "SIG_IN_4") (pintype "bidirectional"))
      (node (ref "K3") (pin "4") (pinfunction "SIG_IN_4") (pintype "bidirectional"))
      (node (ref "K4") (pin "4") (pinfunction "SIG_IN_4") (pintype "bidirectional"))
      (node (ref "K5") (pin "4") (pinfunction "SIG_IN_4") (pintype "bidirectional"))
      (node (ref "K6") (pin "4") (pinfunction "SIG_IN_4") (pintype "bidirectional"))
      (node (ref "K7") (pin "4") (pinfunction "SIG_IN_4") (pintype "bidirectional"))
      (node (ref "X101") (pin "2") (pinfunction "2_2") (pintype "bidirectional"))
    )
    (net (code "63") (name "IN1") (class "Default")
      (node (ref "K10") (pin "4") (pinfunction "SIG_IN_4") (pintype "bidirectional"))
      (node (ref "K11") (pin "4") (pinfunction "SIG_IN_4") (pintype "bidirectional"))
      (node (ref "K12") (pin "4") (pinfunction "SIG_IN_4") (pintype "bidirectional"))
      (node (ref "K13") (pin "4") (pinfunction "SIG_IN_4") (pintype "bidirectional"))
      (node (ref "K14") (pin "4") (pinfunction "SIG_IN_4") (pintype "bidirectional"))
      (node (ref "K15") (pin "4") (pinfunction "SIG_IN_4") (pintype "bidirectional"))
      (node (ref "K8") (pin "4") (pinfunction "SIG_IN_4") (pintype "bidirectional"))
      (node (ref "K9") (pin "4") (pinfunction "SIG_IN_4") (pintype "bidirectional"))
      (node (ref "X102") (pin "2") (pinfunction "2_2") (pintype "bidirectional"))
    )
    (net (code "64") (name "IN2") (class "Default")
      (node (ref "K16") (pin "4") (pinfunction "SIG_IN_4") (pintype "bidirectional"))
      (node (ref "K17") (pin "4") (pinfunction "SIG_IN_4") (pintype "bidirectional"))
      (node (ref "K18") (pin "4") (pinfunction "SIG_IN_4") (pintype "bidirectional"))
      (node (ref "K19") (pin "4") (pinfunction "SIG_IN_4") (pintype "bidirectional"))
      (node (ref "K20") (pin "4") (pinfunction "SIG_IN_4") (pintype "bidirectional"))
      (node (ref "K21") (pin "4") (pinfunction "SIG_IN_4") (pintype "bidirectional"))
      (node (ref "K22") (pin "4") (pinfunction "SIG_IN_4") (pintype "bidirectional"))
      (node (ref "K23") (pin "4") (pinfunction "SIG_IN_4") (pintype "bidirectional"))
      (node (ref "X103") (pin "2") (pinfunction "2_2") (pintype "bidirectional"))
    )
    (net (code "65") (name "IN3") (class "Default")
      (node (ref "K24") (pin "4") (pinfunction "SIG_IN_4") (pintype "bidirectional"))
      (node (ref "K25") (pin "4") (pinfunction "SIG_IN_4") (pintype "bidirectional"))
      (node (ref "K26") (pin "4") (pinfunction "SIG_IN_4") (pintype "bidirectional"))
      (node (ref "K27") (pin "4") (pinfunction "SIG_IN_4") (pintype "bidirectional"))
      (node (ref "K28") (pin "4") (pinfunction "SIG_IN_4") (pintype "bidirectional"))
      (node (ref "K29") (pin "4") (pinfunction "SIG_IN_4") (pintype "bidirectional"))
      (node (ref "K30") (pin "4") (pinfunction "SIG_IN_4") (pintype "bidirectional"))
      (node (ref "K31") (pin "4") (pinfunction "SIG_IN_4") (pintype "bidirectional"))
      (node (ref "X104") (pin "2") (pinfunction "2_2") (pintype "bidirectional"))
    )
    (net (code "66") (name "IN4") (class "Default")
      (node (ref "K32") (pin "4") (pinfunction "SIG_IN_4") (pintype "bidirectional"))
      (node (ref "K33") (pin "4") (pinfunction "SIG_IN_4") (pintype "bidirectional"))
      (node (ref "K34") (pin "4") (pinfunction "SIG_IN_4") (pintype "bidirectional"))
      (node (ref "K35") (pin "4") (pinfunction "SIG_IN_4") (pintype "bidirectional"))
      (node (ref "K36") (pin "4") (pinfunction "SIG_IN_4") (pintype "bidirectional"))
      (node (ref "K37") (pin "4") (pinfunction "SIG_IN_4") (pintype "bidirectional"))
      (node (ref "K38") (pin "4") (pinfunction "SIG_IN_4") (pintype "bidirectional"))
      (node (ref "K39") (pin "4") (pinfunction "SIG_IN_4") (pintype "bidirectional"))
      (node (ref "X105") (pin "2") (pinfunction "2_2") (pintype "bidirectional"))
    )
    (net (code "67") (name "IN5") (class "Default")
      (node (ref "K40") (pin "4") (pinfunction "SIG_IN_4") (pintype "bidirectional"))
      (node (ref "K41") (pin "4") (pinfunction "SIG_IN_4") (pintype "bidirectional"))
      (node (ref "K42") (pin "4") (pinfunction "SIG_IN_4") (pintype "bidirectional"))
      (node (ref "K43") (pin "4") (pinfunction "SIG_IN_4") (pintype "bidirectional"))
      (node (ref "K44") (pin "4") (pinfunction "SIG_IN_4") (pintype "bidirectional"))
      (node (ref "K45") (pin "4") (pinfunction "SIG_IN_4") (pintype "bidirectional"))
      (node (ref "K46") (pin "4") (pinfunction "SIG_IN_4") (pintype "bidirectional"))
      (node (ref "K47") (pin "4") (pinfunction "SIG_IN_4") (pintype "bidirectional"))
      (node (ref "X106") (pin "2") (pinfunction "2_2") (pintype "bidirectional"))
    )
    (net (code "68") (name "IN6") (class "Default")
      (node (ref "K48") (pin "4") (pinfunction "SIG_IN_4") (pintype "bidirectional"))
      (node (ref "K49") (pin "4") (pinfunction "SIG_IN_4") (pintype "bidirectional"))
      (node (ref "K50") (pin "4") (pinfunction "SIG_IN_4") (pintype "bidirectional"))
      (node (ref "K51") (pin "4") (pinfunction "SIG_IN_4") (pintype "bidirectional"))
      (node (ref "K52") (pin "4") (pinfunction "SIG_IN_4") (pintype "bidirectional"))
      (node (ref "K53") (pin "4") (pinfunction "SIG_IN_4") (pintype "bidirectional"))
      (node (ref "K54") (pin "4") (pinfunction "SIG_IN_4") (pintype "bidirectional"))
      (node (ref "K55") (pin "4") (pinfunction "SIG_IN_4") (pintype "bidirectional"))
      (node (ref "X107") (pin "2") (pinfunction "2_2") (pintype "bidirectional"))
    )
    (net (code "69") (name "IN7") (class "Default")
      (node (ref "K56") (pin "4") (pinfunction "SIG_IN_4") (pintype "bidirectional"))
      (node (ref "K57") (pin "4") (pinfunction "SIG_IN_4") (pintype "bidirectional"))
      (node (ref "K58") (pin "4") (pinfunction "SIG_IN_4") (pintype "bidirectional"))
      (node (ref "K59") (pin "4") (pinfunction "SIG_IN_4") (pintype "bidirectional"))
      (node (ref "K60") (pin "4") (pinfunction "SIG_IN_4") (pintype "bidirectional"))
      (node (ref "K61") (pin "4") (pinfunction "SIG_IN_4") (pintype "bidirectional"))
      (node (ref "K62") (pin "4") (pinfunction "SIG_IN_4") (pintype "bidirectional"))
      (node (ref "K63") (pin "4") (pinfunction "SIG_IN_4") (pintype "bidirectional"))
      (node (ref "X108") (pin "2") (pinfunction "2_2") (pintype "bidirectional"))
    )
    (net (code "70") (name "IN8") (class "Default")
      (node (ref "K64") (pin "4") (pinfunction "SIG_IN_4") (pintype "bidirectional"))
      (node (ref "K65") (pin "4") (pinfunction "SIG_IN_4") (pintype "bidirectional"))
      (node (ref "K66") (pin "4") (pinfunction "SIG_IN_4") (pintype "bidirectional"))
      (node (ref "K67") (pin "4") (pinfunction "SIG_IN_4") (pintype "bidirectional"))
      (node (ref "K68") (pin "4") (pinfunction "SIG_IN_4") (pintype "bidirectional"))
      (node (ref "K69") (pin "4") (pinfunction "SIG_IN_4") (pintype "bidirectional"))
      (node (ref "K70") (pin "4") (pinfunction "SIG_IN_4") (pintype "bidirectional"))
      (node (ref "K71") (pin "4") (pinfunction "SIG_IN_4") (pintype "bidirectional"))
      (node (ref "X108") (pin "4") (pinfunction "4_4") (pintype "bidirectional"))
    )
    (net (code "71") (name "IN9") (class "Default")
      (node (ref "K72") (pin "4") (pinfunction "SIG_IN_4") (pintype "bidirectional"))
      (node (ref "K73") (pin "4") (pinfunction "SIG_IN_4") (pintype "bidirectional"))
      (node (ref "K74") (pin "4") (pinfunction "SIG_IN_4") (pintype "bidirectional"))
      (node (ref "K75") (pin "4") (pinfunction "SIG_IN_4") (pintype "bidirectional"))
      (node (ref "K76") (pin "4") (pinfunction "SIG_IN_4") (pintype "bidirectional"))
      (node (ref "K77") (pin "4") (pinfunction "SIG_IN_4") (pintype "bidirectional"))
      (node (ref "K78") (pin "4") (pinfunction "SIG_IN_4") (pintype "bidirectional"))
      (node (ref "K79") (pin "4") (pinfunction "SIG_IN_4") (pintype "bidirectional"))
      (node (ref "X107") (pin "4") (pinfunction "4_4") (pintype "bidirectional"))
    )
    (net (code "72") (name "IN10") (class "Default")
      (node (ref "K80") (pin "4") (pinfunction "SIG_IN_4") (pintype "bidirectional"))
      (node (ref "K81") (pin "4") (pinfunction "SIG_IN_4") (pintype "bidirectional"))
      (node (ref "K82") (pin "4") (pinfunction "SIG_IN_4") (pintype "bidirectional"))
      (node (ref "K83") (pin "4") (pinfunction "SIG_IN_4") (pintype "bidirectional"))
      (node (ref "K84") (pin "4") (pinfunction "SIG_IN_4") (pintype "bidirectional"))
      (node (ref "K85") (pin "4") (pinfunction "SIG_IN_4") (pintype "bidirectional"))
      (node (ref "K86") (pin "4") (pinfunction "SIG_IN_4") (pintype "bidirectional"))
      (node (ref "K87") (pin "4") (pinfunction "SIG_IN_4") (pintype "bidirectional"))
      (node (ref "X106") (pin "4") (pinfunction "4_4") (pintype "bidirectional"))
    )
    (net (code "73") (name "IN11") (class "Default")
      (node (ref "K88") (pin "4") (pinfunction "SIG_IN_4") (pintype "bidirectional"))
      (node (ref "K89") (pin "4") (pinfunction "SIG_IN_4") (pintype "bidirectional"))
      (node (ref "K90") (pin "4") (pinfunction "SIG_IN_4") (pintype "bidirectional"))
      (node (ref "K91") (pin "4") (pinfunction "SIG_IN_4") (pintype "bidirectional"))
      (node (ref "K92") (pin "4") (pinfunction "SIG_IN_4") (pintype "bidirectional"))
      (node (ref "K93") (pin "4") (pinfunction "SIG_IN_4") (pintype "bidirectional"))
      (node (ref "K94") (pin "4") (pinfunction "SIG_IN_4") (pintype "bidirectional"))
      (node (ref "K95") (pin "4") (pinfunction "SIG_IN_4") (pintype "bidirectional"))
      (node (ref "X105") (pin "4") (pinfunction "4_4") (pintype "bidirectional"))
    )
    (net (code "74") (name "IN12") (class "Default")
      (node (ref "K100") (pin "4") (pinfunction "SIG_IN_4") (pintype "bidirectional"))
      (node (ref "K101") (pin "4") (pinfunction "SIG_IN_4") (pintype "bidirectional"))
      (node (ref "K102") (pin "4") (pinfunction "SIG_IN_4") (pintype "bidirectional"))
      (node (ref "K103") (pin "4") (pinfunction "SIG_IN_4") (pintype "bidirectional"))
      (node (ref "K96") (pin "4") (pinfunction "SIG_IN_4") (pintype "bidirectional"))
      (node (ref "K97") (pin "4") (pinfunction "SIG_IN_4") (pintype "bidirectional"))
      (node (ref "K98") (pin "4") (pinfunction "SIG_IN_4") (pintype "bidirectional"))
      (node (ref "K99") (pin "4") (pinfunction "SIG_IN_4") (pintype "bidirectional"))
      (node (ref "X104") (pin "4") (pinfunction "4_4") (pintype "bidirectional"))
    )
    (net (code "75") (name "IN13") (class "Default")
      (node (ref "K104") (pin "4") (pinfunction "SIG_IN_4") (pintype "bidirectional"))
      (node (ref "K105") (pin "4") (pinfunction "SIG_IN_4") (pintype "bidirectional"))
      (node (ref "K106") (pin "4") (pinfunction "SIG_IN_4") (pintype "bidirectional"))
      (node (ref "K107") (pin "4") (pinfunction "SIG_IN_4") (pintype "bidirectional"))
      (node (ref "K108") (pin "4") (pinfunction "SIG_IN_4") (pintype "bidirectional"))
      (node (ref "K109") (pin "4") (pinfunction "SIG_IN_4") (pintype "bidirectional"))
      (node (ref "K110") (pin "4") (pinfunction "SIG_IN_4") (pintype "bidirectional"))
      (node (ref "K111") (pin "4") (pinfunction "SIG_IN_4") (pintype "bidirectional"))
      (node (ref "X103") (pin "4") (pinfunction "4_4") (pintype "bidirectional"))
    )
    (net (code "76") (name "IN14") (class "Default")
      (node (ref "K112") (pin "4") (pinfunction "SIG_IN_4") (pintype "bidirectional"))
      (node (ref "K113") (pin "4") (pinfunction "SIG_IN_4") (pintype "bidirectional"))
      (node (ref "K114") (pin "4") (pinfunction "SIG_IN_4") (pintype "bidirectional"))
      (node (ref "K115") (pin "4") (pinfunction "SIG_IN_4") (pintype "bidirectional"))
      (node (ref "K116") (pin "4") (pinfunction "SIG_IN_4") (pintype "bidirectional"))
      (node (ref "K117") (pin "4") (pinfunction "SIG_IN_4") (pintype "bidirectional"))
      (node (ref "K118") (pin "4") (pinfunction "SIG_IN_4") (pintype "bidirectional"))
      (node (ref "K119") (pin "4") (pinfunction "SIG_IN_4") (pintype "bidirectional"))
      (node (ref "X102") (pin "4") (pinfunction "4_4") (pintype "bidirectional"))
    )
    (net (code "77") (name "IN15") (class "Default")
      (node (ref "K120") (pin "4") (pinfunction "SIG_IN_4") (pintype "bidirectional"))
      (node (ref "K121") (pin "4") (pinfunction "SIG_IN_4") (pintype "bidirectional"))
      (node (ref "K122") (pin "4") (pinfunction "SIG_IN_4") (pintype "bidirectional"))
      (node (ref "K123") (pin "4") (pinfunction "SIG_IN_4") (pintype "bidirectional"))
      (node (ref "K124") (pin "4") (pinfunction "SIG_IN_4") (pintype "bidirectional"))
      (node (ref "K125") (pin "4") (pinfunction "SIG_IN_4") (pintype "bidirectional"))
      (node (ref "K126") (pin "4") (pinfunction "SIG_IN_4") (pintype "bidirectional"))
      (node (ref "K127") (pin "4") (pinfunction "SIG_IN_4") (pintype "bidirectional"))
      (node (ref "X101") (pin "4") (pinfunction "4_4") (pintype "bidirectional"))
    )
    (net (code "78") (name "LO1_OUT") (class "Default")
      (node (ref "U22") (pin "9") (pinfunction "QH'_9") (pintype "bidirectional"))
      (node (ref "U23") (pin "14") (pinfunction "SER_14") (pintype "bidirectional"))
    )
    (net (code "79") (name "MCU_RX_C1") (class "Default")
      (node (ref "U1") (pin "59") (pinfunction "PE4_59") (pintype "bidirectional"))
      (node (ref "X4") (pin "3") (pinfunction "3_3") (pintype "passive"))
    )
    (net (code "80") (name "MCU_RX_C2") (class "Default")
      (node (ref "U1") (pin "9") (pinfunction "PE0_9") (pintype "bidirectional"))
      (node (ref "X5") (pin "3") (pinfunction "3_3") (pintype "passive"))
    )
    (net (code "81") (name "MCU_RX_DEBUG") (class "Default")
      (node (ref "U$131") (pin "2") (pinfunction "RXD_2") (pintype "bidirectional"))
      (node (ref "U1") (pin "16") (pinfunction "PC4_16") (pintype "bidirectional"))
    )
    (net (code "82") (name "MCU_RX_PAR") (class "Default")
      (node (ref "S1") (pin "2") (pinfunction "2_2") (pintype "passive"))
      (node (ref "U1") (pin "17") (pinfunction "PA0_U0RX_17") (pintype "bidirectional"))
    )
    (net (code "83") (name "MCU_TX_C1") (class "Default")
      (node (ref "U1") (pin "60") (pinfunction "PE5_60") (pintype "bidirectional"))
      (node (ref "X4") (pin "2") (pinfunction "2_2") (pintype "passive"))
    )
    (net (code "84") (name "MCU_TX_C2") (class "Default")
      (node (ref "U1") (pin "8") (pinfunction "PE1_8") (pintype "bidirectional"))
      (node (ref "X5") (pin "2") (pinfunction "2_2") (pintype "passive"))
    )
    (net (code "85") (name "MCU_TX_DEBUG") (class "Default")
      (node (ref "U$131") (pin "3") (pinfunction "TXD_3") (pintype "bidirectional"))
      (node (ref "U1") (pin "15") (pinfunction "PC5_15") (pintype "bidirectional"))
    )
    (net (code "86") (name "MCU_TX_PAR") (class "Default")
      (node (ref "S1") (pin "5") (pinfunction "5_5") (pintype "passive"))
      (node (ref "U1") (pin "18") (pinfunction "PA1_U0TX_18") (pintype "bidirectional"))
    )
    (net (code "87") (name "Net-(C11-Pad1)") (class "Default")
      (node (ref "C11") (pin "1") (pinfunction "1_1") (pintype "passive"))
      (node (ref "R37") (pin "1") (pinfunction "1_1") (pintype "passive"))
    )
    (net (code "88") (name "Net-(C12-Pad1)") (class "Default")
      (node (ref "C12") (pin "1") (pinfunction "1_1") (pintype "passive"))
      (node (ref "R38") (pin "1") (pinfunction "1_1") (pintype "passive"))
    )
    (net (code "89") (name "Net-(R32-Pad2)") (class "Default")
      (node (ref "R32") (pin "2") (pinfunction "2_2") (pintype "passive"))
      (node (ref "S2") (pin "P$1") (pinfunction "P$1_P$1") (pintype "bidirectional"))
      (node (ref "S2") (pin "P$2") (pinfunction "P$2_P$2") (pintype "bidirectional"))
    )
    (net (code "90") (name "Net-(U2-RSTB)") (class "Default")
      (node (ref "R9") (pin "2") (pinfunction "2_2") (pintype "passive"))
      (node (ref "U2") (pin "9") (pinfunction "RSTB_9") (pintype "passive"))
    )
    (net (code "91") (name "Net-(U3-ADJ{slash}GND)") (class "Default")
      (node (ref "C8") (pin "1") (pinfunction "1_1") (pintype "passive"))
      (node (ref "R35") (pin "1") (pinfunction "1_1") (pintype "passive"))
      (node (ref "R36") (pin "2") (pinfunction "2_2") (pintype "passive"))
      (node (ref "U3") (pin "1") (pinfunction "ADJ/GND_1") (pintype "bidirectional"))
    )
    (net (code "92") (name "Net-(U4-ADJ{slash}GND)") (class "Default")
      (node (ref "C9") (pin "1") (pinfunction "1_1") (pintype "passive"))
      (node (ref "R33") (pin "1") (pinfunction "1_1") (pintype "passive"))
      (node (ref "R34") (pin "2") (pinfunction "2_2") (pintype "passive"))
      (node (ref "U4") (pin "1") (pinfunction "ADJ/GND_1") (pintype "bidirectional"))
    )
    (net (code "93") (name "Net-(U22-QA)") (class "Default")
      (node (ref "R30") (pin "1") (pinfunction "1_1") (pintype "passive"))
      (node (ref "U22") (pin "15") (pinfunction "QA_15") (pintype "bidirectional"))
    )
    (net (code "94") (name "Net-(U22-QB)") (class "Default")
      (node (ref "R15") (pin "2") (pinfunction "2_2") (pintype "passive"))
      (node (ref "U22") (pin "1") (pinfunction "QB_1") (pintype "bidirectional"))
    )
    (net (code "95") (name "Net-(U22-QC)") (class "Default")
      (node (ref "R16") (pin "2") (pinfunction "2_2") (pintype "passive"))
      (node (ref "U22") (pin "2") (pinfunction "QC_2") (pintype "bidirectional"))
    )
    (net (code "96") (name "Net-(U22-QD)") (class "Default")
      (node (ref "R17") (pin "2") (pinfunction "2_2") (pintype "passive"))
      (node (ref "U22") (pin "3") (pinfunction "QD_3") (pintype "bidirectional"))
    )
    (net (code "97") (name "Net-(U22-QE)") (class "Default")
      (node (ref "R18") (pin "2") (pinfunction "2_2") (pintype "passive"))
      (node (ref "U22") (pin "4") (pinfunction "QE_4") (pintype "bidirectional"))
    )
    (net (code "98") (name "Net-(U22-QF)") (class "Default")
      (node (ref "R19") (pin "2") (pinfunction "2_2") (pintype "passive"))
      (node (ref "U22") (pin "5") (pinfunction "QF_5") (pintype "bidirectional"))
    )
    (net (code "99") (name "Net-(U22-QG)") (class "Default")
      (node (ref "R20") (pin "2") (pinfunction "2_2") (pintype "passive"))
      (node (ref "U22") (pin "6") (pinfunction "QG_6") (pintype "bidirectional"))
    )
    (net (code "100") (name "Net-(U22-QH)") (class "Default")
      (node (ref "R21") (pin "2") (pinfunction "2_2") (pintype "passive"))
      (node (ref "U22") (pin "7") (pinfunction "QH_7") (pintype "bidirectional"))
    )
    (net (code "101") (name "Net-(U23-QA)") (class "Default")
      (node (ref "R29") (pin "1") (pinfunction "1_1") (pintype "passive"))
      (node (ref "U23") (pin "15") (pinfunction "QA_15") (pintype "bidirectional"))
    )
    (net (code "102") (name "Net-(U23-QB)") (class "Default")
      (node (ref "R22") (pin "2") (pinfunction "2_2") (pintype "passive"))
      (node (ref "U23") (pin "1") (pinfunction "QB_1") (pintype "bidirectional"))
    )
    (net (code "103") (name "Net-(U23-QC)") (class "Default")
      (node (ref "R23") (pin "2") (pinfunction "2_2") (pintype "passive"))
      (node (ref "U23") (pin "2") (pinfunction "QC_2") (pintype "bidirectional"))
    )
    (net (code "104") (name "Net-(U23-QD)") (class "Default")
      (node (ref "R24") (pin "2") (pinfunction "2_2") (pintype "passive"))
      (node (ref "U23") (pin "3") (pinfunction "QD_3") (pintype "bidirectional"))
    )
    (net (code "105") (name "Net-(U23-QE)") (class "Default")
      (node (ref "R25") (pin "2") (pinfunction "2_2") (pintype "passive"))
      (node (ref "U23") (pin "4") (pinfunction "QE_4") (pintype "bidirectional"))
    )
    (net (code "106") (name "Net-(U23-QF)") (class "Default")
      (node (ref "R26") (pin "2") (pinfunction "2_2") (pintype "passive"))
      (node (ref "U23") (pin "5") (pinfunction "QF_5") (pintype "bidirectional"))
    )
    (net (code "107") (name "Net-(U23-QG)") (class "Default")
      (node (ref "R27") (pin "2") (pinfunction "2_2") (pintype "passive"))
      (node (ref "U23") (pin "6") (pinfunction "QG_6") (pintype "bidirectional"))
    )
    (net (code "108") (name "Net-(U23-QH)") (class "Default")
      (node (ref "R28") (pin "2") (pinfunction "2_2") (pintype "passive"))
      (node (ref "U23") (pin "7") (pinfunction "QH_7") (pintype "bidirectional"))
    )
    (net (code "109") (name "Net-(X1-CC1)") (class "Default")
      (node (ref "R10") (pin "2") (pinfunction "2_2") (pintype "passive"))
      (node (ref "X1") (pin "A5") (pinfunction "CC1_A5") (pintype "bidirectional"))
    )
    (net (code "110") (name "Net-(X1-CC2)") (class "Default")
      (node (ref "R11") (pin "2") (pinfunction "2_2") (pintype "passive"))
      (node (ref "X1") (pin "B5") (pinfunction "CC2_B5") (pintype "bidirectional"))
    )
    (net (code "111") (name "OSC") (class "Default")
      (node (ref "U1") (pin "34") (pinfunction "XOSC0_34") (pintype "input"))
      (node (ref "U5") (pin "3") (pinfunction "OSC_3") (pintype "bidirectional"))
    )
    (net (code "112") (name "OUT0") (class "Default")
      (node (ref "K0") (pin "2") (pinfunction "SIG_OUT_2") (pintype "bidirectional"))
      (node (ref "K104") (pin "2") (pinfunction "SIG_OUT_2") (pintype "bidirectional"))
      (node (ref "K112") (pin "2") (pinfunction "SIG_OUT_2") (pintype "bidirectional"))
      (node (ref "K120") (pin "2") (pinfunction "SIG_OUT_2") (pintype "bidirectional"))
      (node (ref "K16") (pin "2") (pinfunction "SIG_OUT_2") (pintype "bidirectional"))
      (node (ref "K24") (pin "2") (pinfunction "SIG_OUT_2") (pintype "bidirectional"))
      (node (ref "K32") (pin "2") (pinfunction "SIG_OUT_2") (pintype "bidirectional"))
      (node (ref "K40") (pin "2") (pinfunction "SIG_OUT_2") (pintype "bidirectional"))
      (node (ref "K48") (pin "2") (pinfunction "SIG_OUT_2") (pintype "bidirectional"))
      (node (ref "K56") (pin "2") (pinfunction "SIG_OUT_2") (pintype "bidirectional"))
      (node (ref "K64") (pin "2") (pinfunction "SIG_OUT_2") (pintype "bidirectional"))
      (node (ref "K72") (pin "2") (pinfunction "SIG_OUT_2") (pintype "bidirectional"))
      (node (ref "K8") (pin "2") (pinfunction "SIG_OUT_2") (pintype "bidirectional"))
      (node (ref "K80") (pin "2") (pinfunction "SIG_OUT_2") (pintype "bidirectional"))
      (node (ref "K88") (pin "2") (pinfunction "SIG_OUT_2") (pintype "bidirectional"))
      (node (ref "K96") (pin "2") (pinfunction "SIG_OUT_2") (pintype "bidirectional"))
      (node (ref "X111") (pin "2") (pinfunction "2_2") (pintype "bidirectional"))
    )
    (net (code "113") (name "OUT1") (class "Default")
      (node (ref "K1") (pin "2") (pinfunction "SIG_OUT_2") (pintype "bidirectional"))
      (node (ref "K105") (pin "2") (pinfunction "SIG_OUT_2") (pintype "bidirectional"))
      (node (ref "K113") (pin "2") (pinfunction "SIG_OUT_2") (pintype "bidirectional"))
      (node (ref "K121") (pin "2") (pinfunction "SIG_OUT_2") (pintype "bidirectional"))
      (node (ref "K17") (pin "2") (pinfunction "SIG_OUT_2") (pintype "bidirectional"))
      (node (ref "K25") (pin "2") (pinfunction "SIG_OUT_2") (pintype "bidirectional"))
      (node (ref "K33") (pin "2") (pinfunction "SIG_OUT_2") (pintype "bidirectional"))
      (node (ref "K41") (pin "2") (pinfunction "SIG_OUT_2") (pintype "bidirectional"))
      (node (ref "K49") (pin "2") (pinfunction "SIG_OUT_2") (pintype "bidirectional"))
      (node (ref "K57") (pin "2") (pinfunction "SIG_OUT_2") (pintype "bidirectional"))
      (node (ref "K65") (pin "2") (pinfunction "SIG_OUT_2") (pintype "bidirectional"))
      (node (ref "K73") (pin "2") (pinfunction "SIG_OUT_2") (pintype "bidirectional"))
      (node (ref "K81") (pin "2") (pinfunction "SIG_OUT_2") (pintype "bidirectional"))
      (node (ref "K89") (pin "2") (pinfunction "SIG_OUT_2") (pintype "bidirectional"))
      (node (ref "K9") (pin "2") (pinfunction "SIG_OUT_2") (pintype "bidirectional"))
      (node (ref "K97") (pin "2") (pinfunction "SIG_OUT_2") (pintype "bidirectional"))
      (node (ref "X112") (pin "2") (pinfunction "2_2") (pintype "bidirectional"))
    )
    (net (code "114") (name "OUT2") (class "Default")
      (node (ref "K10") (pin "2") (pinfunction "SIG_OUT_2") (pintype "bidirectional"))
      (node (ref "K106") (pin "2") (pinfunction "SIG_OUT_2") (pintype "bidirectional"))
      (node (ref "K114") (pin "2") (pinfunction "SIG_OUT_2") (pintype "bidirectional"))
      (node (ref "K122") (pin "2") (pinfunction "SIG_OUT_2") (pintype "bidirectional"))
      (node (ref "K18") (pin "2") (pinfunction "SIG_OUT_2") (pintype "bidirectional"))
      (node (ref "K2") (pin "2") (pinfunction "SIG_OUT_2") (pintype "bidirectional"))
      (node (ref "K26") (pin "2") (pinfunction "SIG_OUT_2") (pintype "bidirectional"))
      (node (ref "K34") (pin "2") (pinfunction "SIG_OUT_2") (pintype "bidirectional"))
      (node (ref "K42") (pin "2") (pinfunction "SIG_OUT_2") (pintype "bidirectional"))
      (node (ref "K50") (pin "2") (pinfunction "SIG_OUT_2") (pintype "bidirectional"))
      (node (ref "K58") (pin "2") (pinfunction "SIG_OUT_2") (pintype "bidirectional"))
      (node (ref "K66") (pin "2") (pinfunction "SIG_OUT_2") (pintype "bidirectional"))
      (node (ref "K74") (pin "2") (pinfunction "SIG_OUT_2") (pintype "bidirectional"))
      (node (ref "K82") (pin "2") (pinfunction "SIG_OUT_2") (pintype "bidirectional"))
      (node (ref "K90") (pin "2") (pinfunction "SIG_OUT_2") (pintype "bidirectional"))
      (node (ref "K98") (pin "2") (pinfunction "SIG_OUT_2") (pintype "bidirectional"))
      (node (ref "X113") (pin "2") (pinfunction "2_2") (pintype "bidirectional"))
    )
    (net (code "115") (name "OUT3") (class "Default")
      (node (ref "K107") (pin "2") (pinfunction "SIG_OUT_2") (pintype "bidirectional"))
      (node (ref "K11") (pin "2") (pinfunction "SIG_OUT_2") (pintype "bidirectional"))
      (node (ref "K115") (pin "2") (pinfunction "SIG_OUT_2") (pintype "bidirectional"))
      (node (ref "K123") (pin "2") (pinfunction "SIG_OUT_2") (pintype "bidirectional"))
      (node (ref "K19") (pin "2") (pinfunction "SIG_OUT_2") (pintype "bidirectional"))
      (node (ref "K27") (pin "2") (pinfunction "SIG_OUT_2") (pintype "bidirectional"))
      (node (ref "K3") (pin "2") (pinfunction "SIG_OUT_2") (pintype "bidirectional"))
      (node (ref "K35") (pin "2") (pinfunction "SIG_OUT_2") (pintype "bidirectional"))
      (node (ref "K43") (pin "2") (pinfunction "SIG_OUT_2") (pintype "bidirectional"))
      (node (ref "K51") (pin "2") (pinfunction "SIG_OUT_2") (pintype "bidirectional"))
      (node (ref "K59") (pin "2") (pinfunction "SIG_OUT_2") (pintype "bidirectional"))
      (node (ref "K67") (pin "2") (pinfunction "SIG_OUT_2") (pintype "bidirectional"))
      (node (ref "K75") (pin "2") (pinfunction "SIG_OUT_2") (pintype "bidirectional"))
      (node (ref "K83") (pin "2") (pinfunction "SIG_OUT_2") (pintype "bidirectional"))
      (node (ref "K91") (pin "2") (pinfunction "SIG_OUT_2") (pintype "bidirectional"))
      (node (ref "K99") (pin "2") (pinfunction "SIG_OUT_2") (pintype "bidirectional"))
      (node (ref "X114") (pin "2") (pinfunction "2_2") (pintype "bidirectional"))
    )
    (net (code "116") (name "OUT4") (class "Default")
      (node (ref "K100") (pin "2") (pinfunction "SIG_OUT_2") (pintype "bidirectional"))
      (node (ref "K108") (pin "2") (pinfunction "SIG_OUT_2") (pintype "bidirectional"))
      (node (ref "K116") (pin "2") (pinfunction "SIG_OUT_2") (pintype "bidirectional"))
      (node (ref "K12") (pin "2") (pinfunction "SIG_OUT_2") (pintype "bidirectional"))
      (node (ref "K124") (pin "2") (pinfunction "SIG_OUT_2") (pintype "bidirectional"))
      (node (ref "K20") (pin "2") (pinfunction "SIG_OUT_2") (pintype "bidirectional"))
      (node (ref "K28") (pin "2") (pinfunction "SIG_OUT_2") (pintype "bidirectional"))
      (node (ref "K36") (pin "2") (pinfunction "SIG_OUT_2") (pintype "bidirectional"))
      (node (ref "K4") (pin "2") (pinfunction "SIG_OUT_2") (pintype "bidirectional"))
      (node (ref "K44") (pin "2") (pinfunction "SIG_OUT_2") (pintype "bidirectional"))
      (node (ref "K52") (pin "2") (pinfunction "SIG_OUT_2") (pintype "bidirectional"))
      (node (ref "K60") (pin "2") (pinfunction "SIG_OUT_2") (pintype "bidirectional"))
      (node (ref "K68") (pin "2") (pinfunction "SIG_OUT_2") (pintype "bidirectional"))
      (node (ref "K76") (pin "2") (pinfunction "SIG_OUT_2") (pintype "bidirectional"))
      (node (ref "K84") (pin "2") (pinfunction "SIG_OUT_2") (pintype "bidirectional"))
      (node (ref "K92") (pin "2") (pinfunction "SIG_OUT_2") (pintype "bidirectional"))
      (node (ref "X114") (pin "4") (pinfunction "4_4") (pintype "bidirectional"))
    )
    (net (code "117") (name "OUT5") (class "Default")
      (node (ref "K101") (pin "2") (pinfunction "SIG_OUT_2") (pintype "bidirectional"))
      (node (ref "K109") (pin "2") (pinfunction "SIG_OUT_2") (pintype "bidirectional"))
      (node (ref "K117") (pin "2") (pinfunction "SIG_OUT_2") (pintype "bidirectional"))
      (node (ref "K125") (pin "2") (pinfunction "SIG_OUT_2") (pintype "bidirectional"))
      (node (ref "K13") (pin "2") (pinfunction "SIG_OUT_2") (pintype "bidirectional"))
      (node (ref "K21") (pin "2") (pinfunction "SIG_OUT_2") (pintype "bidirectional"))
      (node (ref "K29") (pin "2") (pinfunction "SIG_OUT_2") (pintype "bidirectional"))
      (node (ref "K37") (pin "2") (pinfunction "SIG_OUT_2") (pintype "bidirectional"))
      (node (ref "K45") (pin "2") (pinfunction "SIG_OUT_2") (pintype "bidirectional"))
      (node (ref "K5") (pin "2") (pinfunction "SIG_OUT_2") (pintype "bidirectional"))
      (node (ref "K53") (pin "2") (pinfunction "SIG_OUT_2") (pintype "bidirectional"))
      (node (ref "K61") (pin "2") (pinfunction "SIG_OUT_2") (pintype "bidirectional"))
      (node (ref "K69") (pin "2") (pinfunction "SIG_OUT_2") (pintype "bidirectional"))
      (node (ref "K77") (pin "2") (pinfunction "SIG_OUT_2") (pintype "bidirectional"))
      (node (ref "K85") (pin "2") (pinfunction "SIG_OUT_2") (pintype "bidirectional"))
      (node (ref "K93") (pin "2") (pinfunction "SIG_OUT_2") (pintype "bidirectional"))
      (node (ref "X113") (pin "4") (pinfunction "4_4") (pintype "bidirectional"))
    )
    (net (code "118") (name "OUT6") (class "Default")
      (node (ref "K102") (pin "2") (pinfunction "SIG_OUT_2") (pintype "bidirectional"))
      (node (ref "K110") (pin "2") (pinfunction "SIG_OUT_2") (pintype "bidirectional"))
      (node (ref "K118") (pin "2") (pinfunction "SIG_OUT_2") (pintype "bidirectional"))
      (node (ref "K126") (pin "2") (pinfunction "SIG_OUT_2") (pintype "bidirectional"))
      (node (ref "K14") (pin "2") (pinfunction "SIG_OUT_2") (pintype "bidirectional"))
      (node (ref "K22") (pin "2") (pinfunction "SIG_OUT_2") (pintype "bidirectional"))
      (node (ref "K30") (pin "2") (pinfunction "SIG_OUT_2") (pintype "bidirectional"))
      (node (ref "K38") (pin "2") (pinfunction "SIG_OUT_2") (pintype "bidirectional"))
      (node (ref "K46") (pin "2") (pinfunction "SIG_OUT_2") (pintype "bidirectional"))
      (node (ref "K54") (pin "2") (pinfunction "SIG_OUT_2") (pintype "bidirectional"))
      (node (ref "K6") (pin "2") (pinfunction "SIG_OUT_2") (pintype "bidirectional"))
      (node (ref "K62") (pin "2") (pinfunction "SIG_OUT_2") (pintype "bidirectional"))
      (node (ref "K70") (pin "2") (pinfunction "SIG_OUT_2") (pintype "bidirectional"))
      (node (ref "K78") (pin "2") (pinfunction "SIG_OUT_2") (pintype "bidirectional"))
      (node (ref "K86") (pin "2") (pinfunction "SIG_OUT_2") (pintype "bidirectional"))
      (node (ref "K94") (pin "2") (pinfunction "SIG_OUT_2") (pintype "bidirectional"))
      (node (ref "X112") (pin "4") (pinfunction "4_4") (pintype "bidirectional"))
    )
    (net (code "119") (name "OUT7") (class "Default")
      (node (ref "K103") (pin "2") (pinfunction "SIG_OUT_2") (pintype "bidirectional"))
      (node (ref "K111") (pin "2") (pinfunction "SIG_OUT_2") (pintype "bidirectional"))
      (node (ref "K119") (pin "2") (pinfunction "SIG_OUT_2") (pintype "bidirectional"))
      (node (ref "K127") (pin "2") (pinfunction "SIG_OUT_2") (pintype "bidirectional"))
      (node (ref "K15") (pin "2") (pinfunction "SIG_OUT_2") (pintype "bidirectional"))
      (node (ref "K23") (pin "2") (pinfunction "SIG_OUT_2") (pintype "bidirectional"))
      (node (ref "K31") (pin "2") (pinfunction "SIG_OUT_2") (pintype "bidirectional"))
      (node (ref "K39") (pin "2") (pinfunction "SIG_OUT_2") (pintype "bidirectional"))
      (node (ref "K47") (pin "2") (pinfunction "SIG_OUT_2") (pintype "bidirectional"))
      (node (ref "K55") (pin "2") (pinfunction "SIG_OUT_2") (pintype "bidirectional"))
      (node (ref "K63") (pin "2") (pinfunction "SIG_OUT_2") (pintype "bidirectional"))
      (node (ref "K7") (pin "2") (pinfunction "SIG_OUT_2") (pintype "bidirectional"))
      (node (ref "K71") (pin "2") (pinfunction "SIG_OUT_2") (pintype "bidirectional"))
      (node (ref "K79") (pin "2") (pinfunction "SIG_OUT_2") (pintype "bidirectional"))
      (node (ref "K87") (pin "2") (pinfunction "SIG_OUT_2") (pintype "bidirectional"))
      (node (ref "K95") (pin "2") (pinfunction "SIG_OUT_2") (pintype "bidirectional"))
      (node (ref "X111") (pin "4") (pinfunction "4_4") (pintype "bidirectional"))
    )
    (net (code "120") (name "PAR_RX") (class "Default")
      (node (ref "S1") (pin "1") (pinfunction "1_1") (pintype "passive"))
      (node (ref "X3") (pin "2") (pinfunction "2_2") (pintype "passive"))
    )
    (net (code "121") (name "PAR_TX") (class "Default")
      (node (ref "S1") (pin "4") (pinfunction "4_4") (pintype "passive"))
      (node (ref "X3") (pin "3") (pinfunction "3_3") (pintype "passive"))
    )
    (net (code "122") (name "R0") (class "Default")
      (node (ref "K0") (pin "5") (pinfunction "COIL_HIGH_5") (pintype "bidirectional"))
      (node (ref "U100") (pin "5") (pinfunction "OUT1_5") (pintype "output"))
    )
    (net (code "123") (name "R1") (class "Default")
      (node (ref "K1") (pin "5") (pinfunction "COIL_HIGH_5") (pintype "bidirectional"))
      (node (ref "U100") (pin "6") (pinfunction "OUT2_6") (pintype "output"))
    )
    (net (code "124") (name "R2") (class "Default")
      (node (ref "K2") (pin "5") (pinfunction "COIL_HIGH_5") (pintype "bidirectional"))
      (node (ref "U100") (pin "7") (pinfunction "OUT3_7") (pintype "output"))
    )
    (net (code "125") (name "R3") (class "Default")
      (node (ref "K3") (pin "5") (pinfunction "COIL_HIGH_5") (pintype "bidirectional"))
      (node (ref "U100") (pin "8") (pinfunction "OUT4_8") (pintype "output"))
    )
    (net (code "126") (name "R4") (class "Default")
      (node (ref "K4") (pin "5") (pinfunction "COIL_HIGH_5") (pintype "bidirectional"))
      (node (ref "U100") (pin "9") (pinfunction "OUT5_9") (pintype "output"))
    )
    (net (code "127") (name "R5") (class "Default")
      (node (ref "K5") (pin "5") (pinfunction "COIL_HIGH_5") (pintype "bidirectional"))
      (node (ref "U100") (pin "10") (pinfunction "OUT6_10") (pintype "output"))
    )
    (net (code "128") (name "R6") (class "Default")
      (node (ref "K6") (pin "5") (pinfunction "COIL_HIGH_5") (pintype "bidirectional"))
      (node (ref "U100") (pin "11") (pinfunction "OUT7_11") (pintype "output"))
    )
    (net (code "129") (name "R7") (class "Default")
      (node (ref "K7") (pin "5") (pinfunction "COIL_HIGH_5") (pintype "bidirectional"))
      (node (ref "U100") (pin "12") (pinfunction "OUT8_12") (pintype "output"))
    )
    (net (code "130") (name "R8") (class "Default")
      (node (ref "K8") (pin "5") (pinfunction "COIL_HIGH_5") (pintype "bidirectional"))
      (node (ref "U101") (pin "5") (pinfunction "OUT1_5") (pintype "output"))
    )
    (net (code "131") (name "R9") (class "Default")
      (node (ref "K9") (pin "5") (pinfunction "COIL_HIGH_5") (pintype "bidirectional"))
      (node (ref "U101") (pin "6") (pinfunction "OUT2_6") (pintype "output"))
    )
    (net (code "132") (name "R10") (class "Default")
      (node (ref "K10") (pin "5") (pinfunction "COIL_HIGH_5") (pintype "bidirectional"))
      (node (ref "U101") (pin "7") (pinfunction "OUT3_7") (pintype "output"))
    )
    (net (code "133") (name "R11") (class "Default")
      (node (ref "K11") (pin "5") (pinfunction "COIL_HIGH_5") (pintype "bidirectional"))
      (node (ref "U101") (pin "8") (pinfunction "OUT4_8") (pintype "output"))
    )
    (net (code "134") (name "R12") (class "Default")
      (node (ref "K12") (pin "5") (pinfunction "COIL_HIGH_5") (pintype "bidirectional"))
      (node (ref "U101") (pin "9") (pinfunction "OUT5_9") (pintype "output"))
    )
    (net (code "135") (name "R13") (class "Default")
      (node (ref "K13") (pin "5") (pinfunction "COIL_HIGH_5") (pintype "bidirectional"))
      (node (ref "U101") (pin "10") (pinfunction "OUT6_10") (pintype "output"))
    )
    (net (code "136") (name "R14") (class "Default")
      (node (ref "K14") (pin "5") (pinfunction "COIL_HIGH_5") (pintype "bidirectional"))
      (node (ref "U101") (pin "11") (pinfunction "OUT7_11") (pintype "output"))
    )
    (net (code "137") (name "R15") (class "Default")
      (node (ref "K15") (pin "5") (pinfunction "COIL_HIGH_5") (pintype "bidirectional"))
      (node (ref "U101") (pin "12") (pinfunction "OUT8_12") (pintype "output"))
    )
    (net (code "138") (name "R16") (class "Default")
      (node (ref "K16") (pin "5") (pinfunction "COIL_HIGH_5") (pintype "bidirectional"))
      (node (ref "U102") (pin "5") (pinfunction "OUT1_5") (pintype "output"))
    )
    (net (code "139") (name "R17") (class "Default")
      (node (ref "K17") (pin "5") (pinfunction "COIL_HIGH_5") (pintype "bidirectional"))
      (node (ref "U102") (pin "6") (pinfunction "OUT2_6") (pintype "output"))
    )
    (net (code "140") (name "R18") (class "Default")
      (node (ref "K18") (pin "5") (pinfunction "COIL_HIGH_5") (pintype "bidirectional"))
      (node (ref "U102") (pin "7") (pinfunction "OUT3_7") (pintype "output"))
    )
    (net (code "141") (name "R19") (class "Default")
      (node (ref "K19") (pin "5") (pinfunction "COIL_HIGH_5") (pintype "bidirectional"))
      (node (ref "U102") (pin "8") (pinfunction "OUT4_8") (pintype "output"))
    )
    (net (code "142") (name "R20") (class "Default")
      (node (ref "K20") (pin "5") (pinfunction "COIL_HIGH_5") (pintype "bidirectional"))
      (node (ref "U102") (pin "9") (pinfunction "OUT5_9") (pintype "output"))
    )
    (net (code "143") (name "R21") (class "Default")
      (node (ref "K21") (pin "5") (pinfunction "COIL_HIGH_5") (pintype "bidirectional"))
      (node (ref "U102") (pin "10") (pinfunction "OUT6_10") (pintype "output"))
    )
    (net (code "144") (name "R22") (class "Default")
      (node (ref "K22") (pin "5") (pinfunction "COIL_HIGH_5") (pintype "bidirectional"))
      (node (ref "U102") (pin "11") (pinfunction "OUT7_11") (pintype "output"))
    )
    (net (code "145") (name "R23") (class "Default")
      (node (ref "K23") (pin "5") (pinfunction "COIL_HIGH_5") (pintype "bidirectional"))
      (node (ref "U102") (pin "12") (pinfunction "OUT8_12") (pintype "output"))
    )
    (net (code "146") (name "R24") (class "Default")
      (node (ref "K24") (pin "5") (pinfunction "COIL_HIGH_5") (pintype "bidirectional"))
      (node (ref "U103") (pin "5") (pinfunction "OUT1_5") (pintype "output"))
    )
    (net (code "147") (name "R25") (class "Default")
      (node (ref "K25") (pin "5") (pinfunction "COIL_HIGH_5") (pintype "bidirectional"))
      (node (ref "U103") (pin "6") (pinfunction "OUT2_6") (pintype "output"))
    )
    (net (code "148") (name "R26") (class "Default")
      (node (ref "K26") (pin "5") (pinfunction "COIL_HIGH_5") (pintype "bidirectional"))
      (node (ref "U103") (pin "7") (pinfunction "OUT3_7") (pintype "output"))
    )
    (net (code "149") (name "R27") (class "Default")
      (node (ref "K27") (pin "5") (pinfunction "COIL_HIGH_5") (pintype "bidirectional"))
      (node (ref "U103") (pin "8") (pinfunction "OUT4_8") (pintype "output"))
    )
    (net (code "150") (name "R28") (class "Default")
      (node (ref "K28") (pin "5") (pinfunction "COIL_HIGH_5") (pintype "bidirectional"))
      (node (ref "U103") (pin "9") (pinfunction "OUT5_9") (pintype "output"))
    )
    (net (code "151") (name "R29") (class "Default")
      (node (ref "K29") (pin "5") (pinfunction "COIL_HIGH_5") (pintype "bidirectional"))
      (node (ref "U103") (pin "10") (pinfunction "OUT6_10") (pintype "output"))
    )
    (net (code "152") (name "R30") (class "Default")
      (node (ref "K30") (pin "5") (pinfunction "COIL_HIGH_5") (pintype "bidirectional"))
      (node (ref "U103") (pin "11") (pinfunction "OUT7_11") (pintype "output"))
    )
    (net (code "153") (name "R31") (class "Default")
      (node (ref "K31") (pin "5") (pinfunction "COIL_HIGH_5") (pintype "bidirectional"))
      (node (ref "U103") (pin "12") (pinfunction "OUT8_12") (pintype "output"))
    )
    (net (code "154") (name "R32") (class "Default")
      (node (ref "K32") (pin "5") (pinfunction "COIL_HIGH_5") (pintype "bidirectional"))
      (node (ref "U104") (pin "5") (pinfunction "OUT1_5") (pintype "output"))
    )
    (net (code "155") (name "R33") (class "Default")
      (node (ref "K33") (pin "5") (pinfunction "COIL_HIGH_5") (pintype "bidirectional"))
      (node (ref "U104") (pin "6") (pinfunction "OUT2_6") (pintype "output"))
    )
    (net (code "156") (name "R34") (class "Default")
      (node (ref "K34") (pin "5") (pinfunction "COIL_HIGH_5") (pintype "bidirectional"))
      (node (ref "U104") (pin "7") (pinfunction "OUT3_7") (pintype "output"))
    )
    (net (code "157") (name "R35") (class "Default")
      (node (ref "K35") (pin "5") (pinfunction "COIL_HIGH_5") (pintype "bidirectional"))
      (node (ref "U104") (pin "8") (pinfunction "OUT4_8") (pintype "output"))
    )
    (net (code "158") (name "R36") (class "Default")
      (node (ref "K36") (pin "5") (pinfunction "COIL_HIGH_5") (pintype "bidirectional"))
      (node (ref "U104") (pin "9") (pinfunction "OUT5_9") (pintype "output"))
    )
    (net (code "159") (name "R37") (class "Default")
      (node (ref "K37") (pin "5") (pinfunction "COIL_HIGH_5") (pintype "bidirectional"))
      (node (ref "U104") (pin "10") (pinfunction "OUT6_10") (pintype "output"))
    )
    (net (code "160") (name "R38") (class "Default")
      (node (ref "K38") (pin "5") (pinfunction "COIL_HIGH_5") (pintype "bidirectional"))
      (node (ref "U104") (pin "11") (pinfunction "OUT7_11") (pintype "output"))
    )
    (net (code "161") (name "R39") (class "Default")
      (node (ref "K39") (pin "5") (pinfunction "COIL_HIGH_5") (pintype "bidirectional"))
      (node (ref "U104") (pin "12") (pinfunction "OUT8_12") (pintype "output"))
    )
    (net (code "162") (name "R40") (class "Default")
      (node (ref "K40") (pin "5") (pinfunction "COIL_HIGH_5") (pintype "bidirectional"))
      (node (ref "U105") (pin "5") (pinfunction "OUT1_5") (pintype "output"))
    )
    (net (code "163") (name "R41") (class "Default")
      (node (ref "K41") (pin "5") (pinfunction "COIL_HIGH_5") (pintype "bidirectional"))
      (node (ref "U105") (pin "6") (pinfunction "OUT2_6") (pintype "output"))
    )
    (net (code "164") (name "R42") (class "Default")
      (node (ref "K42") (pin "5") (pinfunction "COIL_HIGH_5") (pintype "bidirectional"))
      (node (ref "U105") (pin "7") (pinfunction "OUT3_7") (pintype "output"))
    )
    (net (code "165") (name "R43") (class "Default")
      (node (ref "K43") (pin "5") (pinfunction "COIL_HIGH_5") (pintype "bidirectional"))
      (node (ref "U105") (pin "8") (pinfunction "OUT4_8") (pintype "output"))
    )
    (net (code "166") (name "R44") (class "Default")
      (node (ref "K44") (pin "5") (pinfunction "COIL_HIGH_5") (pintype "bidirectional"))
      (node (ref "U105") (pin "9") (pinfunction "OUT5_9") (pintype "output"))
    )
    (net (code "167") (name "R45") (class "Default")
      (node (ref "K45") (pin "5") (pinfunction "COIL_HIGH_5") (pintype "bidirectional"))
      (node (ref "U105") (pin "10") (pinfunction "OUT6_10") (pintype "output"))
    )
    (net (code "168") (name "R46") (class "Default")
      (node (ref "K46") (pin "5") (pinfunction "COIL_HIGH_5") (pintype "bidirectional"))
      (node (ref "U105") (pin "11") (pinfunction "OUT7_11") (pintype "output"))
    )
    (net (code "169") (name "R47") (class "Default")
      (node (ref "K47") (pin "5") (pinfunction "COIL_HIGH_5") (pintype "bidirectional"))
      (node (ref "U105") (pin "12") (pinfunction "OUT8_12") (pintype "output"))
    )
    (net (code "170") (name "R48") (class "Default")
      (node (ref "K48") (pin "5") (pinfunction "COIL_HIGH_5") (pintype "bidirectional"))
      (node (ref "U106") (pin "5") (pinfunction "OUT1_5") (pintype "output"))
    )
    (net (code "171") (name "R49") (class "Default")
      (node (ref "K49") (pin "5") (pinfunction "COIL_HIGH_5") (pintype "bidirectional"))
      (node (ref "U106") (pin "6") (pinfunction "OUT2_6") (pintype "output"))
    )
    (net (code "172") (name "R50") (class "Default")
      (node (ref "K50") (pin "5") (pinfunction "COIL_HIGH_5") (pintype "bidirectional"))
      (node (ref "U106") (pin "7") (pinfunction "OUT3_7") (pintype "output"))
    )
    (net (code "173") (name "R51") (class "Default")
      (node (ref "K51") (pin "5") (pinfunction "COIL_HIGH_5") (pintype "bidirectional"))
      (node (ref "U106") (pin "8") (pinfunction "OUT4_8") (pintype "output"))
    )
    (net (code "174") (name "R52") (class "Default")
      (node (ref "K52") (pin "5") (pinfunction "COIL_HIGH_5") (pintype "bidirectional"))
      (node (ref "U106") (pin "9") (pinfunction "OUT5_9") (pintype "output"))
    )
    (net (code "175") (name "R53") (class "Default")
      (node (ref "K53") (pin "5") (pinfunction "COIL_HIGH_5") (pintype "bidirectional"))
      (node (ref "U106") (pin "10") (pinfunction "OUT6_10") (pintype "output"))
    )
    (net (code "176") (name "R54") (class "Default")
      (node (ref "K54") (pin "5") (pinfunction "COIL_HIGH_5") (pintype "bidirectional"))
      (node (ref "U106") (pin "11") (pinfunction "OUT7_11") (pintype "output"))
    )
    (net (code "177") (name "R55") (class "Default")
      (node (ref "K55") (pin "5") (pinfunction "COIL_HIGH_5") (pintype "bidirectional"))
      (node (ref "U106") (pin "12") (pinfunction "OUT8_12") (pintype "output"))
    )
    (net (code "178") (name "R56") (class "Default")
      (node (ref "K56") (pin "5") (pinfunction "COIL_HIGH_5") (pintype "bidirectional"))
      (node (ref "U107") (pin "5") (pinfunction "OUT1_5") (pintype "output"))
    )
    (net (code "179") (name "R57") (class "Default")
      (node (ref "K57") (pin "5") (pinfunction "COIL_HIGH_5") (pintype "bidirectional"))
      (node (ref "U107") (pin "6") (pinfunction "OUT2_6") (pintype "output"))
    )
    (net (code "180") (name "R58") (class "Default")
      (node (ref "K58") (pin "5") (pinfunction "COIL_HIGH_5") (pintype "bidirectional"))
      (node (ref "U107") (pin "7") (pinfunction "OUT3_7") (pintype "output"))
    )
    (net (code "181") (name "R59") (class "Default")
      (node (ref "K59") (pin "5") (pinfunction "COIL_HIGH_5") (pintype "bidirectional"))
      (node (ref "U107") (pin "8") (pinfunction "OUT4_8") (pintype "output"))
    )
    (net (code "182") (name "R60") (class "Default")
      (node (ref "K60") (pin "5") (pinfunction "COIL_HIGH_5") (pintype "bidirectional"))
      (node (ref "U107") (pin "9") (pinfunction "OUT5_9") (pintype "output"))
    )
    (net (code "183") (name "R61") (class "Default")
      (node (ref "K61") (pin "5") (pinfunction "COIL_HIGH_5") (pintype "bidirectional"))
      (node (ref "U107") (pin "10") (pinfunction "OUT6_10") (pintype "output"))
    )
    (net (code "184") (name "R62") (class "Default")
      (node (ref "K62") (pin "5") (pinfunction "COIL_HIGH_5") (pintype "bidirectional"))
      (node (ref "U107") (pin "11") (pinfunction "OUT7_11") (pintype "output"))
    )
    (net (code "185") (name "R63") (class "Default")
      (node (ref "K63") (pin "5") (pinfunction "COIL_HIGH_5") (pintype "bidirectional"))
      (node (ref "U107") (pin "12") (pinfunction "OUT8_12") (pintype "output"))
    )
    (net (code "186") (name "R64") (class "Default")
      (node (ref "K64") (pin "5") (pinfunction "COIL_HIGH_5") (pintype "bidirectional"))
      (node (ref "U108") (pin "5") (pinfunction "OUT1_5") (pintype "output"))
    )
    (net (code "187") (name "R65") (class "Default")
      (node (ref "K65") (pin "5") (pinfunction "COIL_HIGH_5") (pintype "bidirectional"))
      (node (ref "U108") (pin "6") (pinfunction "OUT2_6") (pintype "output"))
    )
    (net (code "188") (name "R66") (class "Default")
      (node (ref "K66") (pin "5") (pinfunction "COIL_HIGH_5") (pintype "bidirectional"))
      (node (ref "U108") (pin "7") (pinfunction "OUT3_7") (pintype "output"))
    )
    (net (code "189") (name "R67") (class "Default")
      (node (ref "K67") (pin "5") (pinfunction "COIL_HIGH_5") (pintype "bidirectional"))
      (node (ref "U108") (pin "8") (pinfunction "OUT4_8") (pintype "output"))
    )
    (net (code "190") (name "R68") (class "Default")
      (node (ref "K68") (pin "5") (pinfunction "COIL_HIGH_5") (pintype "bidirectional"))
      (node (ref "U108") (pin "9") (pinfunction "OUT5_9") (pintype "output"))
    )
    (net (code "191") (name "R69") (class "Default")
      (node (ref "K69") (pin "5") (pinfunction "COIL_HIGH_5") (pintype "bidirectional"))
      (node (ref "U108") (pin "10") (pinfunction "OUT6_10") (pintype "output"))
    )
    (net (code "192") (name "R70") (class "Default")
      (node (ref "K70") (pin "5") (pinfunction "COIL_HIGH_5") (pintype "bidirectional"))
      (node (ref "U108") (pin "11") (pinfunction "OUT7_11") (pintype "output"))
    )
    (net (code "193") (name "R71") (class "Default")
      (node (ref "K71") (pin "5") (pinfunction "COIL_HIGH_5") (pintype "bidirectional"))
      (node (ref "U108") (pin "12") (pinfunction "OUT8_12") (pintype "output"))
    )
    (net (code "194") (name "R72") (class "Default")
      (node (ref "K72") (pin "5") (pinfunction "COIL_HIGH_5") (pintype "bidirectional"))
      (node (ref "U109") (pin "5") (pinfunction "OUT1_5") (pintype "output"))
    )
    (net (code "195") (name "R73") (class "Default")
      (node (ref "K73") (pin "5") (pinfunction "COIL_HIGH_5") (pintype "bidirectional"))
      (node (ref "U109") (pin "6") (pinfunction "OUT2_6") (pintype "output"))
    )
    (net (code "196") (name "R74") (class "Default")
      (node (ref "K74") (pin "5") (pinfunction "COIL_HIGH_5") (pintype "bidirectional"))
      (node (ref "U109") (pin "7") (pinfunction "OUT3_7") (pintype "output"))
    )
    (net (code "197") (name "R75") (class "Default")
      (node (ref "K75") (pin "5") (pinfunction "COIL_HIGH_5") (pintype "bidirectional"))
      (node (ref "U109") (pin "8") (pinfunction "OUT4_8") (pintype "output"))
    )
    (net (code "198") (name "R76") (class "Default")
      (node (ref "K76") (pin "5") (pinfunction "COIL_HIGH_5") (pintype "bidirectional"))
      (node (ref "U109") (pin "9") (pinfunction "OUT5_9") (pintype "output"))
    )
    (net (code "199") (name "R77") (class "Default")
      (node (ref "K77") (pin "5") (pinfunction "COIL_HIGH_5") (pintype "bidirectional"))
      (node (ref "U109") (pin "10") (pinfunction "OUT6_10") (pintype "output"))
    )
    (net (code "200") (name "R78") (class "Default")
      (node (ref "K78") (pin "5") (pinfunction "COIL_HIGH_5") (pintype "bidirectional"))
      (node (ref "U109") (pin "11") (pinfunction "OUT7_11") (pintype "output"))
    )
    (net (code "201") (name "R79") (class "Default")
      (node (ref "K79") (pin "5") (pinfunction "COIL_HIGH_5") (pintype "bidirectional"))
      (node (ref "U109") (pin "12") (pinfunction "OUT8_12") (pintype "output"))
    )
    (net (code "202") (name "R80") (class "Default")
      (node (ref "K80") (pin "5") (pinfunction "COIL_HIGH_5") (pintype "bidirectional"))
      (node (ref "U110") (pin "5") (pinfunction "OUT1_5") (pintype "output"))
    )
    (net (code "203") (name "R81") (class "Default")
      (node (ref "K81") (pin "5") (pinfunction "COIL_HIGH_5") (pintype "bidirectional"))
      (node (ref "U110") (pin "6") (pinfunction "OUT2_6") (pintype "output"))
    )
    (net (code "204") (name "R82") (class "Default")
      (node (ref "K82") (pin "5") (pinfunction "COIL_HIGH_5") (pintype "bidirectional"))
      (node (ref "U110") (pin "7") (pinfunction "OUT3_7") (pintype "output"))
    )
    (net (code "205") (name "R83") (class "Default")
      (node (ref "K83") (pin "5") (pinfunction "COIL_HIGH_5") (pintype "bidirectional"))
      (node (ref "U110") (pin "8") (pinfunction "OUT4_8") (pintype "output"))
    )
    (net (code "206") (name "R84") (class "Default")
      (node (ref "K84") (pin "5") (pinfunction "COIL_HIGH_5") (pintype "bidirectional"))
      (node (ref "U110") (pin "9") (pinfunction "OUT5_9") (pintype "output"))
    )
    (net (code "207") (name "R85") (class "Default")
      (node (ref "K85") (pin "5") (pinfunction "COIL_HIGH_5") (pintype "bidirectional"))
      (node (ref "U110") (pin "10") (pinfunction "OUT6_10") (pintype "output"))
    )
    (net (code "208") (name "R86") (class "Default")
      (node (ref "K86") (pin "5") (pinfunction "COIL_HIGH_5") (pintype "bidirectional"))
      (node (ref "U110") (pin "11") (pinfunction "OUT7_11") (pintype "output"))
    )
    (net (code "209") (name "R87") (class "Default")
      (node (ref "K87") (pin "5") (pinfunction "COIL_HIGH_5") (pintype "bidirectional"))
      (node (ref "U110") (pin "12") (pinfunction "OUT8_12") (pintype "output"))
    )
    (net (code "210") (name "R88") (class "Default")
      (node (ref "K88") (pin "5") (pinfunction "COIL_HIGH_5") (pintype "bidirectional"))
      (node (ref "U111") (pin "5") (pinfunction "OUT1_5") (pintype "output"))
    )
    (net (code "211") (name "R89") (class "Default")
      (node (ref "K89") (pin "5") (pinfunction "COIL_HIGH_5") (pintype "bidirectional"))
      (node (ref "U111") (pin "6") (pinfunction "OUT2_6") (pintype "output"))
    )
    (net (code "212") (name "R90") (class "Default")
      (node (ref "K90") (pin "5") (pinfunction "COIL_HIGH_5") (pintype "bidirectional"))
      (node (ref "U111") (pin "7") (pinfunction "OUT3_7") (pintype "output"))
    )
    (net (code "213") (name "R91") (class "Default")
      (node (ref "K91") (pin "5") (pinfunction "COIL_HIGH_5") (pintype "bidirectional"))
      (node (ref "U111") (pin "8") (pinfunction "OUT4_8") (pintype "output"))
    )
    (net (code "214") (name "R92") (class "Default")
      (node (ref "K92") (pin "5") (pinfunction "COIL_HIGH_5") (pintype "bidirectional"))
      (node (ref "U111") (pin "9") (pinfunction "OUT5_9") (pintype "output"))
    )
    (net (code "215") (name "R93") (class "Default")
      (node (ref "K93") (pin "5") (pinfunction "COIL_HIGH_5") (pintype "bidirectional"))
      (node (ref "U111") (pin "10") (pinfunction "OUT6_10") (pintype "output"))
    )
    (net (code "216") (name "R94") (class "Default")
      (node (ref "K94") (pin "5") (pinfunction "COIL_HIGH_5") (pintype "bidirectional"))
      (node (ref "U111") (pin "11") (pinfunction "OUT7_11") (pintype "output"))
    )
    (net (code "217") (name "R95") (class "Default")
      (node (ref "K95") (pin "5") (pinfunction "COIL_HIGH_5") (pintype "bidirectional"))
      (node (ref "U111") (pin "12") (pinfunction "OUT8_12") (pintype "output"))
    )
    (net (code "218") (name "R96") (class "Default")
      (node (ref "K96") (pin "5") (pinfunction "COIL_HIGH_5") (pintype "bidirectional"))
      (node (ref "U112") (pin "5") (pinfunction "OUT1_5") (pintype "output"))
    )
    (net (code "219") (name "R97") (class "Default")
      (node (ref "K97") (pin "5") (pinfunction "COIL_HIGH_5") (pintype "bidirectional"))
      (node (ref "U112") (pin "6") (pinfunction "OUT2_6") (pintype "output"))
    )
    (net (code "220") (name "R98") (class "Default")
      (node (ref "K98") (pin "5") (pinfunction "COIL_HIGH_5") (pintype "bidirectional"))
      (node (ref "U112") (pin "7") (pinfunction "OUT3_7") (pintype "output"))
    )
    (net (code "221") (name "R99") (class "Default")
      (node (ref "K99") (pin "5") (pinfunction "COIL_HIGH_5") (pintype "bidirectional"))
      (node (ref "U112") (pin "8") (pinfunction "OUT4_8") (pintype "output"))
    )
    (net (code "222") (name "R100") (class "Default")
      (node (ref "K100") (pin "5") (pinfunction "COIL_HIGH_5") (pintype "bidirectional"))
      (node (ref "U112") (pin "9") (pinfunction "OUT5_9") (pintype "output"))
    )
    (net (code "223") (name "R101") (class "Default")
      (node (ref "K101") (pin "5") (pinfunction "COIL_HIGH_5") (pintype "bidirectional"))
      (node (ref "U112") (pin "10") (pinfunction "OUT6_10") (pintype "output"))
    )
    (net (code "224") (name "R102") (class "Default")
      (node (ref "K102") (pin "5") (pinfunction "COIL_HIGH_5") (pintype "bidirectional"))
      (node (ref "U112") (pin "11") (pinfunction "OUT7_11") (pintype "output"))
    )
    (net (code "225") (name "R103") (class "Default")
      (node (ref "K103") (pin "5") (pinfunction "COIL_HIGH_5") (pintype "bidirectional"))
      (node (ref "U112") (pin "12") (pinfunction "OUT8_12") (pintype "output"))
    )
    (net (code "226") (name "R104") (class "Default")
      (node (ref "K104") (pin "5") (pinfunction "COIL_HIGH_5") (pintype "bidirectional"))
      (node (ref "U113") (pin "5") (pinfunction "OUT1_5") (pintype "output"))
    )
    (net (code "227") (name "R105") (class "Default")
      (node (ref "K105") (pin "5") (pinfunction "COIL_HIGH_5") (pintype "bidirectional"))
      (node (ref "U113") (pin "6") (pinfunction "OUT2_6") (pintype "output"))
    )
    (net (code "228") (name "R106") (class "Default")
      (node (ref "K106") (pin "5") (pinfunction "COIL_HIGH_5") (pintype "bidirectional"))
      (node (ref "U113") (pin "7") (pinfunction "OUT3_7") (pintype "output"))
    )
    (net (code "229") (name "R107") (class "Default")
      (node (ref "K107") (pin "5") (pinfunction "COIL_HIGH_5") (pintype "bidirectional"))
      (node (ref "U113") (pin "8") (pinfunction "OUT4_8") (pintype "output"))
    )
    (net (code "230") (name "R108") (class "Default")
      (node (ref "K108") (pin "5") (pinfunction "COIL_HIGH_5") (pintype "bidirectional"))
      (node (ref "U113") (pin "9") (pinfunction "OUT5_9") (pintype "output"))
    )
    (net (code "231") (name "R109") (class "Default")
      (node (ref "K109") (pin "5") (pinfunction "COIL_HIGH_5") (pintype "bidirectional"))
      (node (ref "U113") (pin "10") (pinfunction "OUT6_10") (pintype "output"))
    )
    (net (code "232") (name "R110") (class "Default")
      (node (ref "K110") (pin "5") (pinfunction "COIL_HIGH_5") (pintype "bidirectional"))
      (node (ref "U113") (pin "11") (pinfunction "OUT7_11") (pintype "output"))
    )
    (net (code "233") (name "R111") (class "Default")
      (node (ref "K111") (pin "5") (pinfunction "COIL_HIGH_5") (pintype "bidirectional"))
      (node (ref "U113") (pin "12") (pinfunction "OUT8_12") (pintype "output"))
    )
    (net (code "234") (name "R112") (class "Default")
      (node (ref "K112") (pin "5") (pinfunction "COIL_HIGH_5") (pintype "bidirectional"))
      (node (ref "U114") (pin "5") (pinfunction "OUT1_5") (pintype "output"))
    )
    (net (code "235") (name "R113") (class "Default")
      (node (ref "K113") (pin "5") (pinfunction "COIL_HIGH_5") (pintype "bidirectional"))
      (node (ref "U114") (pin "6") (pinfunction "OUT2_6") (pintype "output"))
    )
    (net (code "236") (name "R114") (class "Default")
      (node (ref "K114") (pin "5") (pinfunction "COIL_HIGH_5") (pintype "bidirectional"))
      (node (ref "U114") (pin "7") (pinfunction "OUT3_7") (pintype "output"))
    )
    (net (code "237") (name "R115") (class "Default")
      (node (ref "K115") (pin "5") (pinfunction "COIL_HIGH_5") (pintype "bidirectional"))
      (node (ref "U114") (pin "8") (pinfunction "OUT4_8") (pintype "output"))
    )
    (net (code "238") (name "R116") (class "Default")
      (node (ref "K116") (pin "5") (pinfunction "COIL_HIGH_5") (pintype "bidirectional"))
      (node (ref "U114") (pin "9") (pinfunction "OUT5_9") (pintype "output"))
    )
    (net (code "239") (name "R117") (class "Default")
      (node (ref "K117") (pin "5") (pinfunction "COIL_HIGH_5") (pintype "bidirectional"))
      (node (ref "U114") (pin "10") (pinfunction "OUT6_10") (pintype "output"))
    )
    (net (code "240") (name "R118") (class "Default")
      (node (ref "K118") (pin "5") (pinfunction "COIL_HIGH_5") (pintype "bidirectional"))
      (node (ref "U114") (pin "11") (pinfunction "OUT7_11") (pintype "output"))
    )
    (net (code "241") (name "R119") (class "Default")
      (node (ref "K119") (pin "5") (pinfunction "COIL_HIGH_5") (pintype "bidirectional"))
      (node (ref "U114") (pin "12") (pinfunction "OUT8_12") (pintype "output"))
    )
    (net (code "242") (name "R120") (class "Default")
      (node (ref "K120") (pin "5") (pinfunction "COIL_HIGH_5") (pintype "bidirectional"))
      (node (ref "U115") (pin "5") (pinfunction "OUT1_5") (pintype "output"))
    )
    (net (code "243") (name "R121") (class "Default")
      (node (ref "K121") (pin "5") (pinfunction "COIL_HIGH_5") (pintype "bidirectional"))
      (node (ref "U115") (pin "6") (pinfunction "OUT2_6") (pintype "output"))
    )
    (net (code "244") (name "R122") (class "Default")
      (node (ref "K122") (pin "5") (pinfunction "COIL_HIGH_5") (pintype "bidirectional"))
      (node (ref "U115") (pin "7") (pinfunction "OUT3_7") (pintype "output"))
    )
    (net (code "245") (name "R123") (class "Default")
      (node (ref "K123") (pin "5") (pinfunction "COIL_HIGH_5") (pintype "bidirectional"))
      (node (ref "U115") (pin "8") (pinfunction "OUT4_8") (pintype "output"))
    )
    (net (code "246") (name "R124") (class "Default")
      (node (ref "K124") (pin "5") (pinfunction "COIL_HIGH_5") (pintype "bidirectional"))
      (node (ref "U115") (pin "9") (pinfunction "OUT5_9") (pintype "output"))
    )
    (net (code "247") (name "R125") (class "Default")
      (node (ref "K125") (pin "5") (pinfunction "COIL_HIGH_5") (pintype "bidirectional"))
      (node (ref "U115") (pin "10") (pinfunction "OUT6_10") (pintype "output"))
    )
    (net (code "248") (name "R126") (class "Default")
      (node (ref "K126") (pin "5") (pinfunction "COIL_HIGH_5") (pintype "bidirectional"))
      (node (ref "U115") (pin "11") (pinfunction "OUT7_11") (pintype "output"))
    )
    (net (code "249") (name "R127") (class "Default")
      (node (ref "K127") (pin "5") (pinfunction "COIL_HIGH_5") (pintype "bidirectional"))
      (node (ref "U115") (pin "12") (pinfunction "OUT8_12") (pintype "output"))
    )
    (net (code "250") (name "RXT") (class "Default")
      (node (ref "D2") (pin "1") (pinfunction "LOW_1") (pintype "bidirectional"))
      (node (ref "U2") (pin "13") (pinfunction "GPIO.1_/_RXT_13") (pintype "bidirectional"))
    )
    (net (code "251") (name "SER_VBUS") (class "Default")
      (node (ref "R12") (pin "2") (pinfunction "2_2") (pintype "passive"))
      (node (ref "R13") (pin "1") (pinfunction "1_1") (pintype "passive"))
      (node (ref "U2") (pin "8") (pinfunction "VBUS_8") (pintype "input"))
    )
    (net (code "252") (name "STATPWR") (class "Default")
      (node (ref "R31") (pin "2") (pinfunction "2_2") (pintype "passive"))
      (node (ref "U30") (pin "13") (pinfunction "P$13_13") (pintype "bidirectional"))
      (node (ref "U30") (pin "18") (pinfunction "P$18_18") (pintype "bidirectional"))
      (node (ref "U30") (pin "3") (pinfunction "P$3_3") (pintype "bidirectional"))
      (node (ref "U30") (pin "8") (pinfunction "P$8_8") (pintype "bidirectional"))
    )
    (net (code "253") (name "STATPWR_HI") (class "Default")
      (node (ref "R31") (pin "1") (pinfunction "1_1") (pintype "passive"))
      (node (ref "U20") (pin "15") (pinfunction "QA_15") (pintype "bidirectional"))
    )
    (net (code "254") (name "STAT_OUT") (class "Default")
      (node (ref "U20") (pin "9") (pinfunction "QH'_9") (pintype "bidirectional"))
      (node (ref "U21") (pin "14") (pinfunction "SER_14") (pintype "bidirectional"))
    )
    (net (code "255") (name "SWDCLK") (class "Default")
      (node (ref "U1") (pin "52") (pinfunction "PC0_TCK_SWCLK_52") (pintype "bidirectional"))
      (node (ref "X2") (pin "P$4") (pinfunction "SWDCLK_P$4") (pintype "bidirectional"))
    )
    (net (code "256") (name "SWDIO") (class "Default")
      (node (ref "U1") (pin "51") (pinfunction "PC1_TMS_SWDIO_51") (pintype "bidirectional"))
      (node (ref "X2") (pin "P$2") (pinfunction "SWDIO_P$2") (pintype "bidirectional"))
    )
    (net (code "257") (name "SWO") (class "Default")
      (node (ref "U1") (pin "49") (pinfunction "PC3_TDO_SWO_49") (pintype "bidirectional"))
      (node (ref "X2") (pin "P$6") (pinfunction "SWO_P$6") (pintype "bidirectional"))
    )
    (net (code "258") (name "TXT") (class "Default")
      (node (ref "D1") (pin "1") (pinfunction "LOW_1") (pintype "bidirectional"))
      (node (ref "U2") (pin "14") (pinfunction "GPIO.0_/_TXT_14") (pintype "bidirectional"))
    )
    (net (code "259") (name "USB_DN") (class "Default")
      (node (ref "U2") (pin "4") (pinfunction "D-_4") (pintype "bidirectional"))
      (node (ref "U6") (pin "3") (pinfunction "IO2_3") (pintype "bidirectional"))
      (node (ref "X1") (pin "A7") (pinfunction "DN1_A7") (pintype "bidirectional"))
      (node (ref "X1") (pin "B7") (pinfunction "DN2_B7") (pintype "bidirectional"))
    )
    (net (code "260") (name "USB_DP") (class "Default")
      (node (ref "U2") (pin "3") (pinfunction "D+_3") (pintype "bidirectional"))
      (node (ref "U6") (pin "1") (pinfunction "IO1_1") (pintype "bidirectional"))
      (node (ref "X1") (pin "A6") (pinfunction "DP1_A6") (pintype "bidirectional"))
      (node (ref "X1") (pin "B6") (pinfunction "DP2_B6") (pintype "bidirectional"))
    )
    (net (code "261") (name "USB_SER_RX") (class "Default")
      (node (ref "S1") (pin "6") (pinfunction "6_6") (pintype "passive"))
      (node (ref "U2") (pin "20") (pinfunction "RXD_20") (pintype "input"))
    )
    (net (code "262") (name "USB_SER_TX") (class "Default")
      (node (ref "S1") (pin "3") (pinfunction "3_3") (pintype "passive"))
      (node (ref "U2") (pin "21") (pinfunction "TXD_21") (pintype "output"))
    )
    (net (code "263") (name "VBAT") (class "Default")
      (node (ref "U1") (pin "37") (pinfunction "VBAT_37") (pintype "power_in"))
    )
    (net (code "264") (name "VBUS") (class "Default")
      (node (ref "C46") (pin "1") (pinfunction "1_1") (pintype "passive"))
      (node (ref "R13") (pin "2") (pinfunction "2_2") (pintype "passive"))
      (node (ref "U6") (pin "5") (pinfunction "VCC_5") (pintype "power_in"))
      (node (ref "X1") (pin "A4/B9") (pinfunction "VBUS_2_A4/B9") (pintype "power_in"))
      (node (ref "X1") (pin "B4/A9") (pinfunction "VBUS_B4/A9") (pintype "power_in"))
    )
    (net (code "265") (name "VCC") (class "Default")
      (node (ref "C1") (pin "1") (pinfunction "1_1") (pintype "passive"))
      (node (ref "C101") (pin "1") (pinfunction "1_1") (pintype "passive"))
      (node (ref "C102") (pin "1") (pinfunction "1_1") (pintype "passive"))
      (node (ref "C103") (pin "1") (pinfunction "1_1") (pintype "passive"))
      (node (ref "C104") (pin "1") (pinfunction "1_1") (pintype "passive"))
      (node (ref "C105") (pin "1") (pinfunction "1_1") (pintype "passive"))
      (node (ref "C106") (pin "1") (pinfunction "1_1") (pintype "passive"))
      (node (ref "C14") (pin "1") (pinfunction "1_1") (pintype "passive"))
      (node (ref "C15") (pin "1") (pinfunction "1_1") (pintype "passive"))
      (node (ref "C16") (pin "1") (pinfunction "1_1") (pintype "passive"))
      (node (ref "C17") (pin "1") (pinfunction "1_1") (pintype "passive"))
      (node (ref "C19") (pin "1") (pinfunction "1_1") (pintype "passive"))
      (node (ref "C2") (pin "1") (pinfunction "1_1") (pintype "passive"))
      (node (ref "C20") (pin "1") (pinfunction "1_1") (pintype "passive"))
      (node (ref "C21") (pin "1") (pinfunction "1_1") (pintype "passive"))
      (node (ref "C22") (pin "1") (pinfunction "1_1") (pintype "passive"))
      (node (ref "C23") (pin "1") (pinfunction "1_1") (pintype "passive"))
      (node (ref "C24") (pin "1") (pinfunction "1_1") (pintype "passive"))
      (node (ref "C25") (pin "1") (pinfunction "1_1") (pintype "passive"))
      (node (ref "C26") (pin "1") (pinfunction "1_1") (pintype "passive"))
      (node (ref "C27") (pin "1") (pinfunction "1_1") (pintype "passive"))
      (node (ref "C28") (pin "1") (pinfunction "1_1") (pintype "passive"))
      (node (ref "C29") (pin "1") (pinfunction "1_1") (pintype "passive"))
      (node (ref "C3") (pin "1") (pinfunction "1_1") (pintype "passive"))
      (node (ref "C30") (pin "1") (pinfunction "1_1") (pintype "passive"))
      (node (ref "C4") (pin "1") (pinfunction "1_1") (pintype "passive"))
      (node (ref "C47") (pin "1") (pinfunction "1_1") (pintype "passive"))
      (node (ref "C5") (pin "1") (pinfunction "1_1") (pintype "passive"))
      (node (ref "C6") (pin "1") (pinfunction "1_1") (pintype "passive"))
      (node (ref "D1") (pin "2") (pinfunction "HIGH_2") (pintype "bidirectional"))
      (node (ref "D2") (pin "2") (pinfunction "HIGH_2") (pintype "bidirectional"))
      (node (ref "R14") (pin "2") (pinfunction "2_2") (pintype "passive"))
      (node (ref "R33") (pin "2") (pinfunction "2_2") (pintype "passive"))
      (node (ref "R37") (pin "2") (pinfunction "2_2") (pintype "passive"))
      (node (ref "R9") (pin "1") (pinfunction "1_1") (pintype "passive"))
      (node (ref "U1") (pin "11") (pinfunction "VDD_2_11") (pintype "power_in"))
      (node (ref "U1") (pin "2") (pinfunction "VDDA_2") (pintype "power_in"))
      (node (ref "U1") (pin "26") (pinfunction "VDD_3_26") (pintype "power_in"))
      (node (ref "U1") (pin "42") (pinfunction "VDD_4_42") (pintype "power_in"))
      (node (ref "U1") (pin "54") (pinfunction "VDD_54") (pintype "power_in"))
      (node (ref "U100") (pin "15") (pinfunction "LOGICSUPPLY_15") (pintype "passive"))
      (node (ref "U101") (pin "15") (pinfunction "LOGICSUPPLY_15") (pintype "passive"))
      (node (ref "U102") (pin "15") (pinfunction "LOGICSUPPLY_15") (pintype "passive"))
      (node (ref "U103") (pin "15") (pinfunction "LOGICSUPPLY_15") (pintype "passive"))
      (node (ref "U104") (pin "15") (pinfunction "LOGICSUPPLY_15") (pintype "passive"))
      (node (ref "U105") (pin "15") (pinfunction "LOGICSUPPLY_15") (pintype "passive"))
      (node (ref "U106") (pin "15") (pinfunction "LOGICSUPPLY_15") (pintype "passive"))
      (node (ref "U107") (pin "15") (pinfunction "LOGICSUPPLY_15") (pintype "passive"))
      (node (ref "U108") (pin "15") (pinfunction "LOGICSUPPLY_15") (pintype "passive"))
      (node (ref "U109") (pin "15") (pinfunction "LOGICSUPPLY_15") (pintype "passive"))
      (node (ref "U110") (pin "15") (pinfunction "LOGICSUPPLY_15") (pintype "passive"))
      (node (ref "U111") (pin "15") (pinfunction "LOGICSUPPLY_15") (pintype "passive"))
      (node (ref "U112") (pin "15") (pinfunction "LOGICSUPPLY_15") (pintype "passive"))
      (node (ref "U113") (pin "15") (pinfunction "LOGICSUPPLY_15") (pintype "passive"))
      (node (ref "U114") (pin "15") (pinfunction "LOGICSUPPLY_15") (pintype "passive"))
      (node (ref "U115") (pin "15") (pinfunction "LOGICSUPPLY_15") (pintype "passive"))
      (node (ref "U2") (pin "5") (pinfunction "VIO_5") (pintype "power_in"))
      (node (ref "U2") (pin "6") (pinfunction "VDD_6") (pintype "power_in"))
      (node (ref "U2") (pin "7") (pinfunction "VREGIN_7") (pintype "power_in"))
      (node (ref "U20") (pin "16") (pinfunction "VCC_16") (pintype "bidirectional"))
      (node (ref "U21") (pin "16") (pinfunction "VCC_16") (pintype "bidirectional"))
      (node (ref "U22") (pin "16") (pinfunction "VCC_16") (pintype "bidirectional"))
      (node (ref "U23") (pin "16") (pinfunction "VCC_16") (pintype "bidirectional"))
      (node (ref "U4") (pin "2") (pinfunction "VOUT_2") (pintype "bidirectional"))
      (node (ref "U4") (pin "4") (pinfunction "VOUT_4") (pintype "bidirectional"))
      (node (ref "U5") (pin "1") (pinfunction "EN_1") (pintype "bidirectional"))
      (node (ref "U5") (pin "4") (pinfunction "VDD_4") (pintype "bidirectional"))
      (node (ref "X2") (pin "P$1") (pinfunction "VCC_P$1") (pintype "bidirectional"))
    )
    (net (code "266") (name "VDDC") (class "Default")
      (node (ref "C107") (pin "1") (pinfunction "1_1") (pintype "passive"))
      (node (ref "C108") (pin "1") (pinfunction "1_1") (pintype "passive"))
      (node (ref "C109") (pin "1") (pinfunction "1_1") (pintype "passive"))
      (node (ref "C110") (pin "1") (pinfunction "1_1") (pintype "passive"))
      (node (ref "U1") (pin "25") (pinfunction "VDDC_2_25") (pintype "power_in"))
      (node (ref "U1") (pin "56") (pinfunction "VDDC_56") (pintype "power_in"))
    )
    (net (code "267") (name "unconnected-(J6-Pad2)") (class "Default")
      (node (ref "J6") (pin "2") (pinfunction "2_2") (pintype "passive"))
    )
    (net (code "268") (name "unconnected-(J6-Pad3)") (class "Default")
      (node (ref "J6") (pin "3") (pinfunction "3_3") (pintype "passive"))
    )
    (net (code "269") (name "unconnected-(J6-Pad4)") (class "Default")
      (node (ref "J6") (pin "4") (pinfunction "4_4") (pintype "passive"))
    )
    (net (code "270") (name "unconnected-(J7-Pad2)") (class "Default")
      (node (ref "J7") (pin "2") (pinfunction "2_2") (pintype "passive"))
    )
    (net (code "271") (name "unconnected-(J7-Pad3)") (class "Default")
      (node (ref "J7") (pin "3") (pinfunction "3_3") (pintype "passive"))
    )
    (net (code "272") (name "unconnected-(J7-Pad4)") (class "Default")
      (node (ref "J7") (pin "4") (pinfunction "4_4") (pintype "passive"))
    )
    (net (code "273") (name "unconnected-(J8-Pad2)") (class "Default")
      (node (ref "J8") (pin "2") (pinfunction "2_2") (pintype "passive"))
    )
    (net (code "274") (name "unconnected-(J8-Pad3)") (class "Default")
      (node (ref "J8") (pin "3") (pinfunction "3_3") (pintype "passive"))
    )
    (net (code "275") (name "unconnected-(J8-Pad4)") (class "Default")
      (node (ref "J8") (pin "4") (pinfunction "4_4") (pintype "passive"))
    )
    (net (code "276") (name "unconnected-(U1-HIB_N-Pad33)") (class "Default")
      (node (ref "U1") (pin "33") (pinfunction "HIB_N_33") (pintype "output"))
    )
    (net (code "277") (name "unconnected-(U1-OSC0-Pad40)") (class "Default")
      (node (ref "U1") (pin "40") (pinfunction "OSC0_40") (pintype "input"))
    )
    (net (code "278") (name "unconnected-(U1-OSC1-Pad41)") (class "Default")
      (node (ref "U1") (pin "41") (pinfunction "OSC1_41") (pintype "output"))
    )
    (net (code "279") (name "unconnected-(U1-PA7-Pad24)") (class "Default")
      (node (ref "U1") (pin "24") (pinfunction "PA7_24") (pintype "bidirectional"))
    )
    (net (code "280") (name "unconnected-(U1-PB0_USB0VID-Pad45)") (class "Default")
      (node (ref "U1") (pin "45") (pinfunction "PB0_USB0VID_45") (pintype "bidirectional"))
    )
    (net (code "281") (name "unconnected-(U1-PB1_USB0VBUS-Pad46)") (class "Default")
      (node (ref "U1") (pin "46") (pinfunction "PB1_USB0VBUS_46") (pintype "bidirectional"))
    )
    (net (code "282") (name "unconnected-(U1-PB2_I2C0SCL-Pad47)") (class "Default")
      (node (ref "U1") (pin "47") (pinfunction "PB2_I2C0SCL_47") (pintype "bidirectional"))
    )
    (net (code "283") (name "unconnected-(U1-PB3_I2C0SDA-Pad48)") (class "Default")
      (node (ref "U1") (pin "48") (pinfunction "PB3_I2C0SDA_48") (pintype "bidirectional"))
    )
    (net (code "284") (name "unconnected-(U1-PB4-Pad58)") (class "Default")
      (node (ref "U1") (pin "58") (pinfunction "PB4_58") (pintype "bidirectional"))
    )
    (net (code "285") (name "unconnected-(U1-PB5-Pad57)") (class "Default")
      (node (ref "U1") (pin "57") (pinfunction "PB5_57") (pintype "bidirectional"))
    )
    (net (code "286") (name "unconnected-(U1-PB6-Pad1)") (class "Default")
      (node (ref "U1") (pin "1") (pinfunction "PB6_1") (pintype "bidirectional"))
    )
    (net (code "287") (name "unconnected-(U1-PB7-Pad4)") (class "Default")
      (node (ref "U1") (pin "4") (pinfunction "PB7_4") (pintype "bidirectional"))
    )
    (net (code "288") (name "unconnected-(U1-PC2_TDI-Pad50)") (class "Default")
      (node (ref "U1") (pin "50") (pinfunction "PC2_TDI_50") (pintype "bidirectional"))
    )
    (net (code "289") (name "unconnected-(U1-PC6-Pad14)") (class "Default")
      (node (ref "U1") (pin "14") (pinfunction "PC6_14") (pintype "bidirectional"))
    )
    (net (code "290") (name "unconnected-(U1-PC7-Pad13)") (class "Default")
      (node (ref "U1") (pin "13") (pinfunction "PC7_13") (pintype "bidirectional"))
    )
    (net (code "291") (name "unconnected-(U1-PD4-Pad43)") (class "Default")
      (node (ref "U1") (pin "43") (pinfunction "PD4_43") (pintype "bidirectional"))
    )
    (net (code "292") (name "unconnected-(U1-PD5-Pad44)") (class "Default")
      (node (ref "U1") (pin "44") (pinfunction "PD5_44") (pintype "bidirectional"))
    )
    (net (code "293") (name "unconnected-(U1-PD6-Pad53)") (class "Default")
      (node (ref "U1") (pin "53") (pinfunction "PD6_53") (pintype "bidirectional"))
    )
    (net (code "294") (name "unconnected-(U1-PD7-Pad10)") (class "Default")
      (node (ref "U1") (pin "10") (pinfunction "PD7_10") (pintype "bidirectional"))
    )
    (net (code "295") (name "unconnected-(U1-PE2-Pad7)") (class "Default")
      (node (ref "U1") (pin "7") (pinfunction "PE2_7") (pintype "bidirectional"))
    )
    (net (code "296") (name "unconnected-(U1-PE3-Pad6)") (class "Default")
      (node (ref "U1") (pin "6") (pinfunction "PE3_6") (pintype "bidirectional"))
    )
    (net (code "297") (name "unconnected-(U1-PF0-Pad28)") (class "Default")
      (node (ref "U1") (pin "28") (pinfunction "PF0_28") (pintype "bidirectional"))
    )
    (net (code "298") (name "unconnected-(U1-PF1-Pad29)") (class "Default")
      (node (ref "U1") (pin "29") (pinfunction "PF1_29") (pintype "bidirectional"))
    )
    (net (code "299") (name "unconnected-(U1-PF2-Pad30)") (class "Default")
      (node (ref "U1") (pin "30") (pinfunction "PF2_30") (pintype "bidirectional"))
    )
    (net (code "300") (name "unconnected-(U1-PF3-Pad31)") (class "Default")
      (node (ref "U1") (pin "31") (pinfunction "PF3_31") (pintype "bidirectional"))
    )
    (net (code "301") (name "unconnected-(U1-PF4-Pad5)") (class "Default")
      (node (ref "U1") (pin "5") (pinfunction "PF4_5") (pintype "bidirectional"))
    )
    (net (code "302") (name "unconnected-(U1-WAKE_N-Pad32)") (class "Default")
      (node (ref "U1") (pin "32") (pinfunction "WAKE_N_32") (pintype "input"))
    )
    (net (code "303") (name "unconnected-(U1-XOSC1-Pad36)") (class "Default")
      (node (ref "U1") (pin "36") (pinfunction "XOSC1_36") (pintype "output"))
    )
    (net (code "304") (name "unconnected-(U2-CTS-Pad18)") (class "Default")
      (node (ref "U2") (pin "18") (pinfunction "CTS_18") (pintype "input"))
    )
    (net (code "305") (name "unconnected-(U2-DCD-Pad24)") (class "Default")
      (node (ref "U2") (pin "24") (pinfunction "DCD_24") (pintype "input"))
    )
    (net (code "306") (name "unconnected-(U2-DSR-Pad22)") (class "Default")
      (node (ref "U2") (pin "22") (pinfunction "DSR_22") (pintype "input"))
    )
    (net (code "307") (name "unconnected-(U2-DTR-Pad23)") (class "Default")
      (node (ref "U2") (pin "23") (pinfunction "DTR_23") (pintype "output"))
    )
    (net (code "308") (name "unconnected-(U2-GPIO.2{slash}RS485-Pad12)") (class "Default")
      (node (ref "U2") (pin "12") (pinfunction "GPIO.2/RS485_12") (pintype "bidirectional"))
    )
    (net (code "309") (name "unconnected-(U2-GPIO.3{slash}WAKEUP-Pad11)") (class "Default")
      (node (ref "U2") (pin "11") (pinfunction "GPIO.3/WAKEUP_11") (pintype "bidirectional"))
    )
    (net (code "310") (name "unconnected-(U2-NC-Pad16)") (class "Default")
      (node (ref "U2") (pin "16") (pinfunction "NC_16") (pintype "no_connect"))
    )
    (net (code "311") (name "unconnected-(U2-NC_2-Pad10)") (class "Default")
      (node (ref "U2") (pin "10") (pinfunction "NC_2_10") (pintype "no_connect"))
    )
    (net (code "312") (name "unconnected-(U2-RI{slash}CLK-Pad1)") (class "Default")
      (node (ref "U2") (pin "1") (pinfunction "RI/CLK_1") (pintype "bidirectional"))
    )
    (net (code "313") (name "unconnected-(U2-RTS-Pad19)") (class "Default")
      (node (ref "U2") (pin "19") (pinfunction "RTS_19") (pintype "output"))
    )
    (net (code "314") (name "unconnected-(U2-SUSPEND-Pad17)") (class "Default")
      (node (ref "U2") (pin "17") (pinfunction "SUSPEND_17") (pintype "output"))
    )
    (net (code "315") (name "unconnected-(U2-SUSPENDB-Pad15)") (class "Default")
      (node (ref "U2") (pin "15") (pinfunction "SUSPENDB_15") (pintype "output"))
    )
    (net (code "316") (name "unconnected-(U6-IO3-Pad4)") (class "Default")
      (node (ref "U6") (pin "4") (pinfunction "IO3_4") (pintype "bidirectional"))
    )
    (net (code "317") (name "unconnected-(U6-IO4-Pad6)") (class "Default")
      (node (ref "U6") (pin "6") (pinfunction "IO4_6") (pintype "bidirectional"))
    )
    (net (code "318") (name "unconnected-(U20-QB-Pad1)") (class "Default")
      (node (ref "U20") (pin "1") (pinfunction "QB_1") (pintype "bidirectional"))
    )
    (net (code "319") (name "unconnected-(U20-QC-Pad2)") (class "Default")
      (node (ref "U20") (pin "2") (pinfunction "QC_2") (pintype "bidirectional"))
    )
    (net (code "320") (name "unconnected-(U20-QD-Pad3)") (class "Default")
      (node (ref "U20") (pin "3") (pinfunction "QD_3") (pintype "bidirectional"))
    )
    (net (code "321") (name "unconnected-(U20-QE-Pad4)") (class "Default")
      (node (ref "U20") (pin "4") (pinfunction "QE_4") (pintype "bidirectional"))
    )
    (net (code "322") (name "unconnected-(U20-QF-Pad5)") (class "Default")
      (node (ref "U20") (pin "5") (pinfunction "QF_5") (pintype "bidirectional"))
    )
    (net (code "323") (name "unconnected-(U20-QG-Pad6)") (class "Default")
      (node (ref "U20") (pin "6") (pinfunction "QG_6") (pintype "bidirectional"))
    )
    (net (code "324") (name "unconnected-(U20-QH-Pad7)") (class "Default")
      (node (ref "U20") (pin "7") (pinfunction "QH_7") (pintype "bidirectional"))
    )
    (net (code "325") (name "unconnected-(U23-QH'-Pad9)") (class "Default")
      (node (ref "U23") (pin "9") (pinfunction "QH'_9") (pintype "bidirectional"))
    )
    (net (code "326") (name "unconnected-(U100-SERIALDATAOUT-Pad16)") (class "Default")
      (node (ref "U100") (pin "16") (pinfunction "SERIALDATAOUT_16") (pintype "output"))
    )
    (net (code "327") (name "unconnected-(X1-SBU1-PadA8)") (class "Default")
      (node (ref "X1") (pin "A8") (pinfunction "SBU1_A8") (pintype "bidirectional"))
    )
    (net (code "328") (name "unconnected-(X1-SBU2-PadB8)") (class "Default")
      (node (ref "X1") (pin "B8") (pinfunction "SBU2_B8") (pintype "bidirectional"))
    )
    (net (code "329") (name "unconnected-(X2-NC-PadP$8)") (class "Default")
      (node (ref "X2") (pin "P$8") (pinfunction "NC_P$8") (pintype "bidirectional"))
    )
    (net (code "330") (name "~{RST}") (class "Default")
      (node (ref "C13") (pin "1") (pinfunction "1_1") (pintype "passive"))
      (node (ref "R14") (pin "1") (pinfunction "1_1") (pintype "passive"))
      (node (ref "R32") (pin "1") (pinfunction "1_1") (pintype "passive"))
      (node (ref "U1") (pin "38") (pinfunction "RST_N_38") (pintype "input"))
      (node (ref "X2") (pin "P$10") (pinfunction "NRST_P$10") (pintype "bidirectional"))
    )
  )
)
